# STEP_Controller.net
KiCad netlist of a schematic drawn in EasyEDA Pro
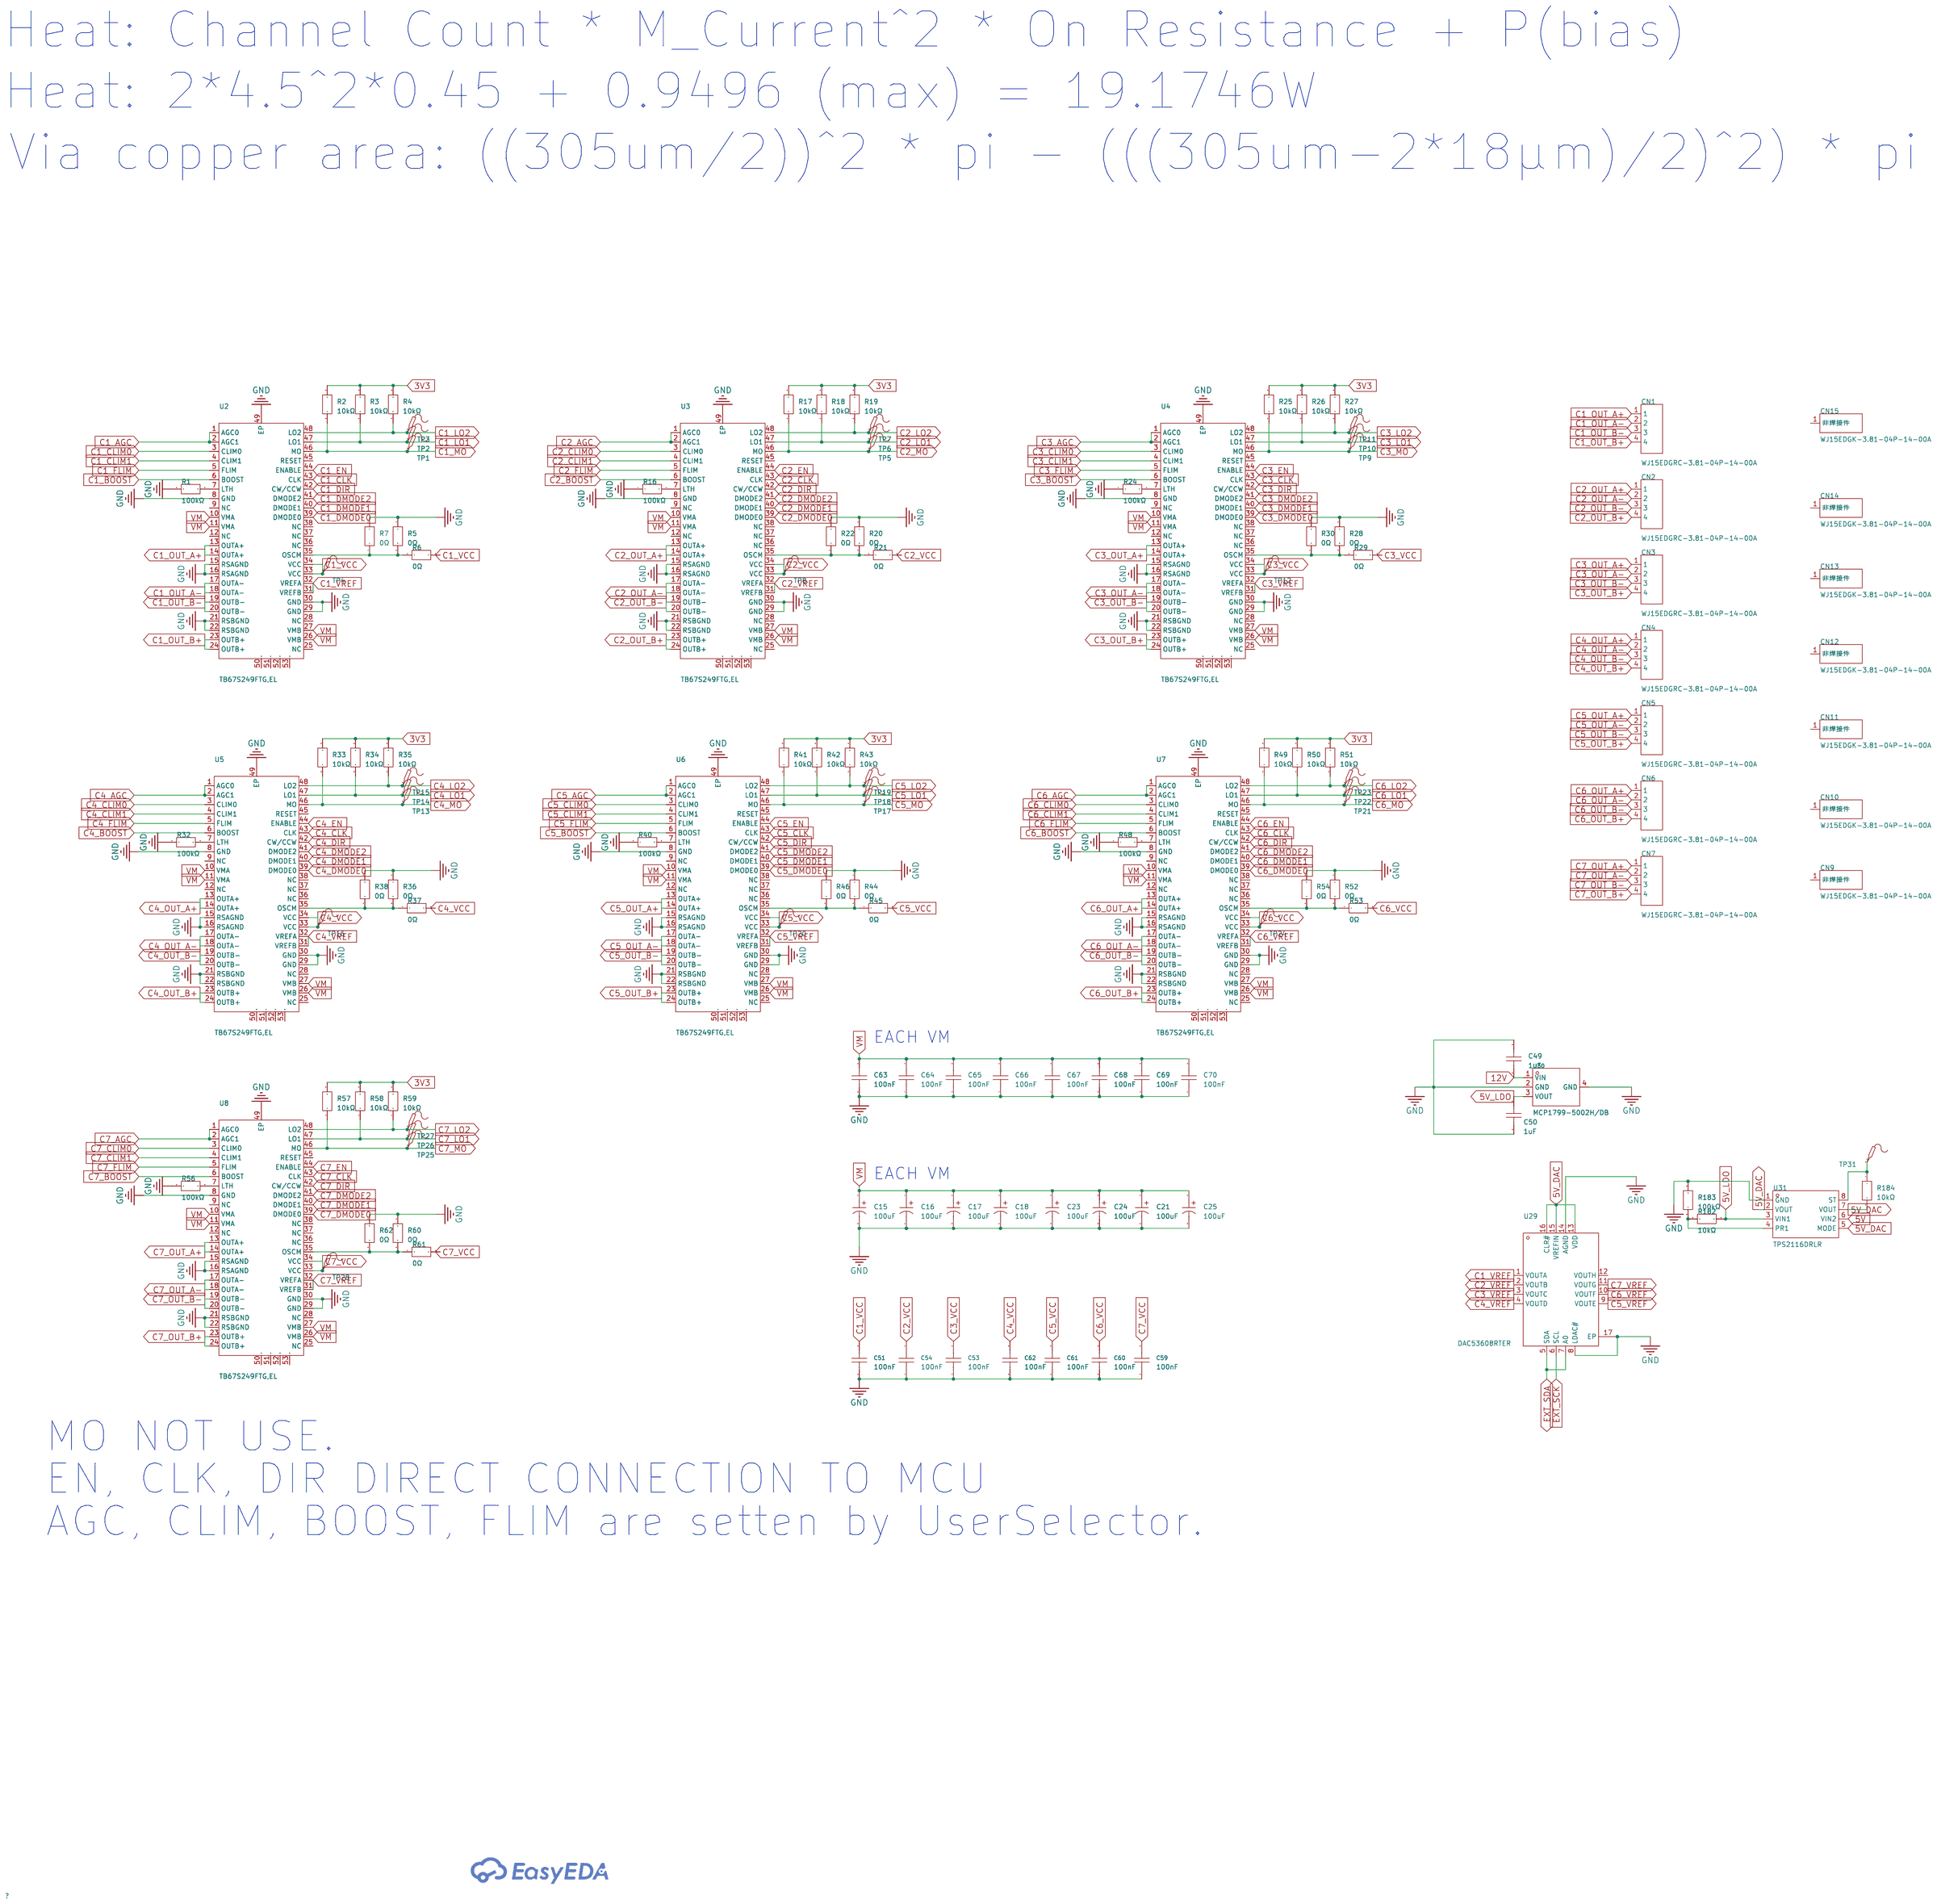
[diagram p0: DRIVER]
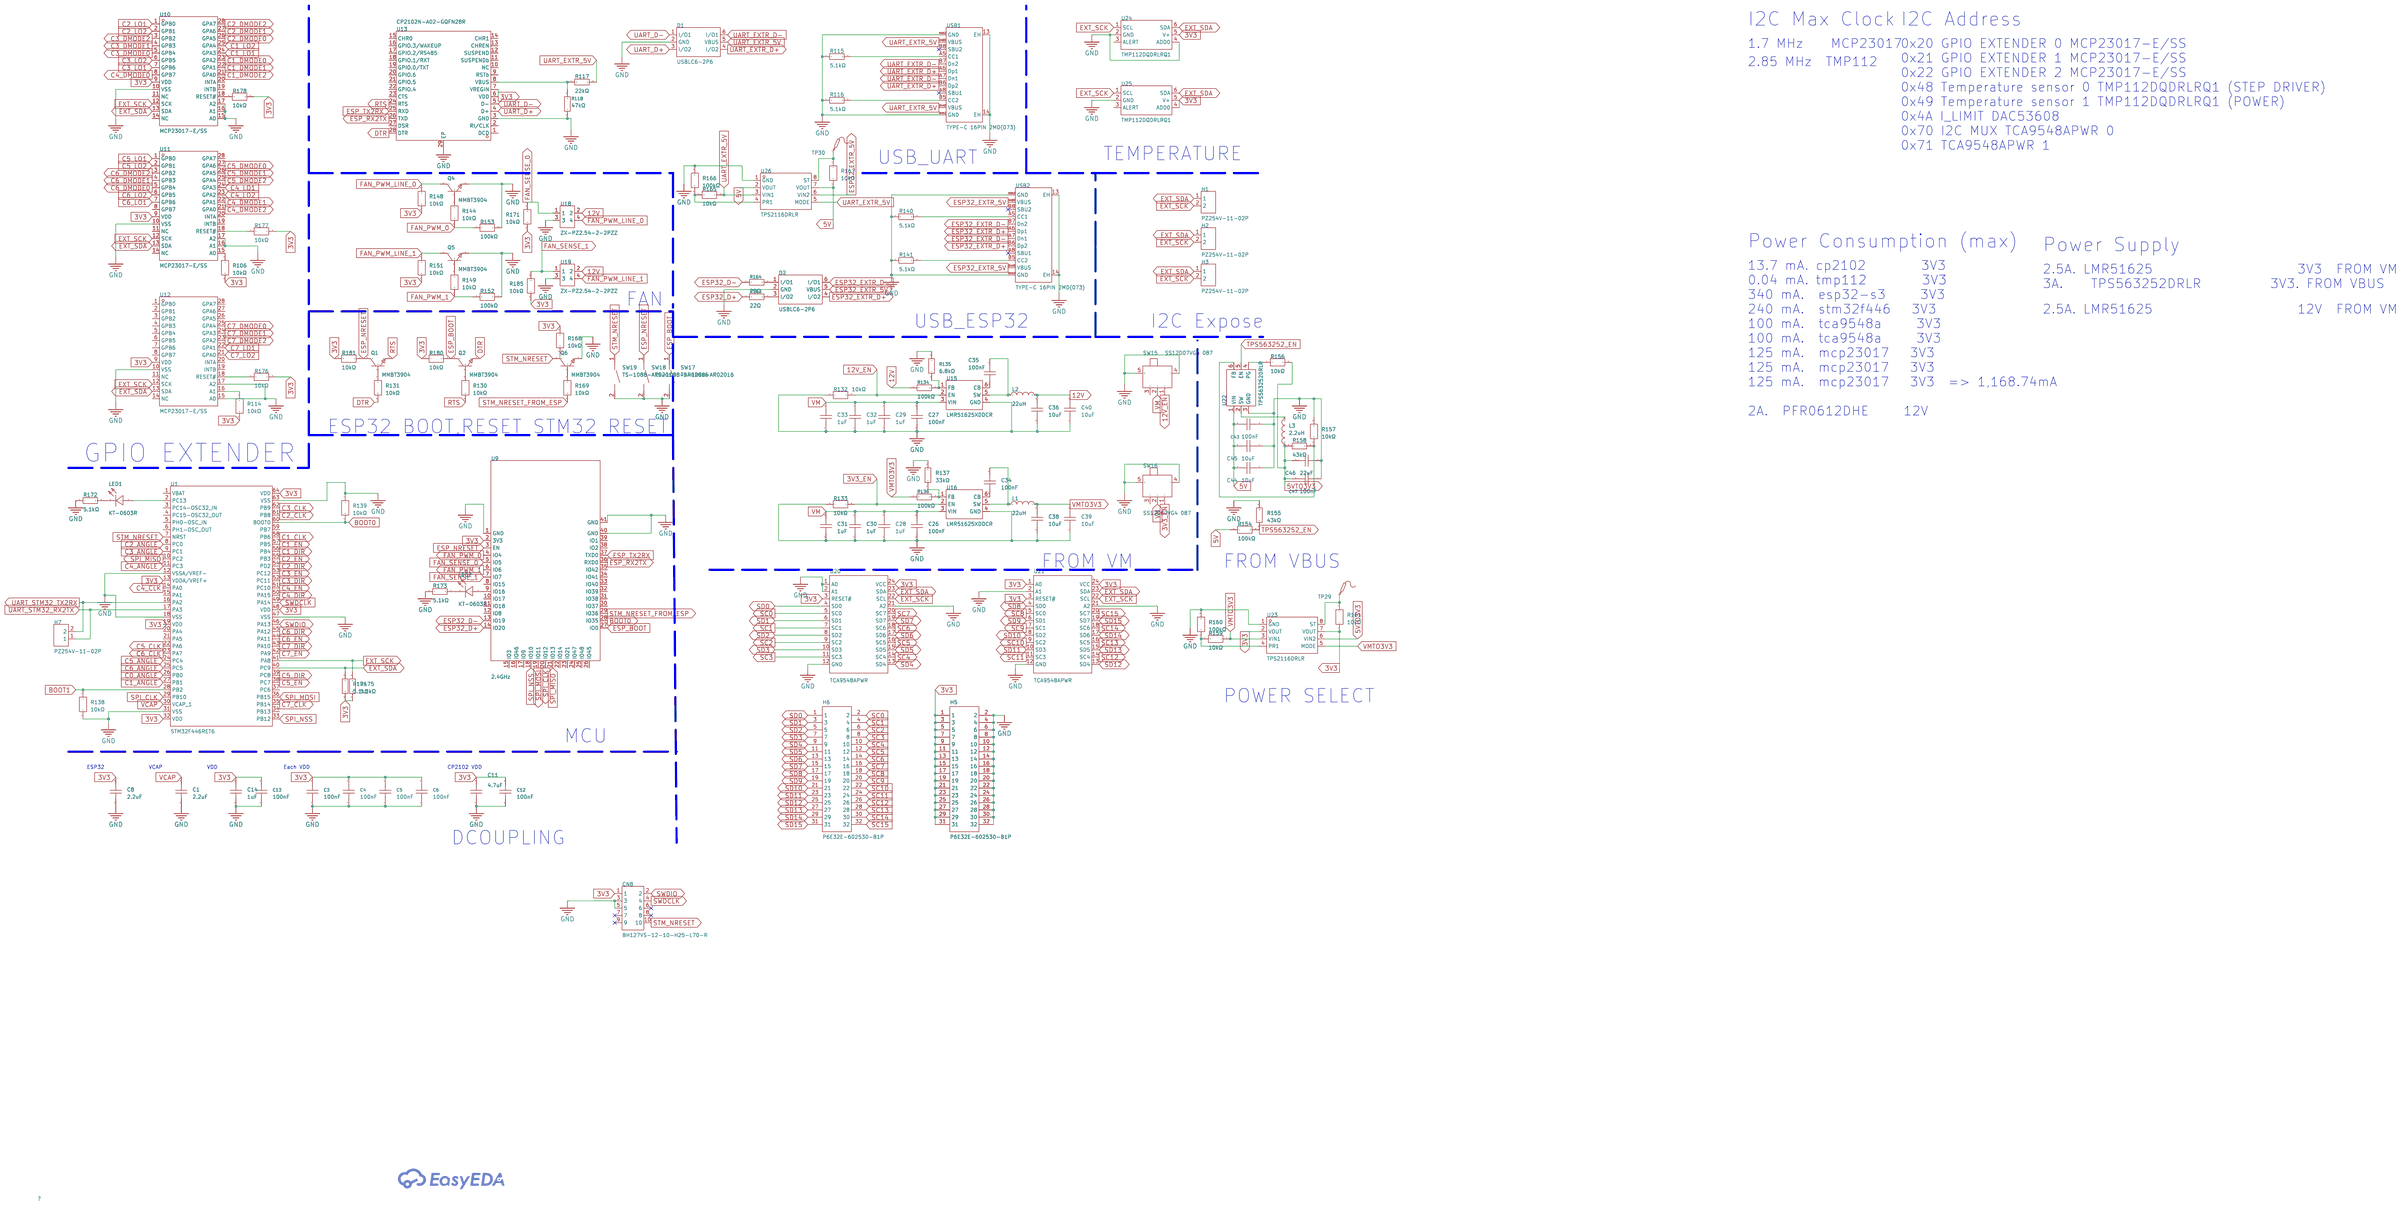
[diagram p1: MCU]
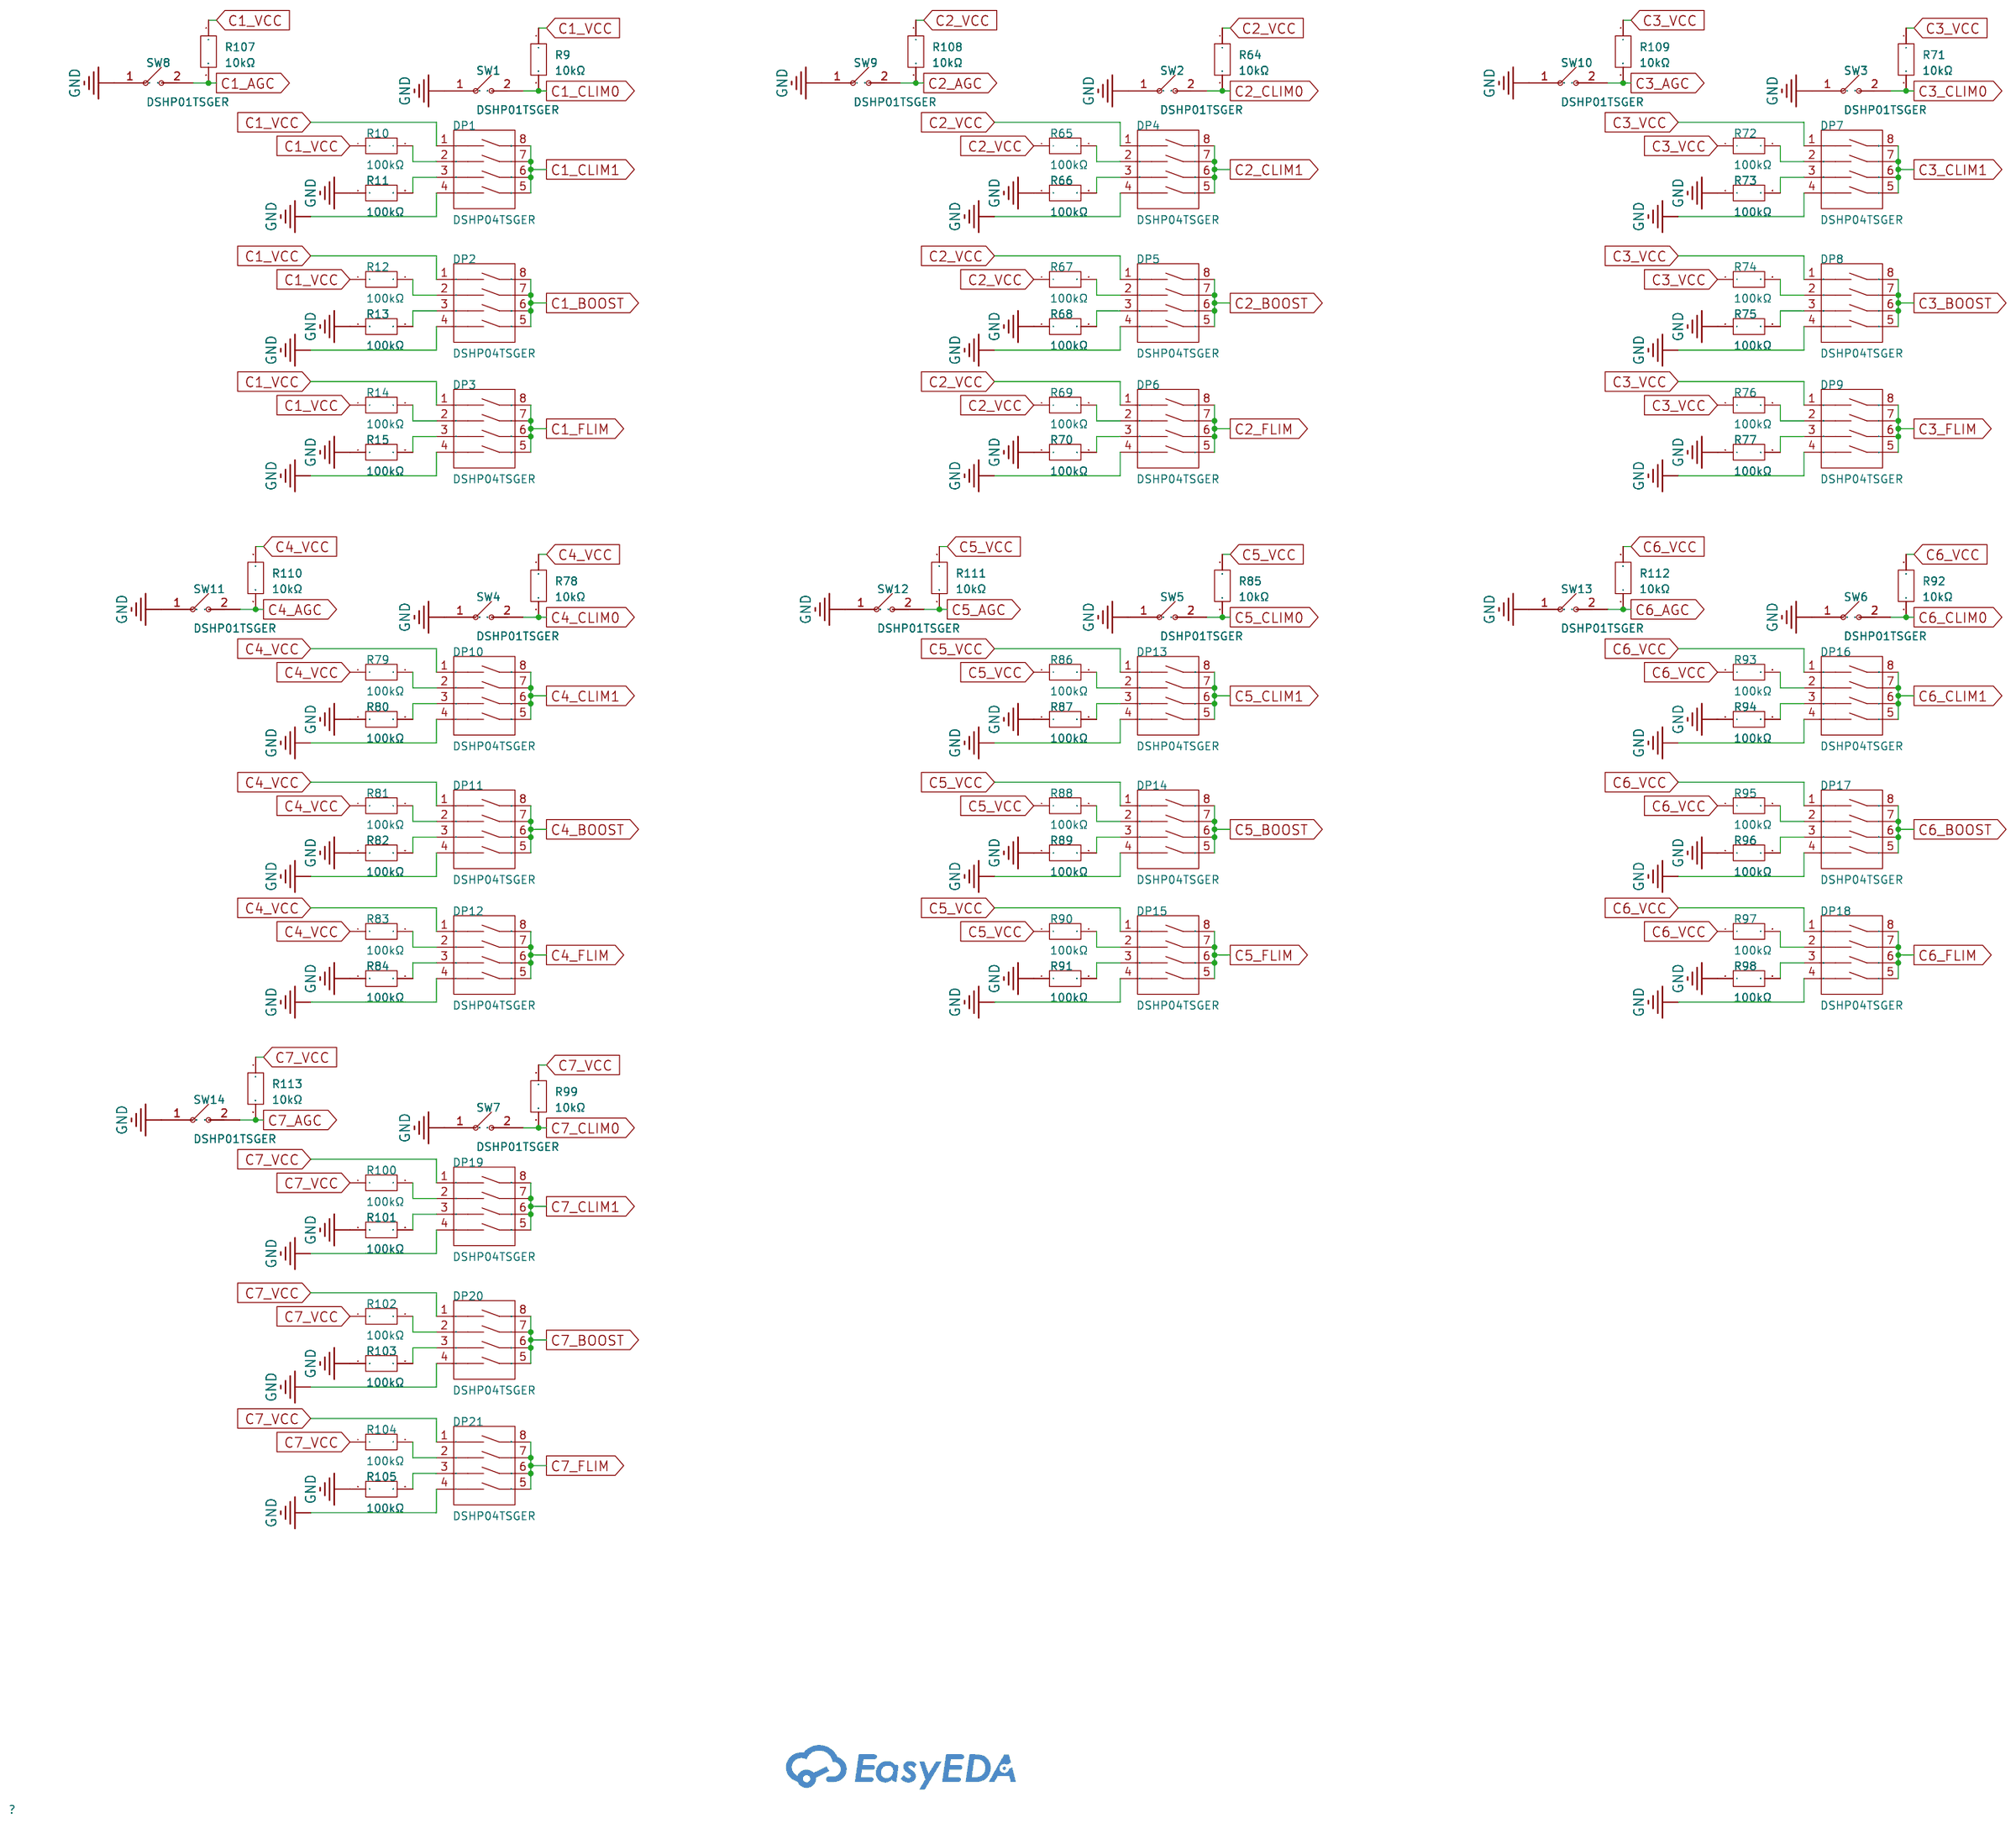
[diagram p2: UserSelector]

(export (version "E")
  (design (tool "Eeschema 10.0.6"))
  (components
    (comp (ref "C15")
      (value "100uF")
      (footprint "easyedapro:CAP-TH_BD13.0-P5.00-D1.2-FD")
      (fields
        (field (name "Manufacturer Part") "ERS1JM101F12OTG")
        (field (name "Manufacturer") "AISHI(艾华集团)")
      )
      (libsource (lib "easyedapro") (part "GHS2A107M1316PC"))
    )
    (comp (ref "C16")
      (value "100uF")
      (footprint "easyedapro:CAP-TH_BD13.0-P5.00-D1.2-FD")
      (fields
        (field (name "Manufacturer Part") "ERS1JM101F12OTG")
        (field (name "Manufacturer") "AISHI(艾华集团)")
      )
      (libsource (lib "easyedapro") (part "GHS2A107M1316PC"))
    )
    (comp (ref "C17")
      (value "100uF")
      (footprint "easyedapro:CAP-TH_BD13.0-P5.00-D1.2-FD")
      (fields
        (field (name "Manufacturer Part") "ERS1JM101F12OTG")
        (field (name "Manufacturer") "AISHI(艾华集团)")
      )
      (libsource (lib "easyedapro") (part "GHS2A107M1316PC"))
    )
    (comp (ref "C18")
      (value "100uF")
      (footprint "easyedapro:CAP-TH_BD13.0-P5.00-D1.2-FD")
      (fields
        (field (name "Manufacturer Part") "ERS1JM101F12OTG")
        (field (name "Manufacturer") "AISHI(艾华集团)")
      )
      (libsource (lib "easyedapro") (part "GHS2A107M1316PC"))
    )
    (comp (ref "C21")
      (value "100uF")
      (footprint "easyedapro:CAP-TH_BD13.0-P5.00-D1.2-FD")
      (fields
        (field (name "Manufacturer Part") "ERS1JM101F12OTG")
        (field (name "Manufacturer") "AISHI(艾华集团)")
      )
      (libsource (lib "easyedapro") (part "GHS2A107M1316PC"))
    )
    (comp (ref "C23")
      (value "100uF")
      (footprint "easyedapro:CAP-TH_BD13.0-P5.00-D1.2-FD")
      (fields
        (field (name "Manufacturer Part") "ERS1JM101F12OTG")
        (field (name "Manufacturer") "AISHI(艾华集团)")
      )
      (libsource (lib "easyedapro") (part "GHS2A107M1316PC"))
    )
    (comp (ref "C24")
      (value "100uF")
      (footprint "easyedapro:CAP-TH_BD13.0-P5.00-D1.2-FD")
      (fields
        (field (name "Manufacturer Part") "ERS1JM101F12OTG")
        (field (name "Manufacturer") "AISHI(艾华集团)")
      )
      (libsource (lib "easyedapro") (part "GHS2A107M1316PC"))
    )
    (comp (ref "C25")
      (value "100uF")
      (footprint "easyedapro:CAP-TH_BD13.0-P5.00-D1.2-FD")
      (fields
        (field (name "Manufacturer Part") "ERS1JM101F12OTG")
        (field (name "Manufacturer") "AISHI(艾华集团)")
      )
      (libsource (lib "easyedapro") (part "GHS2A107M1316PC"))
    )
    (comp (ref "C49")
      (value "1uF")
      (footprint "easyedapro:C0603")
      (description "Capacitance:1uF Tolerance:±10% Tolerance:±10% Voltage Rating:50V Temperature Coefficient:X5R")
      (fields
        (field (name "Manufacturer Part") "CL10A105KB8NNNC")
        (field (name "Manufacturer") "SAMSUNG(三星)")
      )
      (libsource (lib "easyedapro") (part "CL10A105KB8NNNC"))
    )
    (comp (ref "C50")
      (value "1uF")
      (footprint "easyedapro:C0603")
      (description "Capacitance:1uF Tolerance:±10% Tolerance:±10% Voltage Rating:50V Temperature Coefficient:X5R")
      (fields
        (field (name "Manufacturer Part") "CL10A105KB8NNNC")
        (field (name "Manufacturer") "SAMSUNG(三星)")
      )
      (libsource (lib "easyedapro") (part "CL10A105KB8NNNC"))
    )
    (comp (ref "C51")
      (value "100nF")
      (footprint "easyedapro:C0603")
      (description "Capacitance:100nF Tolerance:±10% Tolerance:±10% Voltage Rating:50V Temperature Coefficient:X7R")
      (fields
        (field (name "Manufacturer Part") "CC0603KRX7R9BB104")
        (field (name "Manufacturer") "YAGEO(国巨)")
      )
      (libsource (lib "easyedapro") (part "CL10B104KB8NNNC"))
    )
    (comp (ref "C53")
      (value "100nF")
      (footprint "easyedapro:C0603")
      (description "Capacitance:100nF Tolerance:±10% Tolerance:±10% Voltage Rating:50V Temperature Coefficient:X7R")
      (fields
        (field (name "Manufacturer Part") "CC0603KRX7R9BB104")
        (field (name "Manufacturer") "YAGEO(国巨)")
      )
      (libsource (lib "easyedapro") (part "CL10B104KB8NNNC"))
    )
    (comp (ref "C54")
      (value "100nF")
      (footprint "easyedapro:C0603")
      (description "Capacitance:100nF Tolerance:±10% Tolerance:±10% Voltage Rating:50V Temperature Coefficient:X7R")
      (fields
        (field (name "Manufacturer Part") "CC0603KRX7R9BB104")
        (field (name "Manufacturer") "YAGEO(国巨)")
      )
      (libsource (lib "easyedapro") (part "CL10B104KB8NNNC"))
    )
    (comp (ref "C59")
      (value "100nF")
      (footprint "easyedapro:C0603")
      (description "Capacitance:100nF Tolerance:±10% Tolerance:±10% Voltage Rating:50V Temperature Coefficient:X7R")
      (fields
        (field (name "Manufacturer Part") "CC0603KRX7R9BB104")
        (field (name "Manufacturer") "YAGEO(国巨)")
      )
      (libsource (lib "easyedapro") (part "CL10B104KB8NNNC"))
    )
    (comp (ref "C60")
      (value "100nF")
      (footprint "easyedapro:C0603")
      (description "Capacitance:100nF Tolerance:±10% Tolerance:±10% Voltage Rating:50V Temperature Coefficient:X7R")
      (fields
        (field (name "Manufacturer Part") "CC0603KRX7R9BB104")
        (field (name "Manufacturer") "YAGEO(国巨)")
      )
      (libsource (lib "easyedapro") (part "CL10B104KB8NNNC"))
    )
    (comp (ref "C61")
      (value "100nF")
      (footprint "easyedapro:C0603")
      (description "Capacitance:100nF Tolerance:±10% Tolerance:±10% Voltage Rating:50V Temperature Coefficient:X7R")
      (fields
        (field (name "Manufacturer Part") "CC0603KRX7R9BB104")
        (field (name "Manufacturer") "YAGEO(国巨)")
      )
      (libsource (lib "easyedapro") (part "CL10B104KB8NNNC"))
    )
    (comp (ref "C62")
      (value "100nF")
      (footprint "easyedapro:C0603")
      (description "Capacitance:100nF Tolerance:±10% Tolerance:±10% Voltage Rating:50V Temperature Coefficient:X7R")
      (fields
        (field (name "Manufacturer Part") "CC0603KRX7R9BB104")
        (field (name "Manufacturer") "YAGEO(国巨)")
      )
      (libsource (lib "easyedapro") (part "CL10B104KB8NNNC"))
    )
    (comp (ref "C63")
      (value "100nF")
      (footprint "easyedapro:C0805")
      (description "Capacitance:100nF Tolerance:±10% Tolerance:±10% Voltage Rating:63V Temperature Coefficient:X7R")
      (fields
        (field (name "Manufacturer Part") "C0805C104KMRECAUTO")
        (field (name "Manufacturer") "KEMET(基美)")
      )
      (libsource (lib "easyedapro") (part "C0805C104KMRECAUTO"))
    )
    (comp (ref "C64")
      (value "100nF")
      (footprint "easyedapro:C0805")
      (description "Capacitance:100nF Tolerance:±10% Tolerance:±10% Voltage Rating:63V Temperature Coefficient:X7R")
      (fields
        (field (name "Manufacturer Part") "C0805C104KMRECAUTO")
        (field (name "Manufacturer") "KEMET(基美)")
      )
      (libsource (lib "easyedapro") (part "C0805C104KMRECAUTO"))
    )
    (comp (ref "C65")
      (value "100nF")
      (footprint "easyedapro:C0805")
      (description "Capacitance:100nF Tolerance:±10% Tolerance:±10% Voltage Rating:63V Temperature Coefficient:X7R")
      (fields
        (field (name "Manufacturer Part") "C0805C104KMRECAUTO")
        (field (name "Manufacturer") "KEMET(基美)")
      )
      (libsource (lib "easyedapro") (part "C0805C104KMRECAUTO"))
    )
    (comp (ref "C66")
      (value "100nF")
      (footprint "easyedapro:C0805")
      (description "Capacitance:100nF Tolerance:±10% Tolerance:±10% Voltage Rating:63V Temperature Coefficient:X7R")
      (fields
        (field (name "Manufacturer Part") "C0805C104KMRECAUTO")
        (field (name "Manufacturer") "KEMET(基美)")
      )
      (libsource (lib "easyedapro") (part "C0805C104KMRECAUTO"))
    )
    (comp (ref "C67")
      (value "100nF")
      (footprint "easyedapro:C0805")
      (description "Capacitance:100nF Tolerance:±10% Tolerance:±10% Voltage Rating:63V Temperature Coefficient:X7R")
      (fields
        (field (name "Manufacturer Part") "C0805C104KMRECAUTO")
        (field (name "Manufacturer") "KEMET(基美)")
      )
      (libsource (lib "easyedapro") (part "C0805C104KMRECAUTO"))
    )
    (comp (ref "C68")
      (value "100nF")
      (footprint "easyedapro:C0805")
      (description "Capacitance:100nF Tolerance:±10% Tolerance:±10% Voltage Rating:63V Temperature Coefficient:X7R")
      (fields
        (field (name "Manufacturer Part") "C0805C104KMRECAUTO")
        (field (name "Manufacturer") "KEMET(基美)")
      )
      (libsource (lib "easyedapro") (part "C0805C104KMRECAUTO"))
    )
    (comp (ref "C69")
      (value "100nF")
      (footprint "easyedapro:C0805")
      (description "Capacitance:100nF Tolerance:±10% Tolerance:±10% Voltage Rating:63V Temperature Coefficient:X7R")
      (fields
        (field (name "Manufacturer Part") "C0805C104KMRECAUTO")
        (field (name "Manufacturer") "KEMET(基美)")
      )
      (libsource (lib "easyedapro") (part "C0805C104KMRECAUTO"))
    )
    (comp (ref "C70")
      (value "100nF")
      (footprint "easyedapro:C0805")
      (description "Capacitance:100nF Tolerance:±10% Tolerance:±10% Voltage Rating:63V Temperature Coefficient:X7R")
      (fields
        (field (name "Manufacturer Part") "C0805C104KMRECAUTO")
        (field (name "Manufacturer") "KEMET(基美)")
      )
      (libsource (lib "easyedapro") (part "C0805C104KMRECAUTO"))
    )
    (comp (ref "CN1")
      (value "WJ15EDGRC-3.81-04P-14-00A")
      (footprint "easyedapro:CONN-TH_WJ15EDGRC-3.81-4P")
      (fields (field (name "Manufacturer") "KANGNEX(康奈克斯电气)"))
      (libsource (lib "easyedapro") (part "WJ15EDGRC-3.81-4P"))
    )
    (comp (ref "CN2")
      (value "WJ15EDGRC-3.81-04P-14-00A")
      (footprint "easyedapro:CONN-TH_WJ15EDGRC-3.81-4P")
      (fields (field (name "Manufacturer") "KANGNEX(康奈克斯电气)"))
      (libsource (lib "easyedapro") (part "WJ15EDGRC-3.81-4P"))
    )
    (comp (ref "CN3")
      (value "WJ15EDGRC-3.81-04P-14-00A")
      (footprint "easyedapro:CONN-TH_WJ15EDGRC-3.81-4P")
      (fields (field (name "Manufacturer") "KANGNEX(康奈克斯电气)"))
      (libsource (lib "easyedapro") (part "WJ15EDGRC-3.81-4P"))
    )
    (comp (ref "CN4")
      (value "WJ15EDGRC-3.81-04P-14-00A")
      (footprint "easyedapro:CONN-TH_WJ15EDGRC-3.81-4P")
      (fields (field (name "Manufacturer") "KANGNEX(康奈克斯电气)"))
      (libsource (lib "easyedapro") (part "WJ15EDGRC-3.81-4P"))
    )
    (comp (ref "CN5")
      (value "WJ15EDGRC-3.81-04P-14-00A")
      (footprint "easyedapro:CONN-TH_WJ15EDGRC-3.81-4P")
      (fields (field (name "Manufacturer") "KANGNEX(康奈克斯电气)"))
      (libsource (lib "easyedapro") (part "WJ15EDGRC-3.81-4P"))
    )
    (comp (ref "CN6")
      (value "WJ15EDGRC-3.81-04P-14-00A")
      (footprint "easyedapro:CONN-TH_WJ15EDGRC-3.81-4P")
      (fields (field (name "Manufacturer") "KANGNEX(康奈克斯电气)"))
      (libsource (lib "easyedapro") (part "WJ15EDGRC-3.81-4P"))
    )
    (comp (ref "CN7")
      (value "WJ15EDGRC-3.81-04P-14-00A")
      (footprint "easyedapro:CONN-TH_WJ15EDGRC-3.81-4P")
      (fields (field (name "Manufacturer") "KANGNEX(康奈克斯电气)"))
      (libsource (lib "easyedapro") (part "WJ15EDGRC-3.81-4P"))
    )
    (comp (ref "CN9")
      (value "WJ15EDGK-3.81-04P-14-00A")
      (footprint "easyedapro:FL_001")
      (fields (field (name "Manufacturer") "KANGNEX(康奈克斯电气)"))
      (libsource (lib "easyedapro") (part "WJ15EDGK-3.81-4P"))
    )
    (comp (ref "CN10")
      (value "WJ15EDGK-3.81-04P-14-00A")
      (footprint "easyedapro:FL_001")
      (fields (field (name "Manufacturer") "KANGNEX(康奈克斯电气)"))
      (libsource (lib "easyedapro") (part "WJ15EDGK-3.81-4P"))
    )
    (comp (ref "CN11")
      (value "WJ15EDGK-3.81-04P-14-00A")
      (footprint "easyedapro:FL_001")
      (fields (field (name "Manufacturer") "KANGNEX(康奈克斯电气)"))
      (libsource (lib "easyedapro") (part "WJ15EDGK-3.81-4P"))
    )
    (comp (ref "CN12")
      (value "WJ15EDGK-3.81-04P-14-00A")
      (footprint "easyedapro:FL_001")
      (fields (field (name "Manufacturer") "KANGNEX(康奈克斯电气)"))
      (libsource (lib "easyedapro") (part "WJ15EDGK-3.81-4P"))
    )
    (comp (ref "CN13")
      (value "WJ15EDGK-3.81-04P-14-00A")
      (footprint "easyedapro:FL_001")
      (fields (field (name "Manufacturer") "KANGNEX(康奈克斯电气)"))
      (libsource (lib "easyedapro") (part "WJ15EDGK-3.81-4P"))
    )
    (comp (ref "CN14")
      (value "WJ15EDGK-3.81-04P-14-00A")
      (footprint "easyedapro:FL_001")
      (fields (field (name "Manufacturer") "KANGNEX(康奈克斯电气)"))
      (libsource (lib "easyedapro") (part "WJ15EDGK-3.81-4P"))
    )
    (comp (ref "CN15")
      (value "WJ15EDGK-3.81-04P-14-00A")
      (footprint "easyedapro:FL_001")
      (fields (field (name "Manufacturer") "KANGNEX(康奈克斯电气)"))
      (libsource (lib "easyedapro") (part "WJ15EDGK-3.81-4P"))
    )
    (comp (ref "R1")
      (value "100kΩ")
      (footprint "easyedapro:R0603")
      (fields
        (field (name "Manufacturer Part") "0603WAF1003T5E")
        (field (name "Manufacturer") "UNI-ROYAL(厚声)")
      )
      (libsource (lib "easyedapro") (part "FRC0603J104 TS"))
    )
    (comp (ref "R2")
      (value "10kΩ")
      (footprint "easyedapro:R0603")
      (fields
        (field (name "Manufacturer Part") "0603WAF1002T5E")
        (field (name "Manufacturer") "UNI-ROYAL(厚声)")
      )
      (libsource (lib "easyedapro") (part "FRC0603J103TS"))
    )
    (comp (ref "R3")
      (value "10kΩ")
      (footprint "easyedapro:R0603")
      (fields
        (field (name "Manufacturer Part") "0603WAF1002T5E")
        (field (name "Manufacturer") "UNI-ROYAL(厚声)")
      )
      (libsource (lib "easyedapro") (part "FRC0603J103TS"))
    )
    (comp (ref "R4")
      (value "10kΩ")
      (footprint "easyedapro:R0603")
      (fields
        (field (name "Manufacturer Part") "0603WAF1002T5E")
        (field (name "Manufacturer") "UNI-ROYAL(厚声)")
      )
      (libsource (lib "easyedapro") (part "FRC0603J103TS"))
    )
    (comp (ref "R5")
      (value "0Ω")
      (footprint "easyedapro:R0603")
      (fields
        (field (name "Manufacturer Part") "0603WAF0000T5E")
        (field (name "Manufacturer") "UNI-ROYAL(厚声)")
      )
      (libsource (lib "easyedapro") (part "FRC0603P000 TS"))
    )
    (comp (ref "R6")
      (value "0Ω")
      (footprint "easyedapro:R0603")
      (fields
        (field (name "Manufacturer Part") "0603WAF0000T5E")
        (field (name "Manufacturer") "UNI-ROYAL(厚声)")
      )
      (libsource (lib "easyedapro") (part "FRC0603P000 TS"))
    )
    (comp (ref "R7")
      (value "0Ω")
      (footprint "easyedapro:R0603")
      (fields
        (field (name "Manufacturer Part") "0603WAF0000T5E")
        (field (name "Manufacturer") "UNI-ROYAL(厚声)")
      )
      (libsource (lib "easyedapro") (part "FRC0603P000 TS"))
    )
    (comp (ref "R16")
      (value "100kΩ")
      (footprint "easyedapro:R0603")
      (fields
        (field (name "Manufacturer Part") "0603WAF1003T5E")
        (field (name "Manufacturer") "UNI-ROYAL(厚声)")
      )
      (libsource (lib "easyedapro") (part "FRC0603J104 TS"))
    )
    (comp (ref "R17")
      (value "10kΩ")
      (footprint "easyedapro:R0603")
      (fields
        (field (name "Manufacturer Part") "0603WAF1002T5E")
        (field (name "Manufacturer") "UNI-ROYAL(厚声)")
      )
      (libsource (lib "easyedapro") (part "FRC0603J103TS"))
    )
    (comp (ref "R18")
      (value "10kΩ")
      (footprint "easyedapro:R0603")
      (fields
        (field (name "Manufacturer Part") "0603WAF1002T5E")
        (field (name "Manufacturer") "UNI-ROYAL(厚声)")
      )
      (libsource (lib "easyedapro") (part "FRC0603J103TS"))
    )
    (comp (ref "R19")
      (value "10kΩ")
      (footprint "easyedapro:R0603")
      (fields
        (field (name "Manufacturer Part") "0603WAF1002T5E")
        (field (name "Manufacturer") "UNI-ROYAL(厚声)")
      )
      (libsource (lib "easyedapro") (part "FRC0603J103TS"))
    )
    (comp (ref "R20")
      (value "0Ω")
      (footprint "easyedapro:R0603")
      (fields
        (field (name "Manufacturer Part") "0603WAF0000T5E")
        (field (name "Manufacturer") "UNI-ROYAL(厚声)")
      )
      (libsource (lib "easyedapro") (part "FRC0603P000 TS"))
    )
    (comp (ref "R21")
      (value "0Ω")
      (footprint "easyedapro:R0603")
      (fields
        (field (name "Manufacturer Part") "0603WAF0000T5E")
        (field (name "Manufacturer") "UNI-ROYAL(厚声)")
      )
      (libsource (lib "easyedapro") (part "FRC0603P000 TS"))
    )
    (comp (ref "R22")
      (value "0Ω")
      (footprint "easyedapro:R0603")
      (fields
        (field (name "Manufacturer Part") "0603WAF0000T5E")
        (field (name "Manufacturer") "UNI-ROYAL(厚声)")
      )
      (libsource (lib "easyedapro") (part "FRC0603P000 TS"))
    )
    (comp (ref "R24")
      (value "100kΩ")
      (footprint "easyedapro:R0603")
      (fields
        (field (name "Manufacturer Part") "0603WAF1003T5E")
        (field (name "Manufacturer") "UNI-ROYAL(厚声)")
      )
      (libsource (lib "easyedapro") (part "FRC0603J104 TS"))
    )
    (comp (ref "R25")
      (value "10kΩ")
      (footprint "easyedapro:R0603")
      (fields
        (field (name "Manufacturer Part") "0603WAF1002T5E")
        (field (name "Manufacturer") "UNI-ROYAL(厚声)")
      )
      (libsource (lib "easyedapro") (part "FRC0603J103TS"))
    )
    (comp (ref "R26")
      (value "10kΩ")
      (footprint "easyedapro:R0603")
      (fields
        (field (name "Manufacturer Part") "0603WAF1002T5E")
        (field (name "Manufacturer") "UNI-ROYAL(厚声)")
      )
      (libsource (lib "easyedapro") (part "FRC0603J103TS"))
    )
    (comp (ref "R27")
      (value "10kΩ")
      (footprint "easyedapro:R0603")
      (fields
        (field (name "Manufacturer Part") "0603WAF1002T5E")
        (field (name "Manufacturer") "UNI-ROYAL(厚声)")
      )
      (libsource (lib "easyedapro") (part "FRC0603J103TS"))
    )
    (comp (ref "R28")
      (value "0Ω")
      (footprint "easyedapro:R0603")
      (fields
        (field (name "Manufacturer Part") "0603WAF0000T5E")
        (field (name "Manufacturer") "UNI-ROYAL(厚声)")
      )
      (libsource (lib "easyedapro") (part "FRC0603P000 TS"))
    )
    (comp (ref "R29")
      (value "0Ω")
      (footprint "easyedapro:R0603")
      (fields
        (field (name "Manufacturer Part") "0603WAF0000T5E")
        (field (name "Manufacturer") "UNI-ROYAL(厚声)")
      )
      (libsource (lib "easyedapro") (part "FRC0603P000 TS"))
    )
    (comp (ref "R30")
      (value "0Ω")
      (footprint "easyedapro:R0603")
      (fields
        (field (name "Manufacturer Part") "0603WAF0000T5E")
        (field (name "Manufacturer") "UNI-ROYAL(厚声)")
      )
      (libsource (lib "easyedapro") (part "FRC0603P000 TS"))
    )
    (comp (ref "R32")
      (value "100kΩ")
      (footprint "easyedapro:R0603")
      (fields
        (field (name "Manufacturer Part") "0603WAF1003T5E")
        (field (name "Manufacturer") "UNI-ROYAL(厚声)")
      )
      (libsource (lib "easyedapro") (part "FRC0603J104 TS"))
    )
    (comp (ref "R33")
      (value "10kΩ")
      (footprint "easyedapro:R0603")
      (fields
        (field (name "Manufacturer Part") "0603WAF1002T5E")
        (field (name "Manufacturer") "UNI-ROYAL(厚声)")
      )
      (libsource (lib "easyedapro") (part "FRC0603J103TS"))
    )
    (comp (ref "R34")
      (value "10kΩ")
      (footprint "easyedapro:R0603")
      (fields
        (field (name "Manufacturer Part") "0603WAF1002T5E")
        (field (name "Manufacturer") "UNI-ROYAL(厚声)")
      )
      (libsource (lib "easyedapro") (part "FRC0603J103TS"))
    )
    (comp (ref "R35")
      (value "10kΩ")
      (footprint "easyedapro:R0603")
      (fields
        (field (name "Manufacturer Part") "0603WAF1002T5E")
        (field (name "Manufacturer") "UNI-ROYAL(厚声)")
      )
      (libsource (lib "easyedapro") (part "FRC0603J103TS"))
    )
    (comp (ref "R36")
      (value "0Ω")
      (footprint "easyedapro:R0603")
      (fields
        (field (name "Manufacturer Part") "0603WAF0000T5E")
        (field (name "Manufacturer") "UNI-ROYAL(厚声)")
      )
      (libsource (lib "easyedapro") (part "FRC0603P000 TS"))
    )
    (comp (ref "R37")
      (value "0Ω")
      (footprint "easyedapro:R0603")
      (fields
        (field (name "Manufacturer Part") "0603WAF0000T5E")
        (field (name "Manufacturer") "UNI-ROYAL(厚声)")
      )
      (libsource (lib "easyedapro") (part "FRC0603P000 TS"))
    )
    (comp (ref "R38")
      (value "0Ω")
      (footprint "easyedapro:R0603")
      (fields
        (field (name "Manufacturer Part") "0603WAF0000T5E")
        (field (name "Manufacturer") "UNI-ROYAL(厚声)")
      )
      (libsource (lib "easyedapro") (part "FRC0603P000 TS"))
    )
    (comp (ref "R40")
      (value "100kΩ")
      (footprint "easyedapro:R0603")
      (fields
        (field (name "Manufacturer Part") "0603WAF1003T5E")
        (field (name "Manufacturer") "UNI-ROYAL(厚声)")
      )
      (libsource (lib "easyedapro") (part "FRC0603J104 TS"))
    )
    (comp (ref "R41")
      (value "10kΩ")
      (footprint "easyedapro:R0603")
      (fields
        (field (name "Manufacturer Part") "0603WAF1002T5E")
        (field (name "Manufacturer") "UNI-ROYAL(厚声)")
      )
      (libsource (lib "easyedapro") (part "FRC0603J103TS"))
    )
    (comp (ref "R42")
      (value "10kΩ")
      (footprint "easyedapro:R0603")
      (fields
        (field (name "Manufacturer Part") "0603WAF1002T5E")
        (field (name "Manufacturer") "UNI-ROYAL(厚声)")
      )
      (libsource (lib "easyedapro") (part "FRC0603J103TS"))
    )
    (comp (ref "R43")
      (value "10kΩ")
      (footprint "easyedapro:R0603")
      (fields
        (field (name "Manufacturer Part") "0603WAF1002T5E")
        (field (name "Manufacturer") "UNI-ROYAL(厚声)")
      )
      (libsource (lib "easyedapro") (part "FRC0603J103TS"))
    )
    (comp (ref "R44")
      (value "0Ω")
      (footprint "easyedapro:R0603")
      (fields
        (field (name "Manufacturer Part") "0603WAF0000T5E")
        (field (name "Manufacturer") "UNI-ROYAL(厚声)")
      )
      (libsource (lib "easyedapro") (part "FRC0603P000 TS"))
    )
    (comp (ref "R45")
      (value "0Ω")
      (footprint "easyedapro:R0603")
      (fields
        (field (name "Manufacturer Part") "0603WAF0000T5E")
        (field (name "Manufacturer") "UNI-ROYAL(厚声)")
      )
      (libsource (lib "easyedapro") (part "FRC0603P000 TS"))
    )
    (comp (ref "R46")
      (value "0Ω")
      (footprint "easyedapro:R0603")
      (fields
        (field (name "Manufacturer Part") "0603WAF0000T5E")
        (field (name "Manufacturer") "UNI-ROYAL(厚声)")
      )
      (libsource (lib "easyedapro") (part "FRC0603P000 TS"))
    )
    (comp (ref "R48")
      (value "100kΩ")
      (footprint "easyedapro:R0603")
      (fields
        (field (name "Manufacturer Part") "0603WAF1003T5E")
        (field (name "Manufacturer") "UNI-ROYAL(厚声)")
      )
      (libsource (lib "easyedapro") (part "FRC0603J104 TS"))
    )
    (comp (ref "R49")
      (value "10kΩ")
      (footprint "easyedapro:R0603")
      (fields
        (field (name "Manufacturer Part") "0603WAF1002T5E")
        (field (name "Manufacturer") "UNI-ROYAL(厚声)")
      )
      (libsource (lib "easyedapro") (part "FRC0603J103TS"))
    )
    (comp (ref "R50")
      (value "10kΩ")
      (footprint "easyedapro:R0603")
      (fields
        (field (name "Manufacturer Part") "0603WAF1002T5E")
        (field (name "Manufacturer") "UNI-ROYAL(厚声)")
      )
      (libsource (lib "easyedapro") (part "FRC0603J103TS"))
    )
    (comp (ref "R51")
      (value "10kΩ")
      (footprint "easyedapro:R0603")
      (fields
        (field (name "Manufacturer Part") "0603WAF1002T5E")
        (field (name "Manufacturer") "UNI-ROYAL(厚声)")
      )
      (libsource (lib "easyedapro") (part "FRC0603J103TS"))
    )
    (comp (ref "R52")
      (value "0Ω")
      (footprint "easyedapro:R0603")
      (fields
        (field (name "Manufacturer Part") "0603WAF0000T5E")
        (field (name "Manufacturer") "UNI-ROYAL(厚声)")
      )
      (libsource (lib "easyedapro") (part "FRC0603P000 TS"))
    )
    (comp (ref "R53")
      (value "0Ω")
      (footprint "easyedapro:R0603")
      (fields
        (field (name "Manufacturer Part") "0603WAF0000T5E")
        (field (name "Manufacturer") "UNI-ROYAL(厚声)")
      )
      (libsource (lib "easyedapro") (part "FRC0603P000 TS"))
    )
    (comp (ref "R54")
      (value "0Ω")
      (footprint "easyedapro:R0603")
      (fields
        (field (name "Manufacturer Part") "0603WAF0000T5E")
        (field (name "Manufacturer") "UNI-ROYAL(厚声)")
      )
      (libsource (lib "easyedapro") (part "FRC0603P000 TS"))
    )
    (comp (ref "R56")
      (value "100kΩ")
      (footprint "easyedapro:R0603")
      (fields
        (field (name "Manufacturer Part") "0603WAF1003T5E")
        (field (name "Manufacturer") "UNI-ROYAL(厚声)")
      )
      (libsource (lib "easyedapro") (part "FRC0603J104 TS"))
    )
    (comp (ref "R57")
      (value "10kΩ")
      (footprint "easyedapro:R0603")
      (fields
        (field (name "Manufacturer Part") "0603WAF1002T5E")
        (field (name "Manufacturer") "UNI-ROYAL(厚声)")
      )
      (libsource (lib "easyedapro") (part "FRC0603J103TS"))
    )
    (comp (ref "R58")
      (value "10kΩ")
      (footprint "easyedapro:R0603")
      (fields
        (field (name "Manufacturer Part") "0603WAF1002T5E")
        (field (name "Manufacturer") "UNI-ROYAL(厚声)")
      )
      (libsource (lib "easyedapro") (part "FRC0603J103TS"))
    )
    (comp (ref "R59")
      (value "10kΩ")
      (footprint "easyedapro:R0603")
      (fields
        (field (name "Manufacturer Part") "0603WAF1002T5E")
        (field (name "Manufacturer") "UNI-ROYAL(厚声)")
      )
      (libsource (lib "easyedapro") (part "FRC0603J103TS"))
    )
    (comp (ref "R60")
      (value "0Ω")
      (footprint "easyedapro:R0603")
      (fields
        (field (name "Manufacturer Part") "0603WAF0000T5E")
        (field (name "Manufacturer") "UNI-ROYAL(厚声)")
      )
      (libsource (lib "easyedapro") (part "FRC0603P000 TS"))
    )
    (comp (ref "R61")
      (value "0Ω")
      (footprint "easyedapro:R0603")
      (fields
        (field (name "Manufacturer Part") "0603WAF0000T5E")
        (field (name "Manufacturer") "UNI-ROYAL(厚声)")
      )
      (libsource (lib "easyedapro") (part "FRC0603P000 TS"))
    )
    (comp (ref "R62")
      (value "0Ω")
      (footprint "easyedapro:R0603")
      (fields
        (field (name "Manufacturer Part") "0603WAF0000T5E")
        (field (name "Manufacturer") "UNI-ROYAL(厚声)")
      )
      (libsource (lib "easyedapro") (part "FRC0603P000 TS"))
    )
    (comp (ref "R182")
      (value "10kΩ")
      (footprint "easyedapro:R0603")
      (fields
        (field (name "Manufacturer Part") "0603WAF1002T5E")
        (field (name "Manufacturer") "UNI-ROYAL(厚声)")
      )
      (libsource (lib "easyedapro") (part "FRC0603J103TS"))
    )
    (comp (ref "R183")
      (value "100kΩ")
      (footprint "easyedapro:R0603")
      (fields
        (field (name "Manufacturer Part") "0603WAF1003T5E")
        (field (name "Manufacturer") "UNI-ROYAL(厚声)")
      )
      (libsource (lib "easyedapro") (part "FRC0603J104 TS"))
    )
    (comp (ref "R184")
      (value "10kΩ")
      (footprint "easyedapro:R0603")
      (fields
        (field (name "Manufacturer Part") "0603WAF1002T5E")
        (field (name "Manufacturer") "UNI-ROYAL(厚声)")
      )
      (libsource (lib "easyedapro") (part "FRC0603J103TS"))
    )
    (comp (ref "TP1")
      (value "~")
      (footprint "easyedapro:Test-Point-0.5mm")
      (description "Test Point 测试点")
      (libsource (lib "easyedapro") (part "Test-Point"))
    )
    (comp (ref "TP2")
      (value "~")
      (footprint "easyedapro:Test-Point-0.5mm")
      (description "Test Point 测试点")
      (libsource (lib "easyedapro") (part "Test-Point"))
    )
    (comp (ref "TP3")
      (value "~")
      (footprint "easyedapro:Test-Point-0.5mm")
      (description "Test Point 测试点")
      (libsource (lib "easyedapro") (part "Test-Point"))
    )
    (comp (ref "TP4")
      (value "~")
      (footprint "easyedapro:Test-Point-0.5mm")
      (description "Test Point 测试点")
      (libsource (lib "easyedapro") (part "Test-Point"))
    )
    (comp (ref "TP5")
      (value "~")
      (footprint "easyedapro:Test-Point-0.5mm")
      (description "Test Point 测试点")
      (libsource (lib "easyedapro") (part "Test-Point"))
    )
    (comp (ref "TP6")
      (value "~")
      (footprint "easyedapro:Test-Point-0.5mm")
      (description "Test Point 测试点")
      (libsource (lib "easyedapro") (part "Test-Point"))
    )
    (comp (ref "TP7")
      (value "~")
      (footprint "easyedapro:Test-Point-0.5mm")
      (description "Test Point 测试点")
      (libsource (lib "easyedapro") (part "Test-Point"))
    )
    (comp (ref "TP8")
      (value "~")
      (footprint "easyedapro:Test-Point-0.5mm")
      (description "Test Point 测试点")
      (libsource (lib "easyedapro") (part "Test-Point"))
    )
    (comp (ref "TP9")
      (value "~")
      (footprint "easyedapro:Test-Point-0.5mm")
      (description "Test Point 测试点")
      (libsource (lib "easyedapro") (part "Test-Point"))
    )
    (comp (ref "TP10")
      (value "~")
      (footprint "easyedapro:Test-Point-0.5mm")
      (description "Test Point 测试点")
      (libsource (lib "easyedapro") (part "Test-Point"))
    )
    (comp (ref "TP11")
      (value "~")
      (footprint "easyedapro:Test-Point-0.5mm")
      (description "Test Point 测试点")
      (libsource (lib "easyedapro") (part "Test-Point"))
    )
    (comp (ref "TP12")
      (value "~")
      (footprint "easyedapro:Test-Point-0.5mm")
      (description "Test Point 测试点")
      (libsource (lib "easyedapro") (part "Test-Point"))
    )
    (comp (ref "TP13")
      (value "~")
      (footprint "easyedapro:Test-Point-0.5mm")
      (description "Test Point 测试点")
      (libsource (lib "easyedapro") (part "Test-Point"))
    )
    (comp (ref "TP14")
      (value "~")
      (footprint "easyedapro:Test-Point-0.5mm")
      (description "Test Point 测试点")
      (libsource (lib "easyedapro") (part "Test-Point"))
    )
    (comp (ref "TP15")
      (value "~")
      (footprint "easyedapro:Test-Point-0.5mm")
      (description "Test Point 测试点")
      (libsource (lib "easyedapro") (part "Test-Point"))
    )
    (comp (ref "TP16")
      (value "~")
      (footprint "easyedapro:Test-Point-0.5mm")
      (description "Test Point 测试点")
      (libsource (lib "easyedapro") (part "Test-Point"))
    )
    (comp (ref "TP17")
      (value "~")
      (footprint "easyedapro:Test-Point-0.5mm")
      (description "Test Point 测试点")
      (libsource (lib "easyedapro") (part "Test-Point"))
    )
    (comp (ref "TP18")
      (value "~")
      (footprint "easyedapro:Test-Point-0.5mm")
      (description "Test Point 测试点")
      (libsource (lib "easyedapro") (part "Test-Point"))
    )
    (comp (ref "TP19")
      (value "~")
      (footprint "easyedapro:Test-Point-0.5mm")
      (description "Test Point 测试点")
      (libsource (lib "easyedapro") (part "Test-Point"))
    )
    (comp (ref "TP20")
      (value "~")
      (footprint "easyedapro:Test-Point-0.5mm")
      (description "Test Point 测试点")
      (libsource (lib "easyedapro") (part "Test-Point"))
    )
    (comp (ref "TP21")
      (value "~")
      (footprint "easyedapro:Test-Point-0.5mm")
      (description "Test Point 测试点")
      (libsource (lib "easyedapro") (part "Test-Point"))
    )
    (comp (ref "TP22")
      (value "~")
      (footprint "easyedapro:Test-Point-0.5mm")
      (description "Test Point 测试点")
      (libsource (lib "easyedapro") (part "Test-Point"))
    )
    (comp (ref "TP23")
      (value "~")
      (footprint "easyedapro:Test-Point-0.5mm")
      (description "Test Point 测试点")
      (libsource (lib "easyedapro") (part "Test-Point"))
    )
    (comp (ref "TP24")
      (value "~")
      (footprint "easyedapro:Test-Point-0.5mm")
      (description "Test Point 测试点")
      (libsource (lib "easyedapro") (part "Test-Point"))
    )
    (comp (ref "TP25")
      (value "~")
      (footprint "easyedapro:Test-Point-0.5mm")
      (description "Test Point 测试点")
      (libsource (lib "easyedapro") (part "Test-Point"))
    )
    (comp (ref "TP26")
      (value "~")
      (footprint "easyedapro:Test-Point-0.5mm")
      (description "Test Point 测试点")
      (libsource (lib "easyedapro") (part "Test-Point"))
    )
    (comp (ref "TP27")
      (value "~")
      (footprint "easyedapro:Test-Point-0.5mm")
      (description "Test Point 测试点")
      (libsource (lib "easyedapro") (part "Test-Point"))
    )
    (comp (ref "TP28")
      (value "~")
      (footprint "easyedapro:Test-Point-0.5mm")
      (description "Test Point 测试点")
      (libsource (lib "easyedapro") (part "Test-Point"))
    )
    (comp (ref "TP31")
      (value "~")
      (footprint "easyedapro:Test-Point-0.5mm")
      (description "Test Point 测试点")
      (libsource (lib "easyedapro") (part "Test-Point"))
    )
    (comp (ref "U2")
      (value "TB67S249FTG,EL")
      (footprint "easyedapro:P-VQFN-48_L7.0-W7.0-P0.50-BL-EP5.5")
      (fields (field (name "Manufacturer") "TOSHIBA(东芝)"))
      (libsource (lib "easyedapro") (part "TB67S249FTG,EL"))
    )
    (comp (ref "U3")
      (value "TB67S249FTG,EL")
      (footprint "easyedapro:P-VQFN-48_L7.0-W7.0-P0.50-BL-EP5.5")
      (fields (field (name "Manufacturer") "TOSHIBA(东芝)"))
      (libsource (lib "easyedapro") (part "TB67S249FTG,EL"))
    )
    (comp (ref "U4")
      (value "TB67S249FTG,EL")
      (footprint "easyedapro:P-VQFN-48_L7.0-W7.0-P0.50-BL-EP5.5")
      (fields (field (name "Manufacturer") "TOSHIBA(东芝)"))
      (libsource (lib "easyedapro") (part "TB67S249FTG,EL"))
    )
    (comp (ref "U5")
      (value "TB67S249FTG,EL")
      (footprint "easyedapro:P-VQFN-48_L7.0-W7.0-P0.50-BL-EP5.5")
      (fields (field (name "Manufacturer") "TOSHIBA(东芝)"))
      (libsource (lib "easyedapro") (part "TB67S249FTG,EL"))
    )
    (comp (ref "U6")
      (value "TB67S249FTG,EL")
      (footprint "easyedapro:P-VQFN-48_L7.0-W7.0-P0.50-BL-EP5.5")
      (fields (field (name "Manufacturer") "TOSHIBA(东芝)"))
      (libsource (lib "easyedapro") (part "TB67S249FTG,EL"))
    )
    (comp (ref "U7")
      (value "TB67S249FTG,EL")
      (footprint "easyedapro:P-VQFN-48_L7.0-W7.0-P0.50-BL-EP5.5")
      (fields (field (name "Manufacturer") "TOSHIBA(东芝)"))
      (libsource (lib "easyedapro") (part "TB67S249FTG,EL"))
    )
    (comp (ref "U8")
      (value "TB67S249FTG,EL")
      (footprint "easyedapro:P-VQFN-48_L7.0-W7.0-P0.50-BL-EP5.5")
      (fields (field (name "Manufacturer") "TOSHIBA(东芝)"))
      (libsource (lib "easyedapro") (part "TB67S249FTG,EL"))
    )
    (comp (ref "U29")
      (value "DAC53608RTER")
      (footprint "easyedapro:WQFN-16_L3.0-W3.0-P0.50-BL-EP1.7")
      (fields (field (name "Manufacturer") "TI(德州仪器)"))
      (libsource (lib "easyedapro") (part "DAC53608RTER"))
    )
    (comp (ref "U30")
      (value "MCP1799-5002H/DB")
      (footprint "easyedapro:SOT-223-3_L6.7-W3.7-P2.30-LS7.0-BR")
      (fields (field (name "Manufacturer") "MICROCHIP(美国微芯)"))
      (libsource (lib "easyedapro") (part "MCP1799-5002H/DB"))
    )
    (comp (ref "U31")
      (value "TPS2116DRLR")
      (footprint "easyedapro:SOT-583-8_L2.1-W1.6-P0.50-LS1.6-BL")
      (description "Features:Operation status indication")
      (fields (field (name "Manufacturer") "TI(德州仪器)"))
      (libsource (lib "easyedapro") (part "TPS2116DRLR"))
    )
    (comp (ref "C1")
      (value "2.2uF")
      (footprint "easyedapro:C0603")
      (description "Capacitance:2.2uF Tolerance:±10% Tolerance:±10% Voltage Rating:16V Temperature Coefficient:X5R")
      (fields
        (field (name "Manufacturer Part") "CL10A225KO8NNNC")
        (field (name "Manufacturer") "SAMSUNG(三星)")
      )
      (libsource (lib "easyedapro") (part "GRT188R61H225KE13D"))
    )
    (comp (ref "C3")
      (value "100nF")
      (footprint "easyedapro:C0603")
      (description "Capacitance:100nF Tolerance:±10% Tolerance:±10% Voltage Rating:50V Temperature Coefficient:X7R")
      (fields
        (field (name "Manufacturer Part") "CC0603KRX7R9BB104")
        (field (name "Manufacturer") "YAGEO(国巨)")
      )
      (libsource (lib "easyedapro") (part "CL10B104KB8NNNC"))
    )
    (comp (ref "C4")
      (value "100nF")
      (footprint "easyedapro:C0603")
      (description "Capacitance:100nF Tolerance:±10% Tolerance:±10% Voltage Rating:50V Temperature Coefficient:X7R")
      (fields
        (field (name "Manufacturer Part") "CC0603KRX7R9BB104")
        (field (name "Manufacturer") "YAGEO(国巨)")
      )
      (libsource (lib "easyedapro") (part "CL10B104KB8NNNC"))
    )
    (comp (ref "C5")
      (value "100nF")
      (footprint "easyedapro:C0603")
      (description "Capacitance:100nF Tolerance:±10% Tolerance:±10% Voltage Rating:50V Temperature Coefficient:X7R")
      (fields
        (field (name "Manufacturer Part") "CC0603KRX7R9BB104")
        (field (name "Manufacturer") "YAGEO(国巨)")
      )
      (libsource (lib "easyedapro") (part "CL10B104KB8NNNC"))
    )
    (comp (ref "C6")
      (value "100nF")
      (footprint "easyedapro:C0603")
      (description "Capacitance:100nF Tolerance:±10% Tolerance:±10% Voltage Rating:50V Temperature Coefficient:X7R")
      (fields
        (field (name "Manufacturer Part") "CC0603KRX7R9BB104")
        (field (name "Manufacturer") "YAGEO(国巨)")
      )
      (libsource (lib "easyedapro") (part "CL10B104KB8NNNC"))
    )
    (comp (ref "C8")
      (value "2.2uF")
      (footprint "easyedapro:C0603")
      (description "Capacitance:2.2uF Tolerance:±10% Tolerance:±10% Voltage Rating:16V Temperature Coefficient:X5R")
      (fields
        (field (name "Manufacturer Part") "CL10A225KO8NNNC")
        (field (name "Manufacturer") "SAMSUNG(三星)")
      )
      (libsource (lib "easyedapro") (part "GRT188R61H225KE13D"))
    )
    (comp (ref "C11")
      (value "4.7uF")
      (footprint "easyedapro:C0603")
      (description "Capacitance:4.7uF Tolerance:±10% Tolerance:±10% Voltage Rating:16V Temperature Coefficient:X5R")
      (fields
        (field (name "Manufacturer Part") "CL10A475KO8NNNC")
        (field (name "Manufacturer") "SAMSUNG(三星)")
      )
      (libsource (lib "easyedapro") (part "TCC0603X5R475K160CT"))
    )
    (comp (ref "C12")
      (value "100nF")
      (footprint "easyedapro:C0603")
      (description "Capacitance:100nF Tolerance:±10% Tolerance:±10% Voltage Rating:50V Temperature Coefficient:X7R")
      (fields
        (field (name "Manufacturer Part") "CC0603KRX7R9BB104")
        (field (name "Manufacturer") "YAGEO(国巨)")
      )
      (libsource (lib "easyedapro") (part "CL10B104KB8NNNC"))
    )
    (comp (ref "C13")
      (value "100nF")
      (footprint "easyedapro:C0603")
      (description "Capacitance:100nF Tolerance:±10% Tolerance:±10% Voltage Rating:50V Temperature Coefficient:X7R")
      (fields
        (field (name "Manufacturer Part") "CC0603KRX7R9BB104")
        (field (name "Manufacturer") "YAGEO(国巨)")
      )
      (libsource (lib "easyedapro") (part "CL10B104KB8NNNC"))
    )
    (comp (ref "C14")
      (value "1uF")
      (footprint "easyedapro:C0603")
      (description "Capacitance:1uF Tolerance:±10% Tolerance:±10% Voltage Rating:50V Temperature Coefficient:X5R")
      (fields
        (field (name "Manufacturer Part") "CL10A105KB8NNNC")
        (field (name "Manufacturer") "SAMSUNG(三星)")
      )
      (libsource (lib "easyedapro") (part "CL10A105KB8NNNC"))
    )
    (comp (ref "C26")
      (value "100nF")
      (footprint "easyedapro:C0805")
      (description "Capacitance:100nF Tolerance:±10% Tolerance:±10% Voltage Rating:100V Temperature Coefficient:X7R")
      (fields
        (field (name "Manufacturer Part") "CL21B104KCFNNNE")
        (field (name "Manufacturer") "SAMSUNG(三星)")
      )
      (libsource (lib "easyedapro") (part "C0805C104KMRECAUTO"))
    )
    (comp (ref "C27")
      (value "100nF")
      (footprint "easyedapro:C0805")
      (description "Capacitance:100nF Tolerance:±10% Tolerance:±10% Voltage Rating:100V Temperature Coefficient:X7R")
      (fields
        (field (name "Manufacturer Part") "CL21B104KCFNNNE")
        (field (name "Manufacturer") "SAMSUNG(三星)")
      )
      (libsource (lib "easyedapro") (part "C0805C104KMRECAUTO"))
    )
    (comp (ref "C28")
      (value "1uF")
      (footprint "easyedapro:C2220")
      (description "Capacitance:1uF Tolerance:±10% Tolerance:±10% Voltage Rating:100V Temperature Coefficient:X7R")
      (fields
        (field (name "Manufacturer Part") "HHV0805R7105K101NSLJ")
        (field (name "Manufacturer") "Chinocera(华瓷)")
      )
      (libsource (lib "easyedapro") (part "2220J0630105MXT"))
    )
    (comp (ref "C29")
      (value "1uF")
      (footprint "easyedapro:C2220")
      (description "Capacitance:1uF Tolerance:±10% Tolerance:±10% Voltage Rating:100V Temperature Coefficient:X7R")
      (fields
        (field (name "Manufacturer Part") "HHV0805R7105K101NSLJ")
        (field (name "Manufacturer") "Chinocera(华瓷)")
      )
      (libsource (lib "easyedapro") (part "2220J0630105MXT"))
    )
    (comp (ref "C30")
      (value "1uF")
      (footprint "easyedapro:C2220")
      (description "Capacitance:1uF Tolerance:±10% Tolerance:±10% Voltage Rating:100V Temperature Coefficient:X7R")
      (fields
        (field (name "Manufacturer Part") "HHV0805R7105K101NSLJ")
        (field (name "Manufacturer") "Chinocera(华瓷)")
      )
      (libsource (lib "easyedapro") (part "2220J0630105MXT"))
    )
    (comp (ref "C31")
      (value "1uF")
      (footprint "easyedapro:C2220")
      (description "Capacitance:1uF Tolerance:±10% Tolerance:±10% Voltage Rating:100V Temperature Coefficient:X7R")
      (fields
        (field (name "Manufacturer Part") "HHV0805R7105K101NSLJ")
        (field (name "Manufacturer") "Chinocera(华瓷)")
      )
      (libsource (lib "easyedapro") (part "2220J0630105MXT"))
    )
    (comp (ref "C32")
      (value "1uF")
      (footprint "easyedapro:C2220")
      (description "Capacitance:1uF Tolerance:±10% Tolerance:±10% Voltage Rating:100V Temperature Coefficient:X7R")
      (fields
        (field (name "Manufacturer Part") "HHV0805R7105K101NSLJ")
        (field (name "Manufacturer") "Chinocera(华瓷)")
      )
      (libsource (lib "easyedapro") (part "2220J0630105MXT"))
    )
    (comp (ref "C33")
      (value "1uF")
      (footprint "easyedapro:C2220")
      (description "Capacitance:1uF Tolerance:±10% Tolerance:±10% Voltage Rating:100V Temperature Coefficient:X7R")
      (fields
        (field (name "Manufacturer Part") "HHV0805R7105K101NSLJ")
        (field (name "Manufacturer") "Chinocera(华瓷)")
      )
      (libsource (lib "easyedapro") (part "2220J0630105MXT"))
    )
    (comp (ref "C34")
      (value "100nF")
      (footprint "easyedapro:C0805")
      (description "Capacitance:100nF Tolerance:±10% Tolerance:±10% Voltage Rating:100V Temperature Coefficient:X7R")
      (fields
        (field (name "Manufacturer Part") "CL21B104KCFNNNE")
        (field (name "Manufacturer") "SAMSUNG(三星)")
      )
      (libsource (lib "easyedapro") (part "C0805C104KMRECAUTO"))
    )
    (comp (ref "C35")
      (value "100nF")
      (footprint "easyedapro:C0805")
      (description "Capacitance:100nF Tolerance:±10% Tolerance:±10% Voltage Rating:100V Temperature Coefficient:X7R")
      (fields
        (field (name "Manufacturer Part") "CL21B104KCFNNNE")
        (field (name "Manufacturer") "SAMSUNG(三星)")
      )
      (libsource (lib "easyedapro") (part "C0805C104KMRECAUTO"))
    )
    (comp (ref "C36")
      (value "10uF")
      (footprint "easyedapro:C0805")
      (description "Capacitance:10uF Tolerance:±10% Tolerance:±10% Voltage Rating:25V Temperature Coefficient:X5R")
      (fields
        (field (name "Manufacturer Part") "CL21A106KAYNNNE")
        (field (name "Manufacturer") "SAMSUNG(三星)")
      )
      (libsource (lib "easyedapro") (part "CL21A106KAYNNNE"))
    )
    (comp (ref "C38")
      (value "10uF")
      (footprint "easyedapro:C0805")
      (description "Capacitance:10uF Tolerance:±10% Tolerance:±10% Voltage Rating:25V Temperature Coefficient:X5R")
      (fields
        (field (name "Manufacturer Part") "CL21A106KAYNNNE")
        (field (name "Manufacturer") "SAMSUNG(三星)")
      )
      (libsource (lib "easyedapro") (part "CL21A106KAYNNNE"))
    )
    (comp (ref "C39")
      (value "10uF")
      (footprint "easyedapro:C0805")
      (description "Capacitance:10uF Tolerance:±10% Tolerance:±10% Voltage Rating:25V Temperature Coefficient:X5R")
      (fields
        (field (name "Manufacturer Part") "CL21A106KAYNNNE")
        (field (name "Manufacturer") "SAMSUNG(三星)")
      )
      (libsource (lib "easyedapro") (part "CL21A106KAYNNNE"))
    )
    (comp (ref "C40")
      (value "10uF")
      (footprint "easyedapro:C0805")
      (description "Capacitance:10uF Tolerance:±10% Tolerance:±10% Voltage Rating:25V Temperature Coefficient:X5R")
      (fields
        (field (name "Manufacturer Part") "CL21A106KAYNNNE")
        (field (name "Manufacturer") "SAMSUNG(三星)")
      )
      (libsource (lib "easyedapro") (part "CL21A106KAYNNNE"))
    )
    (comp (ref "C43")
      (value "100nF")
      (footprint "easyedapro:C0603")
      (description "Capacitance:100nF Tolerance:±10% Tolerance:±10% Voltage Rating:50V Temperature Coefficient:X7R")
      (fields
        (field (name "Manufacturer Part") "CC0603KRX7R9BB104")
        (field (name "Manufacturer") "YAGEO(国巨)")
      )
      (libsource (lib "easyedapro") (part "CL10B104KB8NNNC"))
    )
    (comp (ref "C44")
      (value "10uF")
      (footprint "easyedapro:C0805")
      (description "Capacitance:10uF Tolerance:±10% Tolerance:±10% Voltage Rating:25V Temperature Coefficient:X5R")
      (fields
        (field (name "Manufacturer Part") "CL21A106KAYNNNE")
        (field (name "Manufacturer") "SAMSUNG(三星)")
      )
      (libsource (lib "easyedapro") (part "CL21A106KAYNNNE"))
    )
    (comp (ref "C45")
      (value "10uF")
      (footprint "easyedapro:C0805")
      (description "Capacitance:10uF Tolerance:±10% Tolerance:±10% Voltage Rating:25V Temperature Coefficient:X5R")
      (fields
        (field (name "Manufacturer Part") "CL21A106KAYNNNE")
        (field (name "Manufacturer") "SAMSUNG(三星)")
      )
      (libsource (lib "easyedapro") (part "CL21A106KAYNNNE"))
    )
    (comp (ref "C46")
      (value "22uF")
      (footprint "easyedapro:C0603")
      (description "Capacitance:22uF Tolerance:±20% Tolerance:±20% Voltage Rating:6.3V Temperature Coefficient:X5R")
      (fields
        (field (name "Manufacturer Part") "CL10A226MQ8NRNC")
        (field (name "Manufacturer") "SAMSUNG(三星)")
      )
      (libsource (lib "easyedapro") (part "CL10A226MQ8NRNC"))
    )
    (comp (ref "C47")
      (value "100nF")
      (footprint "easyedapro:C0603")
      (description "Capacitance:100nF Tolerance:±10% Tolerance:±10% Voltage Rating:50V Temperature Coefficient:X7R")
      (fields
        (field (name "Manufacturer Part") "CC0603KRX7R9BB104")
        (field (name "Manufacturer") "YAGEO(国巨)")
      )
      (libsource (lib "easyedapro") (part "CL10B104KB8NNNC"))
    )
    (comp (ref "CN8")
      (value "BH127VS-12-10-H25-L70-R")
      (footprint "easyedapro:CONN-SMD_10P-P1.27-V-M-R2-C5-LS5.8_BH127VS-12-10-H25-L70-R")
      (fields (field (name "Manufacturer") "XFCN(兴飞)"))
      (libsource (lib "easyedapro") (part "BH127VS-12-10-H25-L70-R"))
    )
    (comp (ref "D1")
      (value "USBLC6-2P6")
      (footprint "easyedapro:SOT-563_L1.6-W1.2-P0.50-LS1.6-BL")
      (fields (field (name "Manufacturer") "R+O(宏嘉诚)"))
      (libsource (lib "easyedapro") (part "USBLC6-2P6_C49451919"))
    )
    (comp (ref "D2")
      (value "USBLC6-2P6")
      (footprint "easyedapro:SOT-563_L1.6-W1.2-P0.50-LS1.6-BL")
      (fields (field (name "Manufacturer") "R+O(宏嘉诚)"))
      (libsource (lib "easyedapro") (part "USBLC6-2P6_C49451919"))
    )
    (comp (ref "H1")
      (value "PZ254V-11-02P")
      (footprint "easyedapro:HDR-TH_2P-P2.54-V-M")
      (fields (field (name "Manufacturer") "XFCN(兴飞)"))
      (libsource (lib "easyedapro") (part "PZ254V-11-02P"))
    )
    (comp (ref "H2")
      (value "PZ254V-11-02P")
      (footprint "easyedapro:HDR-TH_2P-P2.54-V-M")
      (fields (field (name "Manufacturer") "XFCN(兴飞)"))
      (libsource (lib "easyedapro") (part "PZ254V-11-02P"))
    )
    (comp (ref "H3")
      (value "PZ254V-11-02P")
      (footprint "easyedapro:HDR-TH_2P-P2.54-V-M")
      (fields (field (name "Manufacturer") "XFCN(兴飞)"))
      (libsource (lib "easyedapro") (part "PZ254V-11-02P"))
    )
    (comp (ref "H5")
      (value "P6E32E-602530-B1P")
      (footprint "easyedapro:HDR-TH_32P-P2.00-V-M-R2-C16-S2.00")
      (fields (field (name "Manufacturer") "CHIN-BAN(勤本)"))
      (libsource (lib "easyedapro") (part "210-2S-2*16PL=8.8MM Gold-plated black"))
    )
    (comp (ref "H6")
      (value "P6E32E-602530-B1P")
      (footprint "easyedapro:HDR-TH_32P-P2.00-V-M-R2-C16-S2.00")
      (fields (field (name "Manufacturer") "CHIN-BAN(勤本)"))
      (libsource (lib "easyedapro") (part "210-2S-2*16PL=8.8MM Gold-plated black"))
    )
    (comp (ref "H7")
      (value "PZ254V-11-02P")
      (footprint "easyedapro:HDR-TH_2P-P2.54-V-M")
      (fields (field (name "Manufacturer") "XFCN(兴飞)"))
      (libsource (lib "easyedapro") (part "PZ254V-11-02P"))
    )
    (comp (ref "L1")
      (value "22uH")
      (footprint "easyedapro:IND-SMD_L10.0-W10.0-LS11.0")
      (fields (field (name "Manufacturer Part") "FXL1040-220-M") (field (name "Manufacturer") "cjiang(长江微电)"))
      (libsource (lib "easyedapro") (part "FXL1040-220-M"))
    )
    (comp (ref "L2")
      (value "22uH")
      (footprint "easyedapro:IND-SMD_L10.0-W10.0-LS11.0")
      (fields (field (name "Manufacturer Part") "FXL1040-220-M") (field (name "Manufacturer") "cjiang(长江微电)"))
      (libsource (lib "easyedapro") (part "FXL1040-220-M"))
    )
    (comp (ref "L3")
      (value "2.2uH")
      (footprint "easyedapro:L0805")
      (fields (field (name "Manufacturer Part") "CMI201209U2R2KT") (field (name "Manufacturer") "FH(风华)"))
      (libsource (lib "easyedapro") (part "CMI201209U2R2KT"))
    )
    (comp (ref "LED1")
      (value "KT-0603R")
      (footprint "easyedapro:LED-SMD_L1.6-W0.8-R-RD")
      (fields (field (name "Manufacturer") "KENTO"))
      (libsource (lib "easyedapro") (part "KT-0603R"))
    )
    (comp (ref "LED2")
      (value "KT-0603R")
      (footprint "easyedapro:LED-SMD_L1.6-W0.8-R-RD")
      (fields (field (name "Manufacturer") "KENTO"))
      (libsource (lib "easyedapro") (part "KT-0603R"))
    )
    (comp (ref "Q1")
      (value "MMBT3904")
      (footprint "easyedapro:SOT-23-3_L2.9-W1.3-P1.90-LS2.4-BR")
      (fields (field (name "Manufacturer") "CCX(晁禾)"))
      (libsource (lib "easyedapro") (part "MMBT3904_C51953474"))
    )
    (comp (ref "Q2")
      (value "MMBT3904")
      (footprint "easyedapro:SOT-23-3_L2.9-W1.3-P1.90-LS2.4-BR")
      (fields (field (name "Manufacturer") "CCX(晁禾)"))
      (libsource (lib "easyedapro") (part "MMBT3904_C51953474"))
    )
    (comp (ref "Q4")
      (value "MMBT3904")
      (footprint "easyedapro:SOT-23-3_L2.9-W1.3-P1.90-LS2.4-BR")
      (fields (field (name "Manufacturer") "CCX(晁禾)"))
      (libsource (lib "easyedapro") (part "MMBT3904_C51953474"))
    )
    (comp (ref "Q5")
      (value "MMBT3904")
      (footprint "easyedapro:SOT-23-3_L2.9-W1.3-P1.90-LS2.4-BR")
      (fields (field (name "Manufacturer") "CCX(晁禾)"))
      (libsource (lib "easyedapro") (part "MMBT3904_C51953474"))
    )
    (comp (ref "Q6")
      (value "MMBT3904")
      (footprint "easyedapro:SOT-23-3_L2.9-W1.3-P1.90-LS2.4-BR")
      (fields (field (name "Manufacturer") "CCX(晁禾)"))
      (libsource (lib "easyedapro") (part "MMBT3904_C51953474"))
    )
    (comp (ref "R106")
      (value "10kΩ")
      (footprint "easyedapro:R0603")
      (fields
        (field (name "Manufacturer Part") "0603WAF1002T5E")
        (field (name "Manufacturer") "UNI-ROYAL(厚声)")
      )
      (libsource (lib "easyedapro") (part "FRC0603J103TS"))
    )
    (comp (ref "R114")
      (value "10kΩ")
      (footprint "easyedapro:R0603")
      (fields
        (field (name "Manufacturer Part") "0603WAF1002T5E")
        (field (name "Manufacturer") "UNI-ROYAL(厚声)")
      )
      (libsource (lib "easyedapro") (part "FRC0603J103TS"))
    )
    (comp (ref "R115")
      (value "5.1kΩ")
      (footprint "easyedapro:R0805")
      (fields
        (field (name "Manufacturer Part") "0603WAF5101T5E")
        (field (name "Manufacturer") "UNI-ROYAL(厚声)")
      )
      (libsource (lib "easyedapro") (part "0805W8F5101T5E"))
    )
    (comp (ref "R116")
      (value "5.1kΩ")
      (footprint "easyedapro:R0805")
      (fields
        (field (name "Manufacturer Part") "0603WAF5101T5E")
        (field (name "Manufacturer") "UNI-ROYAL(厚声)")
      )
      (libsource (lib "easyedapro") (part "0805W8F5101T5E"))
    )
    (comp (ref "R117")
      (value "22kΩ")
      (footprint "easyedapro:R0603")
      (fields
        (field (name "Manufacturer Part") "0603WAF2202T5E")
        (field (name "Manufacturer") "UNI-ROYAL(厚声)")
      )
      (libsource (lib "easyedapro") (part "RC0603FR-0722K1L"))
    )
    (comp (ref "R118")
      (value "47kΩ")
      (footprint "easyedapro:R0603")
      (fields
        (field (name "Manufacturer Part") "0603WAF4702T5E")
        (field (name "Manufacturer") "UNI-ROYAL(厚声)")
      )
      (libsource (lib "easyedapro") (part "0603WAF4752T5E"))
    )
    (comp (ref "R130")
      (value "10kΩ")
      (footprint "easyedapro:R0603")
      (fields
        (field (name "Manufacturer Part") "0603WAF1002T5E")
        (field (name "Manufacturer") "UNI-ROYAL(厚声)")
      )
      (libsource (lib "easyedapro") (part "FRC0603J103TS"))
    )
    (comp (ref "R131")
      (value "10kΩ")
      (footprint "easyedapro:R0603")
      (fields
        (field (name "Manufacturer Part") "0603WAF1002T5E")
        (field (name "Manufacturer") "UNI-ROYAL(厚声)")
      )
      (libsource (lib "easyedapro") (part "FRC0603J103TS"))
    )
    (comp (ref "R132")
      (value "10kΩ")
      (footprint "easyedapro:R0603")
      (fields
        (field (name "Manufacturer Part") "0603WAF1002T5E")
        (field (name "Manufacturer") "UNI-ROYAL(厚声)")
      )
      (libsource (lib "easyedapro") (part "FRC0603J103TS"))
    )
    (comp (ref "R133")
      (value "10kΩ")
      (footprint "easyedapro:R0603")
      (fields
        (field (name "Manufacturer Part") "0603WAF1002T5E")
        (field (name "Manufacturer") "UNI-ROYAL(厚声)")
      )
      (libsource (lib "easyedapro") (part "FRC0603J103TS"))
    )
    (comp (ref "R134")
      (value "100kΩ")
      (footprint "easyedapro:R0402")
      (fields
        (field (name "Manufacturer Part") "0402WGF1003TCE")
        (field (name "Manufacturer") "UNI-ROYAL(厚声)")
      )
      (libsource (lib "easyedapro") (part "0402WGF1003TCE"))
    )
    (comp (ref "R135")
      (value "6.8kΩ")
      (footprint "easyedapro:R0603")
      (fields
        (field (name "Manufacturer Part") "0603WAF6801T5E")
        (field (name "Manufacturer") "UNI-ROYAL(厚声)")
      )
      (libsource (lib "easyedapro") (part "0603WAF6801T5E"))
    )
    (comp (ref "R136")
      (value "100kΩ")
      (footprint "easyedapro:R0402")
      (fields
        (field (name "Manufacturer Part") "0402WGF1003TCE")
        (field (name "Manufacturer") "UNI-ROYAL(厚声)")
      )
      (libsource (lib "easyedapro") (part "0402WGF1003TCE"))
    )
    (comp (ref "R137")
      (value "33kΩ")
      (footprint "easyedapro:R0402")
      (fields
        (field (name "Manufacturer Part") "0402WGF3302TCE")
        (field (name "Manufacturer") "UNI-ROYAL(厚声)")
      )
      (libsource (lib "easyedapro") (part "0402WGF3302TCE"))
    )
    (comp (ref "R138")
      (value "10kΩ")
      (footprint "easyedapro:R0603")
      (fields
        (field (name "Manufacturer Part") "0603WAF1002T5E")
        (field (name "Manufacturer") "UNI-ROYAL(厚声)")
      )
      (libsource (lib "easyedapro") (part "FRC0603J103TS"))
    )
    (comp (ref "R139")
      (value "10kΩ")
      (footprint "easyedapro:R0603")
      (fields
        (field (name "Manufacturer Part") "0603WAF1002T5E")
        (field (name "Manufacturer") "UNI-ROYAL(厚声)")
      )
      (libsource (lib "easyedapro") (part "FRC0603J103TS"))
    )
    (comp (ref "R140")
      (value "5.1kΩ")
      (footprint "easyedapro:R0805")
      (fields
        (field (name "Manufacturer Part") "0603WAF5101T5E")
        (field (name "Manufacturer") "UNI-ROYAL(厚声)")
      )
      (libsource (lib "easyedapro") (part "0805W8F5101T5E"))
    )
    (comp (ref "R141")
      (value "5.1kΩ")
      (footprint "easyedapro:R0805")
      (fields
        (field (name "Manufacturer Part") "0603WAF5101T5E")
        (field (name "Manufacturer") "UNI-ROYAL(厚声)")
      )
      (libsource (lib "easyedapro") (part "0805W8F5101T5E"))
    )
    (comp (ref "R144")
      (value "10kΩ")
      (footprint "easyedapro:R0603")
      (fields
        (field (name "Manufacturer Part") "0603WAF1002T5E")
        (field (name "Manufacturer") "UNI-ROYAL(厚声)")
      )
      (libsource (lib "easyedapro") (part "FRC0603J103TS"))
    )
    (comp (ref "R148")
      (value "10kΩ")
      (footprint "easyedapro:R0603")
      (fields
        (field (name "Manufacturer Part") "0603WAF1002T5E")
        (field (name "Manufacturer") "UNI-ROYAL(厚声)")
      )
      (libsource (lib "easyedapro") (part "FRC0603J103TS"))
    )
    (comp (ref "R149")
      (value "10kΩ")
      (footprint "easyedapro:R0603")
      (fields
        (field (name "Manufacturer Part") "0603WAF1002T5E")
        (field (name "Manufacturer") "UNI-ROYAL(厚声)")
      )
      (libsource (lib "easyedapro") (part "FRC0603J103TS"))
    )
    (comp (ref "R151")
      (value "10kΩ")
      (footprint "easyedapro:R0603")
      (fields
        (field (name "Manufacturer Part") "0603WAF1002T5E")
        (field (name "Manufacturer") "UNI-ROYAL(厚声)")
      )
      (libsource (lib "easyedapro") (part "FRC0603J103TS"))
    )
    (comp (ref "R152")
      (value "100kΩ")
      (footprint "easyedapro:R0603")
      (fields
        (field (name "Manufacturer Part") "0603WAF1003T5E")
        (field (name "Manufacturer") "UNI-ROYAL(厚声)")
      )
      (libsource (lib "easyedapro") (part "FRC0603J104 TS"))
    )
    (comp (ref "R153")
      (value "100kΩ")
      (footprint "easyedapro:R0603")
      (fields
        (field (name "Manufacturer Part") "0603WAF1003T5E")
        (field (name "Manufacturer") "UNI-ROYAL(厚声)")
      )
      (libsource (lib "easyedapro") (part "FRC0603J104 TS"))
    )
    (comp (ref "R154")
      (value "100kΩ")
      (footprint "easyedapro:R0603")
      (fields
        (field (name "Manufacturer Part") "0603WAF1003T5E")
        (field (name "Manufacturer") "UNI-ROYAL(厚声)")
      )
      (libsource (lib "easyedapro") (part "FRC0603J104 TS"))
    )
    (comp (ref "R155")
      (value "43kΩ")
      (footprint "easyedapro:R0603")
      (fields
        (field (name "Manufacturer Part") "0603WAF4302T5E")
        (field (name "Manufacturer") "UNI-ROYAL(厚声)")
      )
      (libsource (lib "easyedapro") (part "0603WAF4302T5E"))
    )
    (comp (ref "R156")
      (value "10kΩ")
      (footprint "easyedapro:R0603")
      (fields
        (field (name "Manufacturer Part") "0603WAF1002T5E")
        (field (name "Manufacturer") "UNI-ROYAL(厚声)")
      )
      (libsource (lib "easyedapro") (part "FRC0603J103TS"))
    )
    (comp (ref "R157")
      (value "10kΩ")
      (footprint "easyedapro:R0603")
      (fields
        (field (name "Manufacturer Part") "0603WAF1002T5E")
        (field (name "Manufacturer") "UNI-ROYAL(厚声)")
      )
      (libsource (lib "easyedapro") (part "FRC0603J103TS"))
    )
    (comp (ref "R158")
      (value "43kΩ")
      (footprint "easyedapro:R0603")
      (fields
        (field (name "Manufacturer Part") "0603WAF4302T5E")
        (field (name "Manufacturer") "UNI-ROYAL(厚声)")
      )
      (libsource (lib "easyedapro") (part "0603WAF4302T5E"))
    )
    (comp (ref "R159")
      (value "10kΩ")
      (footprint "easyedapro:R0603")
      (fields
        (field (name "Manufacturer Part") "0603WAF1002T5E")
        (field (name "Manufacturer") "UNI-ROYAL(厚声)")
      )
      (libsource (lib "easyedapro") (part "FRC0603J103TS"))
    )
    (comp (ref "R160")
      (value "100kΩ")
      (footprint "easyedapro:R0603")
      (fields
        (field (name "Manufacturer Part") "0603WAF1003T5E")
        (field (name "Manufacturer") "UNI-ROYAL(厚声)")
      )
      (libsource (lib "easyedapro") (part "FRC0603J104 TS"))
    )
    (comp (ref "R161")
      (value "10kΩ")
      (footprint "easyedapro:R0603")
      (fields
        (field (name "Manufacturer Part") "0603WAF1002T5E")
        (field (name "Manufacturer") "UNI-ROYAL(厚声)")
      )
      (libsource (lib "easyedapro") (part "FRC0603J103TS"))
    )
    (comp (ref "R163")
      (value "22Ω")
      (footprint "easyedapro:R0402")
      (fields
        (field (name "Manufacturer Part") "0402WGF220JTCE")
        (field (name "Manufacturer") "UNI-ROYAL(厚声)")
      )
      (libsource (lib "easyedapro") (part "0402WGF220JTCE"))
    )
    (comp (ref "R164")
      (value "22Ω")
      (footprint "easyedapro:R0402")
      (fields
        (field (name "Manufacturer Part") "0402WGF220JTCE")
        (field (name "Manufacturer") "UNI-ROYAL(厚声)")
      )
      (libsource (lib "easyedapro") (part "0402WGF220JTCE"))
    )
    (comp (ref "R165")
      (value "10kΩ")
      (footprint "easyedapro:R0603")
      (fields
        (field (name "Manufacturer Part") "0603WAF1002T5E")
        (field (name "Manufacturer") "UNI-ROYAL(厚声)")
      )
      (libsource (lib "easyedapro") (part "FRC0603J103TS"))
    )
    (comp (ref "R166")
      (value "100kΩ")
      (footprint "easyedapro:R0603")
      (fields
        (field (name "Manufacturer Part") "0603WAF1003T5E")
        (field (name "Manufacturer") "UNI-ROYAL(厚声)")
      )
      (libsource (lib "easyedapro") (part "FRC0603J104 TS"))
    )
    (comp (ref "R167")
      (value "10kΩ")
      (footprint "easyedapro:R0603")
      (fields
        (field (name "Manufacturer Part") "0603WAF1002T5E")
        (field (name "Manufacturer") "UNI-ROYAL(厚声)")
      )
      (libsource (lib "easyedapro") (part "FRC0603J103TS"))
    )
    (comp (ref "R168")
      (value "10kΩ")
      (footprint "easyedapro:R0603")
      (fields
        (field (name "Manufacturer Part") "0603WAF1002T5E")
        (field (name "Manufacturer") "UNI-ROYAL(厚声)")
      )
      (libsource (lib "easyedapro") (part "FRC0603J103TS"))
    )
    (comp (ref "R169")
      (value "10kΩ")
      (footprint "easyedapro:R0603")
      (fields
        (field (name "Manufacturer Part") "0603WAF1002T5E")
        (field (name "Manufacturer") "UNI-ROYAL(厚声)")
      )
      (libsource (lib "easyedapro") (part "FRC0603J103TS"))
    )
    (comp (ref "R171")
      (value "10kΩ")
      (footprint "easyedapro:R0603")
      (fields
        (field (name "Manufacturer Part") "0603WAF1002T5E")
        (field (name "Manufacturer") "UNI-ROYAL(厚声)")
      )
      (libsource (lib "easyedapro") (part "FRC0603J103TS"))
    )
    (comp (ref "R172")
      (value "5.1kΩ")
      (footprint "easyedapro:R0805")
      (fields
        (field (name "Manufacturer Part") "0603WAF5101T5E")
        (field (name "Manufacturer") "UNI-ROYAL(厚声)")
      )
      (libsource (lib "easyedapro") (part "0805W8F5101T5E"))
    )
    (comp (ref "R173")
      (value "5.1kΩ")
      (footprint "easyedapro:R0805")
      (fields
        (field (name "Manufacturer Part") "0603WAF5101T5E")
        (field (name "Manufacturer") "UNI-ROYAL(厚声)")
      )
      (libsource (lib "easyedapro") (part "0805W8F5101T5E"))
    )
    (comp (ref "R174")
      (value "5.1kΩ")
      (footprint "easyedapro:R0805")
      (fields
        (field (name "Manufacturer Part") "0603WAF5101T5E")
        (field (name "Manufacturer") "UNI-ROYAL(厚声)")
      )
      (libsource (lib "easyedapro") (part "0805W8F5101T5E"))
    )
    (comp (ref "R175")
      (value "5.1kΩ")
      (footprint "easyedapro:R0805")
      (fields
        (field (name "Manufacturer Part") "0603WAF5101T5E")
        (field (name "Manufacturer") "UNI-ROYAL(厚声)")
      )
      (libsource (lib "easyedapro") (part "0805W8F5101T5E"))
    )
    (comp (ref "R176")
      (value "10kΩ")
      (footprint "easyedapro:R0603")
      (fields
        (field (name "Manufacturer Part") "0603WAF1002T5E")
        (field (name "Manufacturer") "UNI-ROYAL(厚声)")
      )
      (libsource (lib "easyedapro") (part "FRC0603J103TS"))
    )
    (comp (ref "R177")
      (value "10kΩ")
      (footprint "easyedapro:R0603")
      (fields
        (field (name "Manufacturer Part") "0603WAF1002T5E")
        (field (name "Manufacturer") "UNI-ROYAL(厚声)")
      )
      (libsource (lib "easyedapro") (part "FRC0603J103TS"))
    )
    (comp (ref "R178")
      (value "10kΩ")
      (footprint "easyedapro:R0603")
      (fields
        (field (name "Manufacturer Part") "0603WAF1002T5E")
        (field (name "Manufacturer") "UNI-ROYAL(厚声)")
      )
      (libsource (lib "easyedapro") (part "FRC0603J103TS"))
    )
    (comp (ref "R180")
      (value "10kΩ")
      (footprint "easyedapro:R0603")
      (fields
        (field (name "Manufacturer Part") "0603WAF1002T5E")
        (field (name "Manufacturer") "UNI-ROYAL(厚声)")
      )
      (libsource (lib "easyedapro") (part "FRC0603J103TS"))
    )
    (comp (ref "R181")
      (value "10kΩ")
      (footprint "easyedapro:R0603")
      (fields
        (field (name "Manufacturer Part") "0603WAF1002T5E")
        (field (name "Manufacturer") "UNI-ROYAL(厚声)")
      )
      (libsource (lib "easyedapro") (part "FRC0603J103TS"))
    )
    (comp (ref "R185")
      (value "10kΩ")
      (footprint "easyedapro:R0603")
      (fields
        (field (name "Manufacturer Part") "0603WAF1002T5E")
        (field (name "Manufacturer") "UNI-ROYAL(厚声)")
      )
      (libsource (lib "easyedapro") (part "FRC0603J103TS"))
    )
    (comp (ref "SW15")
      (value "SS12D07VG4 087")
      (footprint "easyedapro:SW-TH_SS12D07VG4")
      (fields (field (name "Manufacturer") "SHOU HAN(首韩)"))
      (libsource (lib "easyedapro") (part "SS12D07VG4 087"))
    )
    (comp (ref "SW16")
      (value "SS12D07VG4 087")
      (footprint "easyedapro:SW-TH_SS12D07VG4")
      (fields (field (name "Manufacturer") "SHOU HAN(首韩)"))
      (libsource (lib "easyedapro") (part "SS12D07VG4 087"))
    )
    (comp (ref "SW17")
      (value "TS-1088-AR02016")
      (footprint "easyedapro:SW-SMD_L3.9-W3.0-P4.45")
      (fields (field (name "Manufacturer") "XUNPU(讯普)"))
      (libsource (lib "easyedapro") (part "TS-1088-AR02016"))
    )
    (comp (ref "SW18")
      (value "TS-1088-AR02016")
      (footprint "easyedapro:SW-SMD_L3.9-W3.0-P4.45")
      (fields (field (name "Manufacturer") "XUNPU(讯普)"))
      (libsource (lib "easyedapro") (part "TS-1088-AR02016"))
    )
    (comp (ref "SW19")
      (value "TS-1088-AR02016")
      (footprint "easyedapro:SW-SMD_L3.9-W3.0-P4.45")
      (fields (field (name "Manufacturer") "XUNPU(讯普)"))
      (libsource (lib "easyedapro") (part "TS-1088-AR02016"))
    )
    (comp (ref "TP29")
      (value "~")
      (footprint "easyedapro:Test-Point-0.5mm")
      (description "Test Point 测试点")
      (libsource (lib "easyedapro") (part "Test-Point"))
    )
    (comp (ref "TP30")
      (value "~")
      (footprint "easyedapro:Test-Point-0.5mm")
      (description "Test Point 测试点")
      (libsource (lib "easyedapro") (part "Test-Point"))
    )
    (comp (ref "U1")
      (value "STM32F446RET6")
      (footprint "easyedapro:LQFP-64_L10.0-W10.0-P0.50-LS12.0-BL")
      (fields (field (name "Manufacturer") "ST(意法半导体)"))
      (libsource (lib "easyedapro") (part "STM32F446RET6"))
    )
    (comp (ref "U9")
      (value "2.4GHz")
      (footprint "easyedapro:WIRELM-SMD_ESP32-S3-WROOM-1")
      (fields
        (field (name "Manufacturer Part") "ESP32-S3-WROOM-1-N16R8")
        (field (name "Manufacturer") "ESPRESSIF(乐鑫)")
      )
      (libsource (lib "easyedapro") (part "ESP32-S3-WROOM-1(N16R8)"))
    )
    (comp (ref "U10")
      (value "MCP23017-E/SS")
      (footprint "easyedapro:SSOP-28_L10.2-W5.3-P0.65-LS7.8-BL")
      (fields (field (name "Manufacturer") "MICROCHIP(美国微芯)"))
      (libsource (lib "easyedapro") (part "MCP23017-E/SS"))
    )
    (comp (ref "U11")
      (value "MCP23017-E/SS")
      (footprint "easyedapro:SSOP-28_L10.2-W5.3-P0.65-LS7.8-BL")
      (fields (field (name "Manufacturer") "MICROCHIP(美国微芯)"))
      (libsource (lib "easyedapro") (part "MCP23017-E/SS"))
    )
    (comp (ref "U12")
      (value "MCP23017-E/SS")
      (footprint "easyedapro:SSOP-28_L10.2-W5.3-P0.65-LS7.8-BL")
      (fields (field (name "Manufacturer") "MICROCHIP(美国微芯)"))
      (libsource (lib "easyedapro") (part "MCP23017-E/SS"))
    )
    (comp (ref "U13")
      (value "CP2102N-A02-GQFN28R")
      (footprint "easyedapro:QFN-28_L5.0-W5.0-P0.50-TL-EP3.3")
      (fields (field (name "Manufacturer") "SKYWORKS/SILICON LABS(芯科)"))
      (libsource (lib "easyedapro") (part "CP2102N-A02-GQFN28R"))
    )
    (comp (ref "U15")
      (value "LMR51625XDDCR")
      (footprint "easyedapro:SOT-23-6_L2.9-W1.6-P0.95-LS2.9-BL")
      (fields (field (name "Manufacturer") "TI(德州仪器)"))
      (libsource (lib "easyedapro") (part "LMR51625XDDCR_C44750835"))
    )
    (comp (ref "U16")
      (value "LMR51625XDDCR")
      (footprint "easyedapro:SOT-23-6_L2.9-W1.6-P0.95-LS2.9-BL")
      (fields (field (name "Manufacturer") "TI(德州仪器)"))
      (libsource (lib "easyedapro") (part "LMR51625XDDCR_C44750835"))
    )
    (comp (ref "U18")
      (value "ZX-PZ2.54-2-2PZZ")
      (footprint "easyedapro:HDR-TH_4P-P2.54-V-M-R2-C2-S2.54")
      (fields (field (name "Manufacturer") "Megastar(兆星)"))
      (libsource (lib "easyedapro") (part "ZX-PZ2.54-2-2PZZ"))
    )
    (comp (ref "U19")
      (value "ZX-PZ2.54-2-2PZZ")
      (footprint "easyedapro:HDR-TH_4P-P2.54-V-M-R2-C2-S2.54")
      (fields (field (name "Manufacturer") "Megastar(兆星)"))
      (libsource (lib "easyedapro") (part "ZX-PZ2.54-2-2PZZ"))
    )
    (comp (ref "U20")
      (value "TCA9548APWR")
      (footprint "easyedapro:TSSOP-24_L7.8-W4.4-P0.65-LS6.4-BL")
      (fields (field (name "Manufacturer") "TI(德州仪器)"))
      (libsource (lib "easyedapro") (part "TCA9548APWR"))
    )
    (comp (ref "U21")
      (value "TCA9548APWR")
      (footprint "easyedapro:TSSOP-24_L7.8-W4.4-P0.65-LS6.4-BL")
      (fields (field (name "Manufacturer") "TI(德州仪器)"))
      (libsource (lib "easyedapro") (part "TCA9548APWR"))
    )
    (comp (ref "U22")
      (value "TPS563252DRLR")
      (footprint "easyedapro:SOT-563-6_L1.6-W1.2-P0.50-LS1.6-BL")
      (fields (field (name "Manufacturer") "TI(德州仪器)"))
      (libsource (lib "easyedapro") (part "TPS563252DRLR"))
    )
    (comp (ref "U23")
      (value "TPS2116DRLR")
      (footprint "easyedapro:SOT-583-8_L2.1-W1.6-P0.50-LS1.6-BL")
      (description "Features:Operation status indication")
      (fields (field (name "Manufacturer") "TI(德州仪器)"))
      (libsource (lib "easyedapro") (part "TPS2116DRLR"))
    )
    (comp (ref "U24")
      (value "TMP112DQDRLRQ1")
      (footprint "easyedapro:SOT-563-6_L1.6-W1.2-P0.50-LS1.6-BL")
      (fields (field (name "Manufacturer") "TI(德州仪器)"))
      (libsource (lib "easyedapro") (part "TMP112DQDRLRQ1"))
    )
    (comp (ref "U25")
      (value "TMP112DQDRLRQ1")
      (footprint "easyedapro:SOT-563-6_L1.6-W1.2-P0.50-LS1.6-BL")
      (fields (field (name "Manufacturer") "TI(德州仪器)"))
      (libsource (lib "easyedapro") (part "TMP112DQDRLRQ1"))
    )
    (comp (ref "U26")
      (value "TPS2116DRLR")
      (footprint "easyedapro:SOT-583-8_L2.1-W1.6-P0.50-LS1.6-BL")
      (description "Features:Operation status indication")
      (fields (field (name "Manufacturer") "TI(德州仪器)"))
      (libsource (lib "easyedapro") (part "TPS2116DRLR"))
    )
    (comp (ref "USB1")
      (value "TYPE-C 16PIN 2MD(073)")
      (footprint "easyedapro:USB-C-SMD_TYPE-C-16PIN-2MD-073")
      (fields (field (name "Manufacturer") "SHOU HAN(首韩)"))
      (libsource (lib "easyedapro") (part "TYPE-C 16PIN 2MD(073)"))
    )
    (comp (ref "USB2")
      (value "TYPE-C 16PIN 2MD(073)")
      (footprint "easyedapro:USB-C-SMD_TYPE-C-16PIN-2MD-073")
      (fields (field (name "Manufacturer") "SHOU HAN(首韩)"))
      (libsource (lib "easyedapro") (part "TYPE-C 16PIN 2MD(073)"))
    )
    (comp (ref "DP1")
      (value "DSHP04TSGER")
      (footprint "easyedapro:SW-SMD_8P-L6.7-W5.4-P1.27-LS8.4")
      (fields (field (name "Manufacturer") "康深"))
      (libsource (lib "easyedapro") (part "DSHP04TSGER_C3293144"))
    )
    (comp (ref "DP2")
      (value "DSHP04TSGER")
      (footprint "easyedapro:SW-SMD_8P-L6.7-W5.4-P1.27-LS8.4")
      (fields (field (name "Manufacturer") "康深"))
      (libsource (lib "easyedapro") (part "DSHP04TSGER_C3293144"))
    )
    (comp (ref "DP3")
      (value "DSHP04TSGER")
      (footprint "easyedapro:SW-SMD_8P-L6.7-W5.4-P1.27-LS8.4")
      (fields (field (name "Manufacturer") "康深"))
      (libsource (lib "easyedapro") (part "DSHP04TSGER_C3293144"))
    )
    (comp (ref "DP4")
      (value "DSHP04TSGER")
      (footprint "easyedapro:SW-SMD_8P-L6.7-W5.4-P1.27-LS8.4")
      (fields (field (name "Manufacturer") "康深"))
      (libsource (lib "easyedapro") (part "DSHP04TSGER_C3293144"))
    )
    (comp (ref "DP5")
      (value "DSHP04TSGER")
      (footprint "easyedapro:SW-SMD_8P-L6.7-W5.4-P1.27-LS8.4")
      (fields (field (name "Manufacturer") "康深"))
      (libsource (lib "easyedapro") (part "DSHP04TSGER_C3293144"))
    )
    (comp (ref "DP6")
      (value "DSHP04TSGER")
      (footprint "easyedapro:SW-SMD_8P-L6.7-W5.4-P1.27-LS8.4")
      (fields (field (name "Manufacturer") "康深"))
      (libsource (lib "easyedapro") (part "DSHP04TSGER_C3293144"))
    )
    (comp (ref "DP7")
      (value "DSHP04TSGER")
      (footprint "easyedapro:SW-SMD_8P-L6.7-W5.4-P1.27-LS8.4")
      (fields (field (name "Manufacturer") "康深"))
      (libsource (lib "easyedapro") (part "DSHP04TSGER_C3293144"))
    )
    (comp (ref "DP8")
      (value "DSHP04TSGER")
      (footprint "easyedapro:SW-SMD_8P-L6.7-W5.4-P1.27-LS8.4")
      (fields (field (name "Manufacturer") "康深"))
      (libsource (lib "easyedapro") (part "DSHP04TSGER_C3293144"))
    )
    (comp (ref "DP9")
      (value "DSHP04TSGER")
      (footprint "easyedapro:SW-SMD_8P-L6.7-W5.4-P1.27-LS8.4")
      (fields (field (name "Manufacturer") "康深"))
      (libsource (lib "easyedapro") (part "DSHP04TSGER_C3293144"))
    )
    (comp (ref "DP10")
      (value "DSHP04TSGER")
      (footprint "easyedapro:SW-SMD_8P-L6.7-W5.4-P1.27-LS8.4")
      (fields (field (name "Manufacturer") "康深"))
      (libsource (lib "easyedapro") (part "DSHP04TSGER_C3293144"))
    )
    (comp (ref "DP11")
      (value "DSHP04TSGER")
      (footprint "easyedapro:SW-SMD_8P-L6.7-W5.4-P1.27-LS8.4")
      (fields (field (name "Manufacturer") "康深"))
      (libsource (lib "easyedapro") (part "DSHP04TSGER_C3293144"))
    )
    (comp (ref "DP12")
      (value "DSHP04TSGER")
      (footprint "easyedapro:SW-SMD_8P-L6.7-W5.4-P1.27-LS8.4")
      (fields (field (name "Manufacturer") "康深"))
      (libsource (lib "easyedapro") (part "DSHP04TSGER_C3293144"))
    )
    (comp (ref "DP13")
      (value "DSHP04TSGER")
      (footprint "easyedapro:SW-SMD_8P-L6.7-W5.4-P1.27-LS8.4")
      (fields (field (name "Manufacturer") "康深"))
      (libsource (lib "easyedapro") (part "DSHP04TSGER_C3293144"))
    )
    (comp (ref "DP14")
      (value "DSHP04TSGER")
      (footprint "easyedapro:SW-SMD_8P-L6.7-W5.4-P1.27-LS8.4")
      (fields (field (name "Manufacturer") "康深"))
      (libsource (lib "easyedapro") (part "DSHP04TSGER_C3293144"))
    )
    (comp (ref "DP15")
      (value "DSHP04TSGER")
      (footprint "easyedapro:SW-SMD_8P-L6.7-W5.4-P1.27-LS8.4")
      (fields (field (name "Manufacturer") "康深"))
      (libsource (lib "easyedapro") (part "DSHP04TSGER_C3293144"))
    )
    (comp (ref "DP16")
      (value "DSHP04TSGER")
      (footprint "easyedapro:SW-SMD_8P-L6.7-W5.4-P1.27-LS8.4")
      (fields (field (name "Manufacturer") "康深"))
      (libsource (lib "easyedapro") (part "DSHP04TSGER_C3293144"))
    )
    (comp (ref "DP17")
      (value "DSHP04TSGER")
      (footprint "easyedapro:SW-SMD_8P-L6.7-W5.4-P1.27-LS8.4")
      (fields (field (name "Manufacturer") "康深"))
      (libsource (lib "easyedapro") (part "DSHP04TSGER_C3293144"))
    )
    (comp (ref "DP18")
      (value "DSHP04TSGER")
      (footprint "easyedapro:SW-SMD_8P-L6.7-W5.4-P1.27-LS8.4")
      (fields (field (name "Manufacturer") "康深"))
      (libsource (lib "easyedapro") (part "DSHP04TSGER_C3293144"))
    )
    (comp (ref "DP19")
      (value "DSHP04TSGER")
      (footprint "easyedapro:SW-SMD_8P-L6.7-W5.4-P1.27-LS8.4")
      (fields (field (name "Manufacturer") "康深"))
      (libsource (lib "easyedapro") (part "DSHP04TSGER_C3293144"))
    )
    (comp (ref "DP20")
      (value "DSHP04TSGER")
      (footprint "easyedapro:SW-SMD_8P-L6.7-W5.4-P1.27-LS8.4")
      (fields (field (name "Manufacturer") "康深"))
      (libsource (lib "easyedapro") (part "DSHP04TSGER_C3293144"))
    )
    (comp (ref "DP21")
      (value "DSHP04TSGER")
      (footprint "easyedapro:SW-SMD_8P-L6.7-W5.4-P1.27-LS8.4")
      (fields (field (name "Manufacturer") "康深"))
      (libsource (lib "easyedapro") (part "DSHP04TSGER_C3293144"))
    )
    (comp (ref "R9")
      (value "10kΩ")
      (footprint "easyedapro:R0603")
      (fields
        (field (name "Manufacturer Part") "0603WAF1002T5E")
        (field (name "Manufacturer") "UNI-ROYAL(厚声)")
      )
      (libsource (lib "easyedapro") (part "FRC0603J103TS"))
    )
    (comp (ref "R10")
      (value "100kΩ")
      (footprint "easyedapro:R0603")
      (fields
        (field (name "Manufacturer Part") "0603WAF1003T5E")
        (field (name "Manufacturer") "UNI-ROYAL(厚声)")
      )
      (libsource (lib "easyedapro") (part "FRC0603J104 TS"))
    )
    (comp (ref "R11")
      (value "100kΩ")
      (footprint "easyedapro:R0603")
      (fields
        (field (name "Manufacturer Part") "0603WAF1003T5E")
        (field (name "Manufacturer") "UNI-ROYAL(厚声)")
      )
      (libsource (lib "easyedapro") (part "FRC0603J104 TS"))
    )
    (comp (ref "R12")
      (value "100kΩ")
      (footprint "easyedapro:R0603")
      (fields
        (field (name "Manufacturer Part") "0603WAF1003T5E")
        (field (name "Manufacturer") "UNI-ROYAL(厚声)")
      )
      (libsource (lib "easyedapro") (part "FRC0603J104 TS"))
    )
    (comp (ref "R13")
      (value "100kΩ")
      (footprint "easyedapro:R0603")
      (fields
        (field (name "Manufacturer Part") "0603WAF1003T5E")
        (field (name "Manufacturer") "UNI-ROYAL(厚声)")
      )
      (libsource (lib "easyedapro") (part "FRC0603J104 TS"))
    )
    (comp (ref "R14")
      (value "100kΩ")
      (footprint "easyedapro:R0603")
      (fields
        (field (name "Manufacturer Part") "0603WAF1003T5E")
        (field (name "Manufacturer") "UNI-ROYAL(厚声)")
      )
      (libsource (lib "easyedapro") (part "FRC0603J104 TS"))
    )
    (comp (ref "R15")
      (value "100kΩ")
      (footprint "easyedapro:R0603")
      (fields
        (field (name "Manufacturer Part") "0603WAF1003T5E")
        (field (name "Manufacturer") "UNI-ROYAL(厚声)")
      )
      (libsource (lib "easyedapro") (part "FRC0603J104 TS"))
    )
    (comp (ref "R64")
      (value "10kΩ")
      (footprint "easyedapro:R0603")
      (fields
        (field (name "Manufacturer Part") "0603WAF1002T5E")
        (field (name "Manufacturer") "UNI-ROYAL(厚声)")
      )
      (libsource (lib "easyedapro") (part "FRC0603J103TS"))
    )
    (comp (ref "R65")
      (value "100kΩ")
      (footprint "easyedapro:R0603")
      (fields
        (field (name "Manufacturer Part") "0603WAF1003T5E")
        (field (name "Manufacturer") "UNI-ROYAL(厚声)")
      )
      (libsource (lib "easyedapro") (part "FRC0603J104 TS"))
    )
    (comp (ref "R66")
      (value "100kΩ")
      (footprint "easyedapro:R0603")
      (fields
        (field (name "Manufacturer Part") "0603WAF1003T5E")
        (field (name "Manufacturer") "UNI-ROYAL(厚声)")
      )
      (libsource (lib "easyedapro") (part "FRC0603J104 TS"))
    )
    (comp (ref "R67")
      (value "100kΩ")
      (footprint "easyedapro:R0603")
      (fields
        (field (name "Manufacturer Part") "0603WAF1003T5E")
        (field (name "Manufacturer") "UNI-ROYAL(厚声)")
      )
      (libsource (lib "easyedapro") (part "FRC0603J104 TS"))
    )
    (comp (ref "R68")
      (value "100kΩ")
      (footprint "easyedapro:R0603")
      (fields
        (field (name "Manufacturer Part") "0603WAF1003T5E")
        (field (name "Manufacturer") "UNI-ROYAL(厚声)")
      )
      (libsource (lib "easyedapro") (part "FRC0603J104 TS"))
    )
    (comp (ref "R69")
      (value "100kΩ")
      (footprint "easyedapro:R0603")
      (fields
        (field (name "Manufacturer Part") "0603WAF1003T5E")
        (field (name "Manufacturer") "UNI-ROYAL(厚声)")
      )
      (libsource (lib "easyedapro") (part "FRC0603J104 TS"))
    )
    (comp (ref "R70")
      (value "100kΩ")
      (footprint "easyedapro:R0603")
      (fields
        (field (name "Manufacturer Part") "0603WAF1003T5E")
        (field (name "Manufacturer") "UNI-ROYAL(厚声)")
      )
      (libsource (lib "easyedapro") (part "FRC0603J104 TS"))
    )
    (comp (ref "R71")
      (value "10kΩ")
      (footprint "easyedapro:R0603")
      (fields
        (field (name "Manufacturer Part") "0603WAF1002T5E")
        (field (name "Manufacturer") "UNI-ROYAL(厚声)")
      )
      (libsource (lib "easyedapro") (part "FRC0603J103TS"))
    )
    (comp (ref "R72")
      (value "100kΩ")
      (footprint "easyedapro:R0603")
      (fields
        (field (name "Manufacturer Part") "0603WAF1003T5E")
        (field (name "Manufacturer") "UNI-ROYAL(厚声)")
      )
      (libsource (lib "easyedapro") (part "FRC0603J104 TS"))
    )
    (comp (ref "R73")
      (value "100kΩ")
      (footprint "easyedapro:R0603")
      (fields
        (field (name "Manufacturer Part") "0603WAF1003T5E")
        (field (name "Manufacturer") "UNI-ROYAL(厚声)")
      )
      (libsource (lib "easyedapro") (part "FRC0603J104 TS"))
    )
    (comp (ref "R74")
      (value "100kΩ")
      (footprint "easyedapro:R0603")
      (fields
        (field (name "Manufacturer Part") "0603WAF1003T5E")
        (field (name "Manufacturer") "UNI-ROYAL(厚声)")
      )
      (libsource (lib "easyedapro") (part "FRC0603J104 TS"))
    )
    (comp (ref "R75")
      (value "100kΩ")
      (footprint "easyedapro:R0603")
      (fields
        (field (name "Manufacturer Part") "0603WAF1003T5E")
        (field (name "Manufacturer") "UNI-ROYAL(厚声)")
      )
      (libsource (lib "easyedapro") (part "FRC0603J104 TS"))
    )
    (comp (ref "R76")
      (value "100kΩ")
      (footprint "easyedapro:R0603")
      (fields
        (field (name "Manufacturer Part") "0603WAF1003T5E")
        (field (name "Manufacturer") "UNI-ROYAL(厚声)")
      )
      (libsource (lib "easyedapro") (part "FRC0603J104 TS"))
    )
    (comp (ref "R77")
      (value "100kΩ")
      (footprint "easyedapro:R0603")
      (fields
        (field (name "Manufacturer Part") "0603WAF1003T5E")
        (field (name "Manufacturer") "UNI-ROYAL(厚声)")
      )
      (libsource (lib "easyedapro") (part "FRC0603J104 TS"))
    )
    (comp (ref "R78")
      (value "10kΩ")
      (footprint "easyedapro:R0603")
      (fields
        (field (name "Manufacturer Part") "0603WAF1002T5E")
        (field (name "Manufacturer") "UNI-ROYAL(厚声)")
      )
      (libsource (lib "easyedapro") (part "FRC0603J103TS"))
    )
    (comp (ref "R79")
      (value "100kΩ")
      (footprint "easyedapro:R0603")
      (fields
        (field (name "Manufacturer Part") "0603WAF1003T5E")
        (field (name "Manufacturer") "UNI-ROYAL(厚声)")
      )
      (libsource (lib "easyedapro") (part "FRC0603J104 TS"))
    )
    (comp (ref "R80")
      (value "100kΩ")
      (footprint "easyedapro:R0603")
      (fields
        (field (name "Manufacturer Part") "0603WAF1003T5E")
        (field (name "Manufacturer") "UNI-ROYAL(厚声)")
      )
      (libsource (lib "easyedapro") (part "FRC0603J104 TS"))
    )
    (comp (ref "R81")
      (value "100kΩ")
      (footprint "easyedapro:R0603")
      (fields
        (field (name "Manufacturer Part") "0603WAF1003T5E")
        (field (name "Manufacturer") "UNI-ROYAL(厚声)")
      )
      (libsource (lib "easyedapro") (part "FRC0603J104 TS"))
    )
    (comp (ref "R82")
      (value "100kΩ")
      (footprint "easyedapro:R0603")
      (fields
        (field (name "Manufacturer Part") "0603WAF1003T5E")
        (field (name "Manufacturer") "UNI-ROYAL(厚声)")
      )
      (libsource (lib "easyedapro") (part "FRC0603J104 TS"))
    )
    (comp (ref "R83")
      (value "100kΩ")
      (footprint "easyedapro:R0603")
      (fields
        (field (name "Manufacturer Part") "0603WAF1003T5E")
        (field (name "Manufacturer") "UNI-ROYAL(厚声)")
      )
      (libsource (lib "easyedapro") (part "FRC0603J104 TS"))
    )
    (comp (ref "R84")
      (value "100kΩ")
      (footprint "easyedapro:R0603")
      (fields
        (field (name "Manufacturer Part") "0603WAF1003T5E")
        (field (name "Manufacturer") "UNI-ROYAL(厚声)")
      )
      (libsource (lib "easyedapro") (part "FRC0603J104 TS"))
    )
    (comp (ref "R85")
      (value "10kΩ")
      (footprint "easyedapro:R0603")
      (fields
        (field (name "Manufacturer Part") "0603WAF1002T5E")
        (field (name "Manufacturer") "UNI-ROYAL(厚声)")
      )
      (libsource (lib "easyedapro") (part "FRC0603J103TS"))
    )
    (comp (ref "R86")
      (value "100kΩ")
      (footprint "easyedapro:R0603")
      (fields
        (field (name "Manufacturer Part") "0603WAF1003T5E")
        (field (name "Manufacturer") "UNI-ROYAL(厚声)")
      )
      (libsource (lib "easyedapro") (part "FRC0603J104 TS"))
    )
    (comp (ref "R87")
      (value "100kΩ")
      (footprint "easyedapro:R0603")
      (fields
        (field (name "Manufacturer Part") "0603WAF1003T5E")
        (field (name "Manufacturer") "UNI-ROYAL(厚声)")
      )
      (libsource (lib "easyedapro") (part "FRC0603J104 TS"))
    )
    (comp (ref "R88")
      (value "100kΩ")
      (footprint "easyedapro:R0603")
      (fields
        (field (name "Manufacturer Part") "0603WAF1003T5E")
        (field (name "Manufacturer") "UNI-ROYAL(厚声)")
      )
      (libsource (lib "easyedapro") (part "FRC0603J104 TS"))
    )
    (comp (ref "R89")
      (value "100kΩ")
      (footprint "easyedapro:R0603")
      (fields
        (field (name "Manufacturer Part") "0603WAF1003T5E")
        (field (name "Manufacturer") "UNI-ROYAL(厚声)")
      )
      (libsource (lib "easyedapro") (part "FRC0603J104 TS"))
    )
    (comp (ref "R90")
      (value "100kΩ")
      (footprint "easyedapro:R0603")
      (fields
        (field (name "Manufacturer Part") "0603WAF1003T5E")
        (field (name "Manufacturer") "UNI-ROYAL(厚声)")
      )
      (libsource (lib "easyedapro") (part "FRC0603J104 TS"))
    )
    (comp (ref "R91")
      (value "100kΩ")
      (footprint "easyedapro:R0603")
      (fields
        (field (name "Manufacturer Part") "0603WAF1003T5E")
        (field (name "Manufacturer") "UNI-ROYAL(厚声)")
      )
      (libsource (lib "easyedapro") (part "FRC0603J104 TS"))
    )
    (comp (ref "R92")
      (value "10kΩ")
      (footprint "easyedapro:R0603")
      (fields
        (field (name "Manufacturer Part") "0603WAF1002T5E")
        (field (name "Manufacturer") "UNI-ROYAL(厚声)")
      )
      (libsource (lib "easyedapro") (part "FRC0603J103TS"))
    )
    (comp (ref "R93")
      (value "100kΩ")
      (footprint "easyedapro:R0603")
      (fields
        (field (name "Manufacturer Part") "0603WAF1003T5E")
        (field (name "Manufacturer") "UNI-ROYAL(厚声)")
      )
      (libsource (lib "easyedapro") (part "FRC0603J104 TS"))
    )
    (comp (ref "R94")
      (value "100kΩ")
      (footprint "easyedapro:R0603")
      (fields
        (field (name "Manufacturer Part") "0603WAF1003T5E")
        (field (name "Manufacturer") "UNI-ROYAL(厚声)")
      )
      (libsource (lib "easyedapro") (part "FRC0603J104 TS"))
    )
    (comp (ref "R95")
      (value "100kΩ")
      (footprint "easyedapro:R0603")
      (fields
        (field (name "Manufacturer Part") "0603WAF1003T5E")
        (field (name "Manufacturer") "UNI-ROYAL(厚声)")
      )
      (libsource (lib "easyedapro") (part "FRC0603J104 TS"))
    )
    (comp (ref "R96")
      (value "100kΩ")
      (footprint "easyedapro:R0603")
      (fields
        (field (name "Manufacturer Part") "0603WAF1003T5E")
        (field (name "Manufacturer") "UNI-ROYAL(厚声)")
      )
      (libsource (lib "easyedapro") (part "FRC0603J104 TS"))
    )
    (comp (ref "R97")
      (value "100kΩ")
      (footprint "easyedapro:R0603")
      (fields
        (field (name "Manufacturer Part") "0603WAF1003T5E")
        (field (name "Manufacturer") "UNI-ROYAL(厚声)")
      )
      (libsource (lib "easyedapro") (part "FRC0603J104 TS"))
    )
    (comp (ref "R98")
      (value "100kΩ")
      (footprint "easyedapro:R0603")
      (fields
        (field (name "Manufacturer Part") "0603WAF1003T5E")
        (field (name "Manufacturer") "UNI-ROYAL(厚声)")
      )
      (libsource (lib "easyedapro") (part "FRC0603J104 TS"))
    )
    (comp (ref "R99")
      (value "10kΩ")
      (footprint "easyedapro:R0603")
      (fields
        (field (name "Manufacturer Part") "0603WAF1002T5E")
        (field (name "Manufacturer") "UNI-ROYAL(厚声)")
      )
      (libsource (lib "easyedapro") (part "FRC0603J103TS"))
    )
    (comp (ref "R100")
      (value "100kΩ")
      (footprint "easyedapro:R0603")
      (fields
        (field (name "Manufacturer Part") "0603WAF1003T5E")
        (field (name "Manufacturer") "UNI-ROYAL(厚声)")
      )
      (libsource (lib "easyedapro") (part "FRC0603J104 TS"))
    )
    (comp (ref "R101")
      (value "100kΩ")
      (footprint "easyedapro:R0603")
      (fields
        (field (name "Manufacturer Part") "0603WAF1003T5E")
        (field (name "Manufacturer") "UNI-ROYAL(厚声)")
      )
      (libsource (lib "easyedapro") (part "FRC0603J104 TS"))
    )
    (comp (ref "R102")
      (value "100kΩ")
      (footprint "easyedapro:R0603")
      (fields
        (field (name "Manufacturer Part") "0603WAF1003T5E")
        (field (name "Manufacturer") "UNI-ROYAL(厚声)")
      )
      (libsource (lib "easyedapro") (part "FRC0603J104 TS"))
    )
    (comp (ref "R103")
      (value "100kΩ")
      (footprint "easyedapro:R0603")
      (fields
        (field (name "Manufacturer Part") "0603WAF1003T5E")
        (field (name "Manufacturer") "UNI-ROYAL(厚声)")
      )
      (libsource (lib "easyedapro") (part "FRC0603J104 TS"))
    )
    (comp (ref "R104")
      (value "100kΩ")
      (footprint "easyedapro:R0603")
      (fields
        (field (name "Manufacturer Part") "0603WAF1003T5E")
        (field (name "Manufacturer") "UNI-ROYAL(厚声)")
      )
      (libsource (lib "easyedapro") (part "FRC0603J104 TS"))
    )
    (comp (ref "R105")
      (value "100kΩ")
      (footprint "easyedapro:R0603")
      (fields
        (field (name "Manufacturer Part") "0603WAF1003T5E")
        (field (name "Manufacturer") "UNI-ROYAL(厚声)")
      )
      (libsource (lib "easyedapro") (part "FRC0603J104 TS"))
    )
    (comp (ref "R107")
      (value "10kΩ")
      (footprint "easyedapro:R0603")
      (fields
        (field (name "Manufacturer Part") "0603WAF1002T5E")
        (field (name "Manufacturer") "UNI-ROYAL(厚声)")
      )
      (libsource (lib "easyedapro") (part "FRC0603J103TS"))
    )
    (comp (ref "R108")
      (value "10kΩ")
      (footprint "easyedapro:R0603")
      (fields
        (field (name "Manufacturer Part") "0603WAF1002T5E")
        (field (name "Manufacturer") "UNI-ROYAL(厚声)")
      )
      (libsource (lib "easyedapro") (part "FRC0603J103TS"))
    )
    (comp (ref "R109")
      (value "10kΩ")
      (footprint "easyedapro:R0603")
      (fields
        (field (name "Manufacturer Part") "0603WAF1002T5E")
        (field (name "Manufacturer") "UNI-ROYAL(厚声)")
      )
      (libsource (lib "easyedapro") (part "FRC0603J103TS"))
    )
    (comp (ref "R110")
      (value "10kΩ")
      (footprint "easyedapro:R0603")
      (fields
        (field (name "Manufacturer Part") "0603WAF1002T5E")
        (field (name "Manufacturer") "UNI-ROYAL(厚声)")
      )
      (libsource (lib "easyedapro") (part "FRC0603J103TS"))
    )
    (comp (ref "R111")
      (value "10kΩ")
      (footprint "easyedapro:R0603")
      (fields
        (field (name "Manufacturer Part") "0603WAF1002T5E")
        (field (name "Manufacturer") "UNI-ROYAL(厚声)")
      )
      (libsource (lib "easyedapro") (part "FRC0603J103TS"))
    )
    (comp (ref "R112")
      (value "10kΩ")
      (footprint "easyedapro:R0603")
      (fields
        (field (name "Manufacturer Part") "0603WAF1002T5E")
        (field (name "Manufacturer") "UNI-ROYAL(厚声)")
      )
      (libsource (lib "easyedapro") (part "FRC0603J103TS"))
    )
    (comp (ref "R113")
      (value "10kΩ")
      (footprint "easyedapro:R0603")
      (fields
        (field (name "Manufacturer Part") "0603WAF1002T5E")
        (field (name "Manufacturer") "UNI-ROYAL(厚声)")
      )
      (libsource (lib "easyedapro") (part "FRC0603J103TS"))
    )
    (comp (ref "SW1")
      (value "DSHP01TSGER")
      (footprint "easyedapro:SW-SMD_DSHP01TSGER")
      (fields (field (name "Manufacturer") "康深"))
      (libsource (lib "easyedapro") (part "DSHP01TSGER"))
    )
    (comp (ref "SW2")
      (value "DSHP01TSGER")
      (footprint "easyedapro:SW-SMD_DSHP01TSGER")
      (fields (field (name "Manufacturer") "康深"))
      (libsource (lib "easyedapro") (part "DSHP01TSGER"))
    )
    (comp (ref "SW3")
      (value "DSHP01TSGER")
      (footprint "easyedapro:SW-SMD_DSHP01TSGER")
      (fields (field (name "Manufacturer") "康深"))
      (libsource (lib "easyedapro") (part "DSHP01TSGER"))
    )
    (comp (ref "SW4")
      (value "DSHP01TSGER")
      (footprint "easyedapro:SW-SMD_DSHP01TSGER")
      (fields (field (name "Manufacturer") "康深"))
      (libsource (lib "easyedapro") (part "DSHP01TSGER"))
    )
    (comp (ref "SW5")
      (value "DSHP01TSGER")
      (footprint "easyedapro:SW-SMD_DSHP01TSGER")
      (fields (field (name "Manufacturer") "康深"))
      (libsource (lib "easyedapro") (part "DSHP01TSGER"))
    )
    (comp (ref "SW6")
      (value "DSHP01TSGER")
      (footprint "easyedapro:SW-SMD_DSHP01TSGER")
      (fields (field (name "Manufacturer") "康深"))
      (libsource (lib "easyedapro") (part "DSHP01TSGER"))
    )
    (comp (ref "SW7")
      (value "DSHP01TSGER")
      (footprint "easyedapro:SW-SMD_DSHP01TSGER")
      (fields (field (name "Manufacturer") "康深"))
      (libsource (lib "easyedapro") (part "DSHP01TSGER"))
    )
    (comp (ref "SW8")
      (value "DSHP01TSGER")
      (footprint "easyedapro:SW-SMD_DSHP01TSGER")
      (fields (field (name "Manufacturer") "康深"))
      (libsource (lib "easyedapro") (part "DSHP01TSGER"))
    )
    (comp (ref "SW9")
      (value "DSHP01TSGER")
      (footprint "easyedapro:SW-SMD_DSHP01TSGER")
      (fields (field (name "Manufacturer") "康深"))
      (libsource (lib "easyedapro") (part "DSHP01TSGER"))
    )
    (comp (ref "SW10")
      (value "DSHP01TSGER")
      (footprint "easyedapro:SW-SMD_DSHP01TSGER")
      (fields (field (name "Manufacturer") "康深"))
      (libsource (lib "easyedapro") (part "DSHP01TSGER"))
    )
    (comp (ref "SW11")
      (value "DSHP01TSGER")
      (footprint "easyedapro:SW-SMD_DSHP01TSGER")
      (fields (field (name "Manufacturer") "康深"))
      (libsource (lib "easyedapro") (part "DSHP01TSGER"))
    )
    (comp (ref "SW12")
      (value "DSHP01TSGER")
      (footprint "easyedapro:SW-SMD_DSHP01TSGER")
      (fields (field (name "Manufacturer") "康深"))
      (libsource (lib "easyedapro") (part "DSHP01TSGER"))
    )
    (comp (ref "SW13")
      (value "DSHP01TSGER")
      (footprint "easyedapro:SW-SMD_DSHP01TSGER")
      (fields (field (name "Manufacturer") "康深"))
      (libsource (lib "easyedapro") (part "DSHP01TSGER"))
    )
    (comp (ref "SW14")
      (value "DSHP01TSGER")
      (footprint "easyedapro:SW-SMD_DSHP01TSGER")
      (fields (field (name "Manufacturer") "康深"))
      (libsource (lib "easyedapro") (part "DSHP01TSGER"))
    )
  )
  (nets
    (net (code "1") (name "3V3") (class "Default")
      (node (ref "C11") (pin "2") (pinfunction "2_2") (pintype "unspecified"))
      (node (ref "C12") (pin "2") (pinfunction "2_2") (pintype "input"))
      (node (ref "C13") (pin "2") (pinfunction "2_2") (pintype "input"))
      (node (ref "C14") (pin "2") (pinfunction "2_2") (pintype "unspecified"))
      (node (ref "C3") (pin "2") (pinfunction "2_2") (pintype "input"))
      (node (ref "C4") (pin "2") (pinfunction "2_2") (pintype "input"))
      (node (ref "C5") (pin "2") (pinfunction "2_2") (pintype "input"))
      (node (ref "C6") (pin "2") (pinfunction "2_2") (pintype "input"))
      (node (ref "C8") (pin "2") (pinfunction "2_2") (pintype "unspecified"))
      (node (ref "CN8") (pin "1") (pinfunction "1_1") (pintype "unspecified"))
      (node (ref "H5") (pin "1") (pinfunction "1_1") (pintype "unspecified"))
      (node (ref "H5") (pin "11") (pinfunction "11_11") (pintype "unspecified"))
      (node (ref "H5") (pin "13") (pinfunction "13_13") (pintype "unspecified"))
      (node (ref "H5") (pin "15") (pinfunction "15_15") (pintype "unspecified"))
      (node (ref "H5") (pin "17") (pinfunction "17_17") (pintype "unspecified"))
      (node (ref "H5") (pin "19") (pinfunction "19_19") (pintype "unspecified"))
      (node (ref "H5") (pin "21") (pinfunction "21_21") (pintype "unspecified"))
      (node (ref "H5") (pin "23") (pinfunction "23_23") (pintype "unspecified"))
      (node (ref "H5") (pin "25") (pinfunction "25_25") (pintype "unspecified"))
      (node (ref "H5") (pin "27") (pinfunction "27_27") (pintype "unspecified"))
      (node (ref "H5") (pin "29") (pinfunction "29_29") (pintype "unspecified"))
      (node (ref "H5") (pin "3") (pinfunction "3_3") (pintype "unspecified"))
      (node (ref "H5") (pin "31") (pinfunction "31_31") (pintype "unspecified"))
      (node (ref "H5") (pin "5") (pinfunction "5_5") (pintype "unspecified"))
      (node (ref "H5") (pin "7") (pinfunction "7_7") (pintype "unspecified"))
      (node (ref "H5") (pin "9") (pinfunction "9_9") (pintype "unspecified"))
      (node (ref "R106") (pin "2") (pinfunction "2_2") (pintype "unspecified"))
      (node (ref "R114") (pin "2") (pinfunction "2_2") (pintype "unspecified"))
      (node (ref "R148") (pin "2") (pinfunction "2_2") (pintype "unspecified"))
      (node (ref "R151") (pin "2") (pinfunction "2_2") (pintype "unspecified"))
      (node (ref "R161") (pin "2") (pinfunction "2_2") (pintype "unspecified"))
      (node (ref "R168") (pin "1") (pinfunction "1_1") (pintype "unspecified"))
      (node (ref "R17") (pin "2") (pinfunction "2_2") (pintype "unspecified"))
      (node (ref "R171") (pin "2") (pinfunction "2_2") (pintype "unspecified"))
      (node (ref "R174") (pin "1") (pinfunction "1_1") (pintype "input"))
      (node (ref "R175") (pin "1") (pinfunction "1_1") (pintype "input"))
      (node (ref "R176") (pin "2") (pinfunction "2_2") (pintype "unspecified"))
      (node (ref "R177") (pin "2") (pinfunction "2_2") (pintype "unspecified"))
      (node (ref "R178") (pin "2") (pinfunction "2_2") (pintype "unspecified"))
      (node (ref "R18") (pin "2") (pinfunction "2_2") (pintype "unspecified"))
      (node (ref "R180") (pin "1") (pinfunction "1_1") (pintype "unspecified"))
      (node (ref "R181") (pin "1") (pinfunction "1_1") (pintype "unspecified"))
      (node (ref "R185") (pin "1") (pinfunction "1_1") (pintype "unspecified"))
      (node (ref "R19") (pin "2") (pinfunction "2_2") (pintype "unspecified"))
      (node (ref "R2") (pin "2") (pinfunction "2_2") (pintype "unspecified"))
      (node (ref "R25") (pin "2") (pinfunction "2_2") (pintype "unspecified"))
      (node (ref "R26") (pin "2") (pinfunction "2_2") (pintype "unspecified"))
      (node (ref "R27") (pin "2") (pinfunction "2_2") (pintype "unspecified"))
      (node (ref "R3") (pin "2") (pinfunction "2_2") (pintype "unspecified"))
      (node (ref "R33") (pin "2") (pinfunction "2_2") (pintype "unspecified"))
      (node (ref "R34") (pin "2") (pinfunction "2_2") (pintype "unspecified"))
      (node (ref "R35") (pin "2") (pinfunction "2_2") (pintype "unspecified"))
      (node (ref "R4") (pin "2") (pinfunction "2_2") (pintype "unspecified"))
      (node (ref "R41") (pin "2") (pinfunction "2_2") (pintype "unspecified"))
      (node (ref "R42") (pin "2") (pinfunction "2_2") (pintype "unspecified"))
      (node (ref "R43") (pin "2") (pinfunction "2_2") (pintype "unspecified"))
      (node (ref "R49") (pin "2") (pinfunction "2_2") (pintype "unspecified"))
      (node (ref "R50") (pin "2") (pinfunction "2_2") (pintype "unspecified"))
      (node (ref "R51") (pin "2") (pinfunction "2_2") (pintype "unspecified"))
      (node (ref "R57") (pin "2") (pinfunction "2_2") (pintype "unspecified"))
      (node (ref "R58") (pin "2") (pinfunction "2_2") (pintype "unspecified"))
      (node (ref "R59") (pin "2") (pinfunction "2_2") (pintype "unspecified"))
      (node (ref "U1") (pin "13") (pinfunction "VDDA/VREF+_13") (pintype "unspecified"))
      (node (ref "U1") (pin "19") (pinfunction "VDD_19") (pintype "unspecified"))
      (node (ref "U1") (pin "32") (pinfunction "VDD_32") (pintype "unspecified"))
      (node (ref "U1") (pin "48") (pinfunction "VDD_48") (pintype "unspecified"))
      (node (ref "U1") (pin "64") (pinfunction "VDD_64") (pintype "unspecified"))
      (node (ref "U10") (pin "9") (pinfunction "VDD_9") (pintype "unspecified"))
      (node (ref "U11") (pin "9") (pinfunction "VDD_9") (pintype "unspecified"))
      (node (ref "U12") (pin "9") (pinfunction "VDD_9") (pintype "unspecified"))
      (node (ref "U13") (pin "6") (pinfunction "VDD_6") (pintype "unspecified"))
      (node (ref "U13") (pin "7") (pinfunction "VREGIN_7") (pintype "unspecified"))
      (node (ref "U20") (pin "24") (pinfunction "VCC_24") (pintype "unspecified"))
      (node (ref "U20") (pin "3") (pinfunction "RESET#_3") (pintype "unspecified"))
      (node (ref "U21") (pin "1") (pinfunction "A0_1") (pintype "unspecified"))
      (node (ref "U21") (pin "24") (pinfunction "VCC_24") (pintype "unspecified"))
      (node (ref "U21") (pin "3") (pinfunction "RESET#_3") (pintype "unspecified"))
      (node (ref "U23") (pin "2") (pinfunction "VOUT_2") (pintype "unspecified"))
      (node (ref "U23") (pin "7") (pinfunction "VOUT_7") (pintype "unspecified"))
      (node (ref "U24") (pin "5") (pinfunction "V+_5") (pintype "unspecified"))
      (node (ref "U25") (pin "4") (pinfunction "ADD0_4") (pintype "unspecified"))
      (node (ref "U25") (pin "5") (pinfunction "V+_5") (pintype "unspecified"))
      (node (ref "U9") (pin "2") (pinfunction "3V3_2") (pintype "unspecified"))
    )
    (net (code "2") (name "3V3_EN") (class "Default")
      (node (ref "R133") (pin "2") (pinfunction "2_2") (pintype "unspecified"))
      (node (ref "SW16") (pin "1") (pinfunction "1_1") (pintype "unspecified"))
      (node (ref "U16") (pin "2") (pinfunction "EN_2") (pintype "unspecified"))
    )
    (net (code "3") (name "5V") (class "Default")
      (node (ref "C43") (pin "2") (pinfunction "2_2") (pintype "input"))
      (node (ref "C44") (pin "2") (pinfunction "2_2") (pintype "unspecified"))
      (node (ref "C45") (pin "2") (pinfunction "2_2") (pintype "unspecified"))
      (node (ref "R154") (pin "1") (pinfunction "1_1") (pintype "unspecified"))
      (node (ref "R167") (pin "2") (pinfunction "2_2") (pintype "unspecified"))
      (node (ref "U22") (pin "1") (pinfunction "VIN_1") (pintype "unspecified"))
      (node (ref "U26") (pin "2") (pinfunction "VOUT_2") (pintype "unspecified"))
      (node (ref "U26") (pin "7") (pinfunction "VOUT_7") (pintype "unspecified"))
      (node (ref "U31") (pin "6") (pinfunction "VIN2_6") (pintype "unspecified"))
    )
    (net (code "4") (name "5VTO3V3") (class "Default")
      (node (ref "C46") (pin "1") (pinfunction "1_1") (pintype "unspecified"))
      (node (ref "C47") (pin "2") (pinfunction "2_2") (pintype "input"))
      (node (ref "L3") (pin "1") (pinfunction "1_1") (pintype "unspecified"))
      (node (ref "R156") (pin "2") (pinfunction "2_2") (pintype "unspecified"))
      (node (ref "R158") (pin "1") (pinfunction "1_1") (pintype "input"))
      (node (ref "U23") (pin "6") (pinfunction "VIN2_6") (pintype "unspecified"))
    )
    (net (code "5") (name "5V_DAC") (class "Default")
      (node (ref "R184") (pin "2") (pinfunction "2_2") (pintype "unspecified"))
      (node (ref "U29") (pin "13") (pinfunction "VDD_13") (pintype "input"))
      (node (ref "U29") (pin "15") (pinfunction "VREFIN_15") (pintype "input"))
      (node (ref "U29") (pin "16") (pinfunction "CLR#_16") (pintype "input"))
      (node (ref "U31") (pin "2") (pinfunction "VOUT_2") (pintype "unspecified"))
      (node (ref "U31") (pin "5") (pinfunction "MODE_5") (pintype "unspecified"))
      (node (ref "U31") (pin "7") (pinfunction "VOUT_7") (pintype "unspecified"))
    )
    (net (code "6") (name "5V_LDO") (class "Default")
      (node (ref "C50") (pin "2") (pinfunction "2_2") (pintype "unspecified"))
      (node (ref "R182") (pin "1") (pinfunction "1_1") (pintype "unspecified"))
      (node (ref "U30") (pin "3") (pinfunction "VOUT_3") (pintype "input"))
      (node (ref "U31") (pin "3") (pinfunction "VIN1_3") (pintype "unspecified"))
    )
    (net (code "7") (name "12V") (class "Default")
      (node (ref "C36") (pin "2") (pinfunction "2_2") (pintype "unspecified"))
      (node (ref "C40") (pin "2") (pinfunction "2_2") (pintype "unspecified"))
      (node (ref "C49") (pin "1") (pinfunction "1_1") (pintype "unspecified"))
      (node (ref "L2") (pin "2") (pinfunction "2_2") (pintype "unspecified"))
      (node (ref "R134") (pin "1") (pinfunction "1_1") (pintype "input"))
      (node (ref "U18") (pin "2") (pinfunction "2_2") (pintype "unspecified"))
      (node (ref "U19") (pin "2") (pinfunction "2_2") (pintype "unspecified"))
      (node (ref "U30") (pin "1") (pinfunction "VIN_1") (pintype "input"))
    )
    (net (code "8") (name "12V_EN") (class "Default")
      (node (ref "R132") (pin "2") (pinfunction "2_2") (pintype "unspecified"))
      (node (ref "SW15") (pin "1") (pinfunction "1_1") (pintype "unspecified"))
      (node (ref "U15") (pin "2") (pinfunction "EN_2") (pintype "unspecified"))
    )
    (net (code "9") (name "BOOT0") (class "Default")
      (node (ref "R139") (pin "2") (pinfunction "2_2") (pintype "unspecified"))
      (node (ref "U1") (pin "60") (pinfunction "BOOT0_60") (pintype "unspecified"))
      (node (ref "U9") (pin "28") (pinfunction "IO35_28") (pintype "unspecified"))
    )
    (net (code "10") (name "BOOT1") (class "Default")
      (node (ref "R138") (pin "1") (pinfunction "1_1") (pintype "unspecified"))
      (node (ref "U1") (pin "28") (pinfunction "PB2_28") (pintype "unspecified"))
    )
    (net (code "11") (name "C0_ANGLE") (class "Default")
      (node (ref "U1") (pin "26") (pinfunction "PB0_26") (pintype "unspecified"))
    )
    (net (code "12") (name "C1_AGC") (class "Default")
      (node (ref "R107") (pin "2") (pinfunction "2_2") (pintype "unspecified"))
      (node (ref "SW8") (pin "2") (pinfunction "2_2") (pintype "unspecified"))
      (node (ref "U2") (pin "1") (pinfunction "AGC0_1") (pintype "unspecified"))
      (node (ref "U2") (pin "2") (pinfunction "AGC1_2") (pintype "unspecified"))
    )
    (net (code "13") (name "C1_ANGLE") (class "Default")
      (node (ref "U1") (pin "27") (pinfunction "PB1_27") (pintype "unspecified"))
    )
    (net (code "14") (name "C1_BOOST") (class "Default")
      (node (ref "DP2") (pin "5") (pinfunction "5_5") (pintype "unspecified"))
      (node (ref "DP2") (pin "6") (pinfunction "6_6") (pintype "unspecified"))
      (node (ref "DP2") (pin "7") (pinfunction "7_7") (pintype "unspecified"))
      (node (ref "DP2") (pin "8") (pinfunction "8_8") (pintype "unspecified"))
      (node (ref "U2") (pin "6") (pinfunction "BOOST_6") (pintype "unspecified"))
    )
    (net (code "15") (name "C1_CLIM0") (class "Default")
      (node (ref "R9") (pin "2") (pinfunction "2_2") (pintype "unspecified"))
      (node (ref "SW1") (pin "2") (pinfunction "2_2") (pintype "unspecified"))
      (node (ref "U2") (pin "3") (pinfunction "CLIM0_3") (pintype "unspecified"))
    )
    (net (code "16") (name "C1_CLIM1") (class "Default")
      (node (ref "DP1") (pin "5") (pinfunction "5_5") (pintype "unspecified"))
      (node (ref "DP1") (pin "6") (pinfunction "6_6") (pintype "unspecified"))
      (node (ref "DP1") (pin "7") (pinfunction "7_7") (pintype "unspecified"))
      (node (ref "DP1") (pin "8") (pinfunction "8_8") (pintype "unspecified"))
      (node (ref "U2") (pin "4") (pinfunction "CLIM1_4") (pintype "unspecified"))
    )
    (net (code "17") (name "C1_CLK") (class "Default")
      (node (ref "U1") (pin "58") (pinfunction "PB6_58") (pintype "unspecified"))
      (node (ref "U2") (pin "43") (pinfunction "CLK_43") (pintype "unspecified"))
    )
    (net (code "18") (name "C1_DIR") (class "Default")
      (node (ref "U1") (pin "56") (pinfunction "PB4_56") (pintype "unspecified"))
      (node (ref "U2") (pin "42") (pinfunction "CW/CCW_42") (pintype "unspecified"))
    )
    (net (code "19") (name "C1_DMODE0") (class "Default")
      (node (ref "U10") (pin "23") (pinfunction "GPA2_23") (pintype "unspecified"))
      (node (ref "U2") (pin "39") (pinfunction "DMODE0_39") (pintype "unspecified"))
    )
    (net (code "20") (name "C1_DMODE1") (class "Default")
      (node (ref "U10") (pin "22") (pinfunction "GPA1_22") (pintype "unspecified"))
      (node (ref "U2") (pin "40") (pinfunction "DMODE1_40") (pintype "unspecified"))
    )
    (net (code "21") (name "C1_DMODE2") (class "Default")
      (node (ref "U10") (pin "21") (pinfunction "GPA0_21") (pintype "unspecified"))
      (node (ref "U2") (pin "41") (pinfunction "DMODE2_41") (pintype "unspecified"))
    )
    (net (code "22") (name "C1_EN") (class "Default")
      (node (ref "U1") (pin "57") (pinfunction "PB5_57") (pintype "unspecified"))
      (node (ref "U2") (pin "44") (pinfunction "ENABLE_44") (pintype "unspecified"))
    )
    (net (code "23") (name "C1_FLIM") (class "Default")
      (node (ref "DP3") (pin "5") (pinfunction "5_5") (pintype "unspecified"))
      (node (ref "DP3") (pin "6") (pinfunction "6_6") (pintype "unspecified"))
      (node (ref "DP3") (pin "7") (pinfunction "7_7") (pintype "unspecified"))
      (node (ref "DP3") (pin "8") (pinfunction "8_8") (pintype "unspecified"))
      (node (ref "U2") (pin "5") (pinfunction "FLIM_5") (pintype "unspecified"))
    )
    (net (code "24") (name "C1_LO1") (class "Default")
      (node (ref "R3") (pin "1") (pinfunction "1_1") (pintype "unspecified"))
      (node (ref "TP2") (pin "1") (pinfunction "1_1") (pintype "unspecified"))
      (node (ref "U10") (pin "24") (pinfunction "GPA3_24") (pintype "unspecified"))
      (node (ref "U2") (pin "47") (pinfunction "LO1_47") (pintype "unspecified"))
    )
    (net (code "25") (name "C1_LO2") (class "Default")
      (node (ref "R4") (pin "1") (pinfunction "1_1") (pintype "unspecified"))
      (node (ref "TP3") (pin "1") (pinfunction "1_1") (pintype "unspecified"))
      (node (ref "U10") (pin "25") (pinfunction "GPA4_25") (pintype "unspecified"))
      (node (ref "U2") (pin "48") (pinfunction "LO2_48") (pintype "unspecified"))
    )
    (net (code "26") (name "C1_MO") (class "Default")
      (node (ref "R2") (pin "1") (pinfunction "1_1") (pintype "unspecified"))
      (node (ref "TP1") (pin "1") (pinfunction "1_1") (pintype "unspecified"))
      (node (ref "U2") (pin "46") (pinfunction "MO_46") (pintype "unspecified"))
    )
    (net (code "27") (name "C1_OUT_A+") (class "Default")
      (node (ref "CN1") (pin "1") (pinfunction "1_1") (pintype "unspecified"))
      (node (ref "U2") (pin "13") (pinfunction "OUTA+_13") (pintype "unspecified"))
      (node (ref "U2") (pin "14") (pinfunction "OUTA+_14") (pintype "unspecified"))
    )
    (net (code "28") (name "C1_OUT_A-") (class "Default")
      (node (ref "CN1") (pin "2") (pinfunction "2_2") (pintype "unspecified"))
      (node (ref "U2") (pin "17") (pinfunction "OUTA-_17") (pintype "unspecified"))
      (node (ref "U2") (pin "18") (pinfunction "OUTA-_18") (pintype "unspecified"))
    )
    (net (code "29") (name "C1_OUT_B+") (class "Default")
      (node (ref "CN1") (pin "4") (pinfunction "4_4") (pintype "unspecified"))
      (node (ref "U2") (pin "23") (pinfunction "OUTB+_23") (pintype "unspecified"))
      (node (ref "U2") (pin "24") (pinfunction "OUTB+_24") (pintype "unspecified"))
    )
    (net (code "30") (name "C1_OUT_B-") (class "Default")
      (node (ref "CN1") (pin "3") (pinfunction "3_3") (pintype "unspecified"))
      (node (ref "U2") (pin "19") (pinfunction "OUTB-_19") (pintype "unspecified"))
      (node (ref "U2") (pin "20") (pinfunction "OUTB-_20") (pintype "unspecified"))
    )
    (net (code "31") (name "C1_VCC") (class "Default")
      (node (ref "C51") (pin "2") (pinfunction "2_2") (pintype "input"))
      (node (ref "DP1") (pin "1") (pinfunction "1_1") (pintype "unspecified"))
      (node (ref "DP2") (pin "1") (pinfunction "1_1") (pintype "unspecified"))
      (node (ref "DP3") (pin "1") (pinfunction "1_1") (pintype "unspecified"))
      (node (ref "R10") (pin "1") (pinfunction "1_1") (pintype "unspecified"))
      (node (ref "R107") (pin "1") (pinfunction "1_1") (pintype "unspecified"))
      (node (ref "R12") (pin "1") (pinfunction "1_1") (pintype "unspecified"))
      (node (ref "R14") (pin "1") (pinfunction "1_1") (pintype "unspecified"))
      (node (ref "R6") (pin "2") (pinfunction "2_2") (pintype "unspecified"))
      (node (ref "R9") (pin "1") (pinfunction "1_1") (pintype "unspecified"))
      (node (ref "TP4") (pin "1") (pinfunction "1_1") (pintype "unspecified"))
      (node (ref "U2") (pin "33") (pinfunction "VCC_33") (pintype "unspecified"))
      (node (ref "U2") (pin "34") (pinfunction "VCC_34") (pintype "unspecified"))
    )
    (net (code "32") (name "C1_VREF") (class "Default")
      (node (ref "U2") (pin "31") (pinfunction "VREFB_31") (pintype "unspecified"))
      (node (ref "U2") (pin "32") (pinfunction "VREFA_32") (pintype "unspecified"))
      (node (ref "U29") (pin "1") (pinfunction "VOUTA_1") (pintype "input"))
    )
    (net (code "33") (name "C2_AGC") (class "Default")
      (node (ref "R108") (pin "2") (pinfunction "2_2") (pintype "unspecified"))
      (node (ref "SW9") (pin "2") (pinfunction "2_2") (pintype "unspecified"))
      (node (ref "U3") (pin "1") (pinfunction "AGC0_1") (pintype "unspecified"))
      (node (ref "U3") (pin "2") (pinfunction "AGC1_2") (pintype "unspecified"))
    )
    (net (code "34") (name "C2_ANGLE") (class "Default")
      (node (ref "U1") (pin "8") (pinfunction "PC0_8") (pintype "unspecified"))
    )
    (net (code "35") (name "C2_BOOST") (class "Default")
      (node (ref "DP5") (pin "5") (pinfunction "5_5") (pintype "unspecified"))
      (node (ref "DP5") (pin "6") (pinfunction "6_6") (pintype "unspecified"))
      (node (ref "DP5") (pin "7") (pinfunction "7_7") (pintype "unspecified"))
      (node (ref "DP5") (pin "8") (pinfunction "8_8") (pintype "unspecified"))
      (node (ref "U3") (pin "6") (pinfunction "BOOST_6") (pintype "unspecified"))
    )
    (net (code "36") (name "C2_CLIM0") (class "Default")
      (node (ref "R64") (pin "2") (pinfunction "2_2") (pintype "unspecified"))
      (node (ref "SW2") (pin "2") (pinfunction "2_2") (pintype "unspecified"))
      (node (ref "U3") (pin "3") (pinfunction "CLIM0_3") (pintype "unspecified"))
    )
    (net (code "37") (name "C2_CLIM1") (class "Default")
      (node (ref "DP4") (pin "5") (pinfunction "5_5") (pintype "unspecified"))
      (node (ref "DP4") (pin "6") (pinfunction "6_6") (pintype "unspecified"))
      (node (ref "DP4") (pin "7") (pinfunction "7_7") (pintype "unspecified"))
      (node (ref "DP4") (pin "8") (pinfunction "8_8") (pintype "unspecified"))
      (node (ref "U3") (pin "4") (pinfunction "CLIM1_4") (pintype "unspecified"))
    )
    (net (code "38") (name "C2_CLK") (class "Default")
      (node (ref "U1") (pin "61") (pinfunction "PB8_61") (pintype "unspecified"))
      (node (ref "U3") (pin "43") (pinfunction "CLK_43") (pintype "unspecified"))
    )
    (net (code "39") (name "C2_DIR") (class "Default")
      (node (ref "U1") (pin "54") (pinfunction "PD2_54") (pintype "unspecified"))
      (node (ref "U3") (pin "42") (pinfunction "CW/CCW_42") (pintype "unspecified"))
    )
    (net (code "40") (name "C2_DMODE0") (class "Default")
      (node (ref "U10") (pin "26") (pinfunction "GPA5_26") (pintype "unspecified"))
      (node (ref "U3") (pin "39") (pinfunction "DMODE0_39") (pintype "unspecified"))
    )
    (net (code "41") (name "C2_DMODE1") (class "Default")
      (node (ref "U10") (pin "27") (pinfunction "GPA6_27") (pintype "unspecified"))
      (node (ref "U3") (pin "40") (pinfunction "DMODE1_40") (pintype "unspecified"))
    )
    (net (code "42") (name "C2_DMODE2") (class "Default")
      (node (ref "U10") (pin "28") (pinfunction "GPA7_28") (pintype "unspecified"))
      (node (ref "U3") (pin "41") (pinfunction "DMODE2_41") (pintype "unspecified"))
    )
    (net (code "43") (name "C2_EN") (class "Default")
      (node (ref "U1") (pin "55") (pinfunction "PB3_55") (pintype "unspecified"))
      (node (ref "U3") (pin "44") (pinfunction "ENABLE_44") (pintype "unspecified"))
    )
    (net (code "44") (name "C2_FLIM") (class "Default")
      (node (ref "DP6") (pin "5") (pinfunction "5_5") (pintype "unspecified"))
      (node (ref "DP6") (pin "6") (pinfunction "6_6") (pintype "unspecified"))
      (node (ref "DP6") (pin "7") (pinfunction "7_7") (pintype "unspecified"))
      (node (ref "DP6") (pin "8") (pinfunction "8_8") (pintype "unspecified"))
      (node (ref "U3") (pin "5") (pinfunction "FLIM_5") (pintype "unspecified"))
    )
    (net (code "45") (name "C2_LO1") (class "Default")
      (node (ref "R18") (pin "1") (pinfunction "1_1") (pintype "unspecified"))
      (node (ref "TP6") (pin "1") (pinfunction "1_1") (pintype "unspecified"))
      (node (ref "U10") (pin "1") (pinfunction "GPB0_1") (pintype "unspecified"))
      (node (ref "U3") (pin "47") (pinfunction "LO1_47") (pintype "unspecified"))
    )
    (net (code "46") (name "C2_LO2") (class "Default")
      (node (ref "R19") (pin "1") (pinfunction "1_1") (pintype "unspecified"))
      (node (ref "TP7") (pin "1") (pinfunction "1_1") (pintype "unspecified"))
      (node (ref "U10") (pin "2") (pinfunction "GPB1_2") (pintype "unspecified"))
      (node (ref "U3") (pin "48") (pinfunction "LO2_48") (pintype "unspecified"))
    )
    (net (code "47") (name "C2_MO") (class "Default")
      (node (ref "R17") (pin "1") (pinfunction "1_1") (pintype "unspecified"))
      (node (ref "TP5") (pin "1") (pinfunction "1_1") (pintype "unspecified"))
      (node (ref "U3") (pin "46") (pinfunction "MO_46") (pintype "unspecified"))
    )
    (net (code "48") (name "C2_OUT_A+") (class "Default")
      (node (ref "CN2") (pin "1") (pinfunction "1_1") (pintype "unspecified"))
      (node (ref "U3") (pin "13") (pinfunction "OUTA+_13") (pintype "unspecified"))
      (node (ref "U3") (pin "14") (pinfunction "OUTA+_14") (pintype "unspecified"))
    )
    (net (code "49") (name "C2_OUT_A-") (class "Default")
      (node (ref "CN2") (pin "2") (pinfunction "2_2") (pintype "unspecified"))
      (node (ref "U3") (pin "17") (pinfunction "OUTA-_17") (pintype "unspecified"))
      (node (ref "U3") (pin "18") (pinfunction "OUTA-_18") (pintype "unspecified"))
    )
    (net (code "50") (name "C2_OUT_B+") (class "Default")
      (node (ref "CN2") (pin "4") (pinfunction "4_4") (pintype "unspecified"))
      (node (ref "U3") (pin "23") (pinfunction "OUTB+_23") (pintype "unspecified"))
      (node (ref "U3") (pin "24") (pinfunction "OUTB+_24") (pintype "unspecified"))
    )
    (net (code "51") (name "C2_OUT_B-") (class "Default")
      (node (ref "CN2") (pin "3") (pinfunction "3_3") (pintype "unspecified"))
      (node (ref "U3") (pin "19") (pinfunction "OUTB-_19") (pintype "unspecified"))
      (node (ref "U3") (pin "20") (pinfunction "OUTB-_20") (pintype "unspecified"))
    )
    (net (code "52") (name "C2_VCC") (class "Default")
      (node (ref "C54") (pin "2") (pinfunction "2_2") (pintype "input"))
      (node (ref "DP4") (pin "1") (pinfunction "1_1") (pintype "unspecified"))
      (node (ref "DP5") (pin "1") (pinfunction "1_1") (pintype "unspecified"))
      (node (ref "DP6") (pin "1") (pinfunction "1_1") (pintype "unspecified"))
      (node (ref "R108") (pin "1") (pinfunction "1_1") (pintype "unspecified"))
      (node (ref "R21") (pin "2") (pinfunction "2_2") (pintype "unspecified"))
      (node (ref "R64") (pin "1") (pinfunction "1_1") (pintype "unspecified"))
      (node (ref "R65") (pin "1") (pinfunction "1_1") (pintype "unspecified"))
      (node (ref "R67") (pin "1") (pinfunction "1_1") (pintype "unspecified"))
      (node (ref "R69") (pin "1") (pinfunction "1_1") (pintype "unspecified"))
      (node (ref "TP8") (pin "1") (pinfunction "1_1") (pintype "unspecified"))
      (node (ref "U3") (pin "33") (pinfunction "VCC_33") (pintype "unspecified"))
      (node (ref "U3") (pin "34") (pinfunction "VCC_34") (pintype "unspecified"))
    )
    (net (code "53") (name "C2_VREF") (class "Default")
      (node (ref "U29") (pin "2") (pinfunction "VOUTB_2") (pintype "input"))
      (node (ref "U3") (pin "31") (pinfunction "VREFB_31") (pintype "unspecified"))
      (node (ref "U3") (pin "32") (pinfunction "VREFA_32") (pintype "unspecified"))
    )
    (net (code "54") (name "C3_AGC") (class "Default")
      (node (ref "R109") (pin "2") (pinfunction "2_2") (pintype "unspecified"))
      (node (ref "SW10") (pin "2") (pinfunction "2_2") (pintype "unspecified"))
      (node (ref "U4") (pin "1") (pinfunction "AGC0_1") (pintype "unspecified"))
      (node (ref "U4") (pin "2") (pinfunction "AGC1_2") (pintype "unspecified"))
    )
    (net (code "55") (name "C3_ANGLE") (class "Default")
      (node (ref "U1") (pin "9") (pinfunction "PC1_9") (pintype "unspecified"))
    )
    (net (code "56") (name "C3_BOOST") (class "Default")
      (node (ref "DP8") (pin "5") (pinfunction "5_5") (pintype "unspecified"))
      (node (ref "DP8") (pin "6") (pinfunction "6_6") (pintype "unspecified"))
      (node (ref "DP8") (pin "7") (pinfunction "7_7") (pintype "unspecified"))
      (node (ref "DP8") (pin "8") (pinfunction "8_8") (pintype "unspecified"))
      (node (ref "U4") (pin "6") (pinfunction "BOOST_6") (pintype "unspecified"))
    )
    (net (code "57") (name "C3_CLIM0") (class "Default")
      (node (ref "R71") (pin "2") (pinfunction "2_2") (pintype "unspecified"))
      (node (ref "SW3") (pin "2") (pinfunction "2_2") (pintype "unspecified"))
      (node (ref "U4") (pin "3") (pinfunction "CLIM0_3") (pintype "unspecified"))
    )
    (net (code "58") (name "C3_CLIM1") (class "Default")
      (node (ref "DP7") (pin "5") (pinfunction "5_5") (pintype "unspecified"))
      (node (ref "DP7") (pin "6") (pinfunction "6_6") (pintype "unspecified"))
      (node (ref "DP7") (pin "7") (pinfunction "7_7") (pintype "unspecified"))
      (node (ref "DP7") (pin "8") (pinfunction "8_8") (pintype "unspecified"))
      (node (ref "U4") (pin "4") (pinfunction "CLIM1_4") (pintype "unspecified"))
    )
    (net (code "59") (name "C3_CLK") (class "Default")
      (node (ref "U1") (pin "62") (pinfunction "PB9_62") (pintype "unspecified"))
      (node (ref "U4") (pin "43") (pinfunction "CLK_43") (pintype "unspecified"))
    )
    (net (code "60") (name "C3_DIR") (class "Default")
      (node (ref "U1") (pin "52") (pinfunction "PC11_52") (pintype "unspecified"))
      (node (ref "U4") (pin "42") (pinfunction "CW/CCW_42") (pintype "unspecified"))
    )
    (net (code "61") (name "C3_DMODE0") (class "Default")
      (node (ref "U10") (pin "5") (pinfunction "GPB4_5") (pintype "unspecified"))
      (node (ref "U4") (pin "39") (pinfunction "DMODE0_39") (pintype "unspecified"))
    )
    (net (code "62") (name "C3_DMODE1") (class "Default")
      (node (ref "U10") (pin "4") (pinfunction "GPB3_4") (pintype "unspecified"))
      (node (ref "U4") (pin "40") (pinfunction "DMODE1_40") (pintype "unspecified"))
    )
    (net (code "63") (name "C3_DMODE2") (class "Default")
      (node (ref "U10") (pin "3") (pinfunction "GPB2_3") (pintype "unspecified"))
      (node (ref "U4") (pin "41") (pinfunction "DMODE2_41") (pintype "unspecified"))
    )
    (net (code "64") (name "C3_EN") (class "Default")
      (node (ref "U1") (pin "53") (pinfunction "PC12_53") (pintype "unspecified"))
      (node (ref "U4") (pin "44") (pinfunction "ENABLE_44") (pintype "unspecified"))
    )
    (net (code "65") (name "C3_FLIM") (class "Default")
      (node (ref "DP9") (pin "5") (pinfunction "5_5") (pintype "unspecified"))
      (node (ref "DP9") (pin "6") (pinfunction "6_6") (pintype "unspecified"))
      (node (ref "DP9") (pin "7") (pinfunction "7_7") (pintype "unspecified"))
      (node (ref "DP9") (pin "8") (pinfunction "8_8") (pintype "unspecified"))
      (node (ref "U4") (pin "5") (pinfunction "FLIM_5") (pintype "unspecified"))
    )
    (net (code "66") (name "C3_LO1") (class "Default")
      (node (ref "R26") (pin "1") (pinfunction "1_1") (pintype "unspecified"))
      (node (ref "TP10") (pin "1") (pinfunction "1_1") (pintype "unspecified"))
      (node (ref "U10") (pin "7") (pinfunction "GPB6_7") (pintype "unspecified"))
      (node (ref "U4") (pin "47") (pinfunction "LO1_47") (pintype "unspecified"))
    )
    (net (code "67") (name "C3_LO2") (class "Default")
      (node (ref "R27") (pin "1") (pinfunction "1_1") (pintype "unspecified"))
      (node (ref "TP11") (pin "1") (pinfunction "1_1") (pintype "unspecified"))
      (node (ref "U10") (pin "6") (pinfunction "GPB5_6") (pintype "unspecified"))
      (node (ref "U4") (pin "48") (pinfunction "LO2_48") (pintype "unspecified"))
    )
    (net (code "68") (name "C3_MO") (class "Default")
      (node (ref "R25") (pin "1") (pinfunction "1_1") (pintype "unspecified"))
      (node (ref "TP9") (pin "1") (pinfunction "1_1") (pintype "unspecified"))
      (node (ref "U4") (pin "46") (pinfunction "MO_46") (pintype "unspecified"))
    )
    (net (code "69") (name "C3_OUT_A+") (class "Default")
      (node (ref "CN3") (pin "1") (pinfunction "1_1") (pintype "unspecified"))
      (node (ref "U4") (pin "13") (pinfunction "OUTA+_13") (pintype "unspecified"))
      (node (ref "U4") (pin "14") (pinfunction "OUTA+_14") (pintype "unspecified"))
    )
    (net (code "70") (name "C3_OUT_A-") (class "Default")
      (node (ref "CN3") (pin "2") (pinfunction "2_2") (pintype "unspecified"))
      (node (ref "U4") (pin "17") (pinfunction "OUTA-_17") (pintype "unspecified"))
      (node (ref "U4") (pin "18") (pinfunction "OUTA-_18") (pintype "unspecified"))
    )
    (net (code "71") (name "C3_OUT_B+") (class "Default")
      (node (ref "CN3") (pin "4") (pinfunction "4_4") (pintype "unspecified"))
      (node (ref "U4") (pin "23") (pinfunction "OUTB+_23") (pintype "unspecified"))
      (node (ref "U4") (pin "24") (pinfunction "OUTB+_24") (pintype "unspecified"))
    )
    (net (code "72") (name "C3_OUT_B-") (class "Default")
      (node (ref "CN3") (pin "3") (pinfunction "3_3") (pintype "unspecified"))
      (node (ref "U4") (pin "19") (pinfunction "OUTB-_19") (pintype "unspecified"))
      (node (ref "U4") (pin "20") (pinfunction "OUTB-_20") (pintype "unspecified"))
    )
    (net (code "73") (name "C3_VCC") (class "Default")
      (node (ref "C53") (pin "2") (pinfunction "2_2") (pintype "input"))
      (node (ref "DP7") (pin "1") (pinfunction "1_1") (pintype "unspecified"))
      (node (ref "DP8") (pin "1") (pinfunction "1_1") (pintype "unspecified"))
      (node (ref "DP9") (pin "1") (pinfunction "1_1") (pintype "unspecified"))
      (node (ref "R109") (pin "1") (pinfunction "1_1") (pintype "unspecified"))
      (node (ref "R29") (pin "2") (pinfunction "2_2") (pintype "unspecified"))
      (node (ref "R71") (pin "1") (pinfunction "1_1") (pintype "unspecified"))
      (node (ref "R72") (pin "1") (pinfunction "1_1") (pintype "unspecified"))
      (node (ref "R74") (pin "1") (pinfunction "1_1") (pintype "unspecified"))
      (node (ref "R76") (pin "1") (pinfunction "1_1") (pintype "unspecified"))
      (node (ref "TP12") (pin "1") (pinfunction "1_1") (pintype "unspecified"))
      (node (ref "U4") (pin "33") (pinfunction "VCC_33") (pintype "unspecified"))
      (node (ref "U4") (pin "34") (pinfunction "VCC_34") (pintype "unspecified"))
    )
    (net (code "74") (name "C3_VREF") (class "Default")
      (node (ref "U29") (pin "3") (pinfunction "VOUTC_3") (pintype "input"))
      (node (ref "U4") (pin "31") (pinfunction "VREFB_31") (pintype "unspecified"))
      (node (ref "U4") (pin "32") (pinfunction "VREFA_32") (pintype "unspecified"))
    )
    (net (code "75") (name "C4_AGC") (class "Default")
      (node (ref "R110") (pin "2") (pinfunction "2_2") (pintype "unspecified"))
      (node (ref "SW11") (pin "2") (pinfunction "2_2") (pintype "unspecified"))
      (node (ref "U5") (pin "1") (pinfunction "AGC0_1") (pintype "unspecified"))
      (node (ref "U5") (pin "2") (pinfunction "AGC1_2") (pintype "unspecified"))
    )
    (net (code "76") (name "C4_ANGLE") (class "Default")
      (node (ref "U1") (pin "11") (pinfunction "PC3_11") (pintype "unspecified"))
    )
    (net (code "77") (name "C4_BOOST") (class "Default")
      (node (ref "DP11") (pin "5") (pinfunction "5_5") (pintype "unspecified"))
      (node (ref "DP11") (pin "6") (pinfunction "6_6") (pintype "unspecified"))
      (node (ref "DP11") (pin "7") (pinfunction "7_7") (pintype "unspecified"))
      (node (ref "DP11") (pin "8") (pinfunction "8_8") (pintype "unspecified"))
      (node (ref "U5") (pin "6") (pinfunction "BOOST_6") (pintype "unspecified"))
    )
    (net (code "78") (name "C4_CLIM0") (class "Default")
      (node (ref "R78") (pin "2") (pinfunction "2_2") (pintype "unspecified"))
      (node (ref "SW4") (pin "2") (pinfunction "2_2") (pintype "unspecified"))
      (node (ref "U5") (pin "3") (pinfunction "CLIM0_3") (pintype "unspecified"))
    )
    (net (code "79") (name "C4_CLIM1") (class "Default")
      (node (ref "DP10") (pin "5") (pinfunction "5_5") (pintype "unspecified"))
      (node (ref "DP10") (pin "6") (pinfunction "6_6") (pintype "unspecified"))
      (node (ref "DP10") (pin "7") (pinfunction "7_7") (pintype "unspecified"))
      (node (ref "DP10") (pin "8") (pinfunction "8_8") (pintype "unspecified"))
      (node (ref "U5") (pin "4") (pinfunction "CLIM1_4") (pintype "unspecified"))
    )
    (net (code "80") (name "C4_CLK") (class "Default")
      (node (ref "U1") (pin "14") (pinfunction "PA0_14") (pintype "unspecified"))
      (node (ref "U5") (pin "43") (pinfunction "CLK_43") (pintype "unspecified"))
    )
    (net (code "81") (name "C4_DIR") (class "Default")
      (node (ref "U1") (pin "50") (pinfunction "PA15_50") (pintype "unspecified"))
      (node (ref "U5") (pin "42") (pinfunction "CW/CCW_42") (pintype "unspecified"))
    )
    (net (code "82") (name "C4_DMODE0") (class "Default")
      (node (ref "U10") (pin "8") (pinfunction "GPB7_8") (pintype "unspecified"))
      (node (ref "U5") (pin "39") (pinfunction "DMODE0_39") (pintype "unspecified"))
    )
    (net (code "83") (name "C4_DMODE1") (class "Default")
      (node (ref "U11") (pin "22") (pinfunction "GPA1_22") (pintype "unspecified"))
      (node (ref "U5") (pin "40") (pinfunction "DMODE1_40") (pintype "unspecified"))
    )
    (net (code "84") (name "C4_DMODE2") (class "Default")
      (node (ref "U11") (pin "21") (pinfunction "GPA0_21") (pintype "unspecified"))
      (node (ref "U5") (pin "41") (pinfunction "DMODE2_41") (pintype "unspecified"))
    )
    (net (code "85") (name "C4_EN") (class "Default")
      (node (ref "U1") (pin "51") (pinfunction "PC10_51") (pintype "unspecified"))
      (node (ref "U5") (pin "44") (pinfunction "ENABLE_44") (pintype "unspecified"))
    )
    (net (code "86") (name "C4_FLIM") (class "Default")
      (node (ref "DP12") (pin "5") (pinfunction "5_5") (pintype "unspecified"))
      (node (ref "DP12") (pin "6") (pinfunction "6_6") (pintype "unspecified"))
      (node (ref "DP12") (pin "7") (pinfunction "7_7") (pintype "unspecified"))
      (node (ref "DP12") (pin "8") (pinfunction "8_8") (pintype "unspecified"))
      (node (ref "U5") (pin "5") (pinfunction "FLIM_5") (pintype "unspecified"))
    )
    (net (code "87") (name "C4_LO1") (class "Default")
      (node (ref "R34") (pin "1") (pinfunction "1_1") (pintype "unspecified"))
      (node (ref "TP14") (pin "1") (pinfunction "1_1") (pintype "unspecified"))
      (node (ref "U11") (pin "24") (pinfunction "GPA3_24") (pintype "unspecified"))
      (node (ref "U5") (pin "47") (pinfunction "LO1_47") (pintype "unspecified"))
    )
    (net (code "88") (name "C4_LO2") (class "Default")
      (node (ref "R35") (pin "1") (pinfunction "1_1") (pintype "unspecified"))
      (node (ref "TP15") (pin "1") (pinfunction "1_1") (pintype "unspecified"))
      (node (ref "U11") (pin "23") (pinfunction "GPA2_23") (pintype "unspecified"))
      (node (ref "U5") (pin "48") (pinfunction "LO2_48") (pintype "unspecified"))
    )
    (net (code "89") (name "C4_MO") (class "Default")
      (node (ref "R33") (pin "1") (pinfunction "1_1") (pintype "unspecified"))
      (node (ref "TP13") (pin "1") (pinfunction "1_1") (pintype "unspecified"))
      (node (ref "U5") (pin "46") (pinfunction "MO_46") (pintype "unspecified"))
    )
    (net (code "90") (name "C4_OUT_A+") (class "Default")
      (node (ref "CN4") (pin "1") (pinfunction "1_1") (pintype "unspecified"))
      (node (ref "U5") (pin "13") (pinfunction "OUTA+_13") (pintype "unspecified"))
      (node (ref "U5") (pin "14") (pinfunction "OUTA+_14") (pintype "unspecified"))
    )
    (net (code "91") (name "C4_OUT_A-") (class "Default")
      (node (ref "CN4") (pin "2") (pinfunction "2_2") (pintype "unspecified"))
      (node (ref "U5") (pin "17") (pinfunction "OUTA-_17") (pintype "unspecified"))
      (node (ref "U5") (pin "18") (pinfunction "OUTA-_18") (pintype "unspecified"))
    )
    (net (code "92") (name "C4_OUT_B+") (class "Default")
      (node (ref "CN4") (pin "4") (pinfunction "4_4") (pintype "unspecified"))
      (node (ref "U5") (pin "23") (pinfunction "OUTB+_23") (pintype "unspecified"))
      (node (ref "U5") (pin "24") (pinfunction "OUTB+_24") (pintype "unspecified"))
    )
    (net (code "93") (name "C4_OUT_B-") (class "Default")
      (node (ref "CN4") (pin "3") (pinfunction "3_3") (pintype "unspecified"))
      (node (ref "U5") (pin "19") (pinfunction "OUTB-_19") (pintype "unspecified"))
      (node (ref "U5") (pin "20") (pinfunction "OUTB-_20") (pintype "unspecified"))
    )
    (net (code "94") (name "C4_VCC") (class "Default")
      (node (ref "C62") (pin "2") (pinfunction "2_2") (pintype "input"))
      (node (ref "DP10") (pin "1") (pinfunction "1_1") (pintype "unspecified"))
      (node (ref "DP11") (pin "1") (pinfunction "1_1") (pintype "unspecified"))
      (node (ref "DP12") (pin "1") (pinfunction "1_1") (pintype "unspecified"))
      (node (ref "R110") (pin "1") (pinfunction "1_1") (pintype "unspecified"))
      (node (ref "R37") (pin "2") (pinfunction "2_2") (pintype "unspecified"))
      (node (ref "R78") (pin "1") (pinfunction "1_1") (pintype "unspecified"))
      (node (ref "R79") (pin "1") (pinfunction "1_1") (pintype "unspecified"))
      (node (ref "R81") (pin "1") (pinfunction "1_1") (pintype "unspecified"))
      (node (ref "R83") (pin "1") (pinfunction "1_1") (pintype "unspecified"))
      (node (ref "TP16") (pin "1") (pinfunction "1_1") (pintype "unspecified"))
      (node (ref "U5") (pin "33") (pinfunction "VCC_33") (pintype "unspecified"))
      (node (ref "U5") (pin "34") (pinfunction "VCC_34") (pintype "unspecified"))
    )
    (net (code "95") (name "C4_VREF") (class "Default")
      (node (ref "U29") (pin "4") (pinfunction "VOUTD_4") (pintype "input"))
      (node (ref "U5") (pin "31") (pinfunction "VREFB_31") (pintype "unspecified"))
      (node (ref "U5") (pin "32") (pinfunction "VREFA_32") (pintype "unspecified"))
    )
    (net (code "96") (name "C5_AGC") (class "Default")
      (node (ref "R111") (pin "2") (pinfunction "2_2") (pintype "unspecified"))
      (node (ref "SW12") (pin "2") (pinfunction "2_2") (pintype "unspecified"))
      (node (ref "U6") (pin "1") (pinfunction "AGC0_1") (pintype "unspecified"))
      (node (ref "U6") (pin "2") (pinfunction "AGC1_2") (pintype "unspecified"))
    )
    (net (code "97") (name "C5_ANGLE") (class "Default")
      (node (ref "U1") (pin "24") (pinfunction "PC4_24") (pintype "unspecified"))
    )
    (net (code "98") (name "C5_BOOST") (class "Default")
      (node (ref "DP14") (pin "5") (pinfunction "5_5") (pintype "unspecified"))
      (node (ref "DP14") (pin "6") (pinfunction "6_6") (pintype "unspecified"))
      (node (ref "DP14") (pin "7") (pinfunction "7_7") (pintype "unspecified"))
      (node (ref "DP14") (pin "8") (pinfunction "8_8") (pintype "unspecified"))
      (node (ref "U6") (pin "6") (pinfunction "BOOST_6") (pintype "unspecified"))
    )
    (net (code "99") (name "C5_CLIM0") (class "Default")
      (node (ref "R85") (pin "2") (pinfunction "2_2") (pintype "unspecified"))
      (node (ref "SW5") (pin "2") (pinfunction "2_2") (pintype "unspecified"))
      (node (ref "U6") (pin "3") (pinfunction "CLIM0_3") (pintype "unspecified"))
    )
    (net (code "100") (name "C5_CLIM1") (class "Default")
      (node (ref "DP13") (pin "5") (pinfunction "5_5") (pintype "unspecified"))
      (node (ref "DP13") (pin "6") (pinfunction "6_6") (pintype "unspecified"))
      (node (ref "DP13") (pin "7") (pinfunction "7_7") (pintype "unspecified"))
      (node (ref "DP13") (pin "8") (pinfunction "8_8") (pintype "unspecified"))
      (node (ref "U6") (pin "4") (pinfunction "CLIM1_4") (pintype "unspecified"))
    )
    (net (code "101") (name "C5_CLK") (class "Default")
      (node (ref "U1") (pin "22") (pinfunction "PA6_22") (pintype "unspecified"))
      (node (ref "U6") (pin "43") (pinfunction "CLK_43") (pintype "unspecified"))
    )
    (net (code "102") (name "C5_DIR") (class "Default")
      (node (ref "U1") (pin "39") (pinfunction "PC8_39") (pintype "unspecified"))
      (node (ref "U6") (pin "42") (pinfunction "CW/CCW_42") (pintype "unspecified"))
    )
    (net (code "103") (name "C5_DMODE0") (class "Default")
      (node (ref "U11") (pin "27") (pinfunction "GPA6_27") (pintype "unspecified"))
      (node (ref "U6") (pin "39") (pinfunction "DMODE0_39") (pintype "unspecified"))
    )
    (net (code "104") (name "C5_DMODE1") (class "Default")
      (node (ref "U11") (pin "26") (pinfunction "GPA5_26") (pintype "unspecified"))
      (node (ref "U6") (pin "40") (pinfunction "DMODE1_40") (pintype "unspecified"))
    )
    (net (code "105") (name "C5_DMODE2") (class "Default")
      (node (ref "U11") (pin "25") (pinfunction "GPA4_25") (pintype "unspecified"))
      (node (ref "U6") (pin "41") (pinfunction "DMODE2_41") (pintype "unspecified"))
    )
    (net (code "106") (name "C5_EN") (class "Default")
      (node (ref "U1") (pin "38") (pinfunction "PC7_38") (pintype "unspecified"))
      (node (ref "U6") (pin "44") (pinfunction "ENABLE_44") (pintype "unspecified"))
    )
    (net (code "107") (name "C5_FLIM") (class "Default")
      (node (ref "DP15") (pin "5") (pinfunction "5_5") (pintype "unspecified"))
      (node (ref "DP15") (pin "6") (pinfunction "6_6") (pintype "unspecified"))
      (node (ref "DP15") (pin "7") (pinfunction "7_7") (pintype "unspecified"))
      (node (ref "DP15") (pin "8") (pinfunction "8_8") (pintype "unspecified"))
      (node (ref "U6") (pin "5") (pinfunction "FLIM_5") (pintype "unspecified"))
    )
    (net (code "108") (name "C5_LO1") (class "Default")
      (node (ref "R42") (pin "1") (pinfunction "1_1") (pintype "unspecified"))
      (node (ref "TP18") (pin "1") (pinfunction "1_1") (pintype "unspecified"))
      (node (ref "U11") (pin "1") (pinfunction "GPB0_1") (pintype "unspecified"))
      (node (ref "U6") (pin "47") (pinfunction "LO1_47") (pintype "unspecified"))
    )
    (net (code "109") (name "C5_LO2") (class "Default")
      (node (ref "R43") (pin "1") (pinfunction "1_1") (pintype "unspecified"))
      (node (ref "TP19") (pin "1") (pinfunction "1_1") (pintype "unspecified"))
      (node (ref "U11") (pin "2") (pinfunction "GPB1_2") (pintype "unspecified"))
      (node (ref "U6") (pin "48") (pinfunction "LO2_48") (pintype "unspecified"))
    )
    (net (code "110") (name "C5_MO") (class "Default")
      (node (ref "R41") (pin "1") (pinfunction "1_1") (pintype "unspecified"))
      (node (ref "TP17") (pin "1") (pinfunction "1_1") (pintype "unspecified"))
      (node (ref "U6") (pin "46") (pinfunction "MO_46") (pintype "unspecified"))
    )
    (net (code "111") (name "C5_OUT_A+") (class "Default")
      (node (ref "CN5") (pin "1") (pinfunction "1_1") (pintype "unspecified"))
      (node (ref "U6") (pin "13") (pinfunction "OUTA+_13") (pintype "unspecified"))
      (node (ref "U6") (pin "14") (pinfunction "OUTA+_14") (pintype "unspecified"))
    )
    (net (code "112") (name "C5_OUT_A-") (class "Default")
      (node (ref "CN5") (pin "2") (pinfunction "2_2") (pintype "unspecified"))
      (node (ref "U6") (pin "17") (pinfunction "OUTA-_17") (pintype "unspecified"))
      (node (ref "U6") (pin "18") (pinfunction "OUTA-_18") (pintype "unspecified"))
    )
    (net (code "113") (name "C5_OUT_B+") (class "Default")
      (node (ref "CN5") (pin "4") (pinfunction "4_4") (pintype "unspecified"))
      (node (ref "U6") (pin "23") (pinfunction "OUTB+_23") (pintype "unspecified"))
      (node (ref "U6") (pin "24") (pinfunction "OUTB+_24") (pintype "unspecified"))
    )
    (net (code "114") (name "C5_OUT_B-") (class "Default")
      (node (ref "CN5") (pin "3") (pinfunction "3_3") (pintype "unspecified"))
      (node (ref "U6") (pin "19") (pinfunction "OUTB-_19") (pintype "unspecified"))
      (node (ref "U6") (pin "20") (pinfunction "OUTB-_20") (pintype "unspecified"))
    )
    (net (code "115") (name "C5_VCC") (class "Default")
      (node (ref "C61") (pin "2") (pinfunction "2_2") (pintype "input"))
      (node (ref "DP13") (pin "1") (pinfunction "1_1") (pintype "unspecified"))
      (node (ref "DP14") (pin "1") (pinfunction "1_1") (pintype "unspecified"))
      (node (ref "DP15") (pin "1") (pinfunction "1_1") (pintype "unspecified"))
      (node (ref "R111") (pin "1") (pinfunction "1_1") (pintype "unspecified"))
      (node (ref "R45") (pin "2") (pinfunction "2_2") (pintype "unspecified"))
      (node (ref "R85") (pin "1") (pinfunction "1_1") (pintype "unspecified"))
      (node (ref "R86") (pin "1") (pinfunction "1_1") (pintype "unspecified"))
      (node (ref "R88") (pin "1") (pinfunction "1_1") (pintype "unspecified"))
      (node (ref "R90") (pin "1") (pinfunction "1_1") (pintype "unspecified"))
      (node (ref "TP20") (pin "1") (pinfunction "1_1") (pintype "unspecified"))
      (node (ref "U6") (pin "33") (pinfunction "VCC_33") (pintype "unspecified"))
      (node (ref "U6") (pin "34") (pinfunction "VCC_34") (pintype "unspecified"))
    )
    (net (code "116") (name "C5_VREF") (class "Default")
      (node (ref "U29") (pin "9") (pinfunction "VOUTE_9") (pintype "input"))
      (node (ref "U6") (pin "31") (pinfunction "VREFB_31") (pintype "unspecified"))
      (node (ref "U6") (pin "32") (pinfunction "VREFA_32") (pintype "unspecified"))
    )
    (net (code "117") (name "C6_AGC") (class "Default")
      (node (ref "R112") (pin "2") (pinfunction "2_2") (pintype "unspecified"))
      (node (ref "SW13") (pin "2") (pinfunction "2_2") (pintype "unspecified"))
      (node (ref "U7") (pin "1") (pinfunction "AGC0_1") (pintype "unspecified"))
      (node (ref "U7") (pin "2") (pinfunction "AGC1_2") (pintype "unspecified"))
    )
    (net (code "118") (name "C6_ANGLE") (class "Default")
      (node (ref "U1") (pin "25") (pinfunction "PC5_25") (pintype "unspecified"))
    )
    (net (code "119") (name "C6_BOOST") (class "Default")
      (node (ref "DP17") (pin "5") (pinfunction "5_5") (pintype "unspecified"))
      (node (ref "DP17") (pin "6") (pinfunction "6_6") (pintype "unspecified"))
      (node (ref "DP17") (pin "7") (pinfunction "7_7") (pintype "unspecified"))
      (node (ref "DP17") (pin "8") (pinfunction "8_8") (pintype "unspecified"))
      (node (ref "U7") (pin "6") (pinfunction "BOOST_6") (pintype "unspecified"))
    )
    (net (code "120") (name "C6_CLIM0") (class "Default")
      (node (ref "R92") (pin "2") (pinfunction "2_2") (pintype "unspecified"))
      (node (ref "SW6") (pin "2") (pinfunction "2_2") (pintype "unspecified"))
      (node (ref "U7") (pin "3") (pinfunction "CLIM0_3") (pintype "unspecified"))
    )
    (net (code "121") (name "C6_CLIM1") (class "Default")
      (node (ref "DP16") (pin "5") (pinfunction "5_5") (pintype "unspecified"))
      (node (ref "DP16") (pin "6") (pinfunction "6_6") (pintype "unspecified"))
      (node (ref "DP16") (pin "7") (pinfunction "7_7") (pintype "unspecified"))
      (node (ref "DP16") (pin "8") (pinfunction "8_8") (pintype "unspecified"))
      (node (ref "U7") (pin "4") (pinfunction "CLIM1_4") (pintype "unspecified"))
    )
    (net (code "122") (name "C6_CLK") (class "Default")
      (node (ref "U1") (pin "23") (pinfunction "PA7_23") (pintype "unspecified"))
      (node (ref "U7") (pin "43") (pinfunction "CLK_43") (pintype "unspecified"))
    )
    (net (code "123") (name "C6_DIR") (class "Default")
      (node (ref "U1") (pin "45") (pinfunction "PA12_45") (pintype "unspecified"))
      (node (ref "U7") (pin "42") (pinfunction "CW/CCW_42") (pintype "unspecified"))
    )
    (net (code "124") (name "C6_DMODE0") (class "Default")
      (node (ref "U11") (pin "5") (pinfunction "GPB4_5") (pintype "unspecified"))
      (node (ref "U7") (pin "39") (pinfunction "DMODE0_39") (pintype "unspecified"))
    )
    (net (code "125") (name "C6_DMODE1") (class "Default")
      (node (ref "U11") (pin "4") (pinfunction "GPB3_4") (pintype "unspecified"))
      (node (ref "U7") (pin "40") (pinfunction "DMODE1_40") (pintype "unspecified"))
    )
    (net (code "126") (name "C6_DMODE2") (class "Default")
      (node (ref "U11") (pin "3") (pinfunction "GPB2_3") (pintype "unspecified"))
      (node (ref "U7") (pin "41") (pinfunction "DMODE2_41") (pintype "unspecified"))
    )
    (net (code "127") (name "C6_EN") (class "Default")
      (node (ref "U1") (pin "44") (pinfunction "PA11_44") (pintype "unspecified"))
      (node (ref "U7") (pin "44") (pinfunction "ENABLE_44") (pintype "unspecified"))
    )
    (net (code "128") (name "C6_FLIM") (class "Default")
      (node (ref "DP18") (pin "5") (pinfunction "5_5") (pintype "unspecified"))
      (node (ref "DP18") (pin "6") (pinfunction "6_6") (pintype "unspecified"))
      (node (ref "DP18") (pin "7") (pinfunction "7_7") (pintype "unspecified"))
      (node (ref "DP18") (pin "8") (pinfunction "8_8") (pintype "unspecified"))
      (node (ref "U7") (pin "5") (pinfunction "FLIM_5") (pintype "unspecified"))
    )
    (net (code "129") (name "C6_LO1") (class "Default")
      (node (ref "R50") (pin "1") (pinfunction "1_1") (pintype "unspecified"))
      (node (ref "TP22") (pin "1") (pinfunction "1_1") (pintype "unspecified"))
      (node (ref "U11") (pin "7") (pinfunction "GPB6_7") (pintype "unspecified"))
      (node (ref "U7") (pin "47") (pinfunction "LO1_47") (pintype "unspecified"))
    )
    (net (code "130") (name "C6_LO2") (class "Default")
      (node (ref "R51") (pin "1") (pinfunction "1_1") (pintype "unspecified"))
      (node (ref "TP23") (pin "1") (pinfunction "1_1") (pintype "unspecified"))
      (node (ref "U11") (pin "6") (pinfunction "GPB5_6") (pintype "unspecified"))
      (node (ref "U7") (pin "48") (pinfunction "LO2_48") (pintype "unspecified"))
    )
    (net (code "131") (name "C6_MO") (class "Default")
      (node (ref "R49") (pin "1") (pinfunction "1_1") (pintype "unspecified"))
      (node (ref "TP21") (pin "1") (pinfunction "1_1") (pintype "unspecified"))
      (node (ref "U7") (pin "46") (pinfunction "MO_46") (pintype "unspecified"))
    )
    (net (code "132") (name "C6_OUT_A+") (class "Default")
      (node (ref "CN6") (pin "1") (pinfunction "1_1") (pintype "unspecified"))
      (node (ref "U7") (pin "13") (pinfunction "OUTA+_13") (pintype "unspecified"))
      (node (ref "U7") (pin "14") (pinfunction "OUTA+_14") (pintype "unspecified"))
    )
    (net (code "133") (name "C6_OUT_A-") (class "Default")
      (node (ref "CN6") (pin "2") (pinfunction "2_2") (pintype "unspecified"))
      (node (ref "U7") (pin "17") (pinfunction "OUTA-_17") (pintype "unspecified"))
      (node (ref "U7") (pin "18") (pinfunction "OUTA-_18") (pintype "unspecified"))
    )
    (net (code "134") (name "C6_OUT_B+") (class "Default")
      (node (ref "CN6") (pin "4") (pinfunction "4_4") (pintype "unspecified"))
      (node (ref "U7") (pin "23") (pinfunction "OUTB+_23") (pintype "unspecified"))
      (node (ref "U7") (pin "24") (pinfunction "OUTB+_24") (pintype "unspecified"))
    )
    (net (code "135") (name "C6_OUT_B-") (class "Default")
      (node (ref "CN6") (pin "3") (pinfunction "3_3") (pintype "unspecified"))
      (node (ref "U7") (pin "19") (pinfunction "OUTB-_19") (pintype "unspecified"))
      (node (ref "U7") (pin "20") (pinfunction "OUTB-_20") (pintype "unspecified"))
    )
    (net (code "136") (name "C6_VCC") (class "Default")
      (node (ref "C60") (pin "2") (pinfunction "2_2") (pintype "input"))
      (node (ref "DP16") (pin "1") (pinfunction "1_1") (pintype "unspecified"))
      (node (ref "DP17") (pin "1") (pinfunction "1_1") (pintype "unspecified"))
      (node (ref "DP18") (pin "1") (pinfunction "1_1") (pintype "unspecified"))
      (node (ref "R112") (pin "1") (pinfunction "1_1") (pintype "unspecified"))
      (node (ref "R53") (pin "2") (pinfunction "2_2") (pintype "unspecified"))
      (node (ref "R92") (pin "1") (pinfunction "1_1") (pintype "unspecified"))
      (node (ref "R93") (pin "1") (pinfunction "1_1") (pintype "unspecified"))
      (node (ref "R95") (pin "1") (pinfunction "1_1") (pintype "unspecified"))
      (node (ref "R97") (pin "1") (pinfunction "1_1") (pintype "unspecified"))
      (node (ref "TP24") (pin "1") (pinfunction "1_1") (pintype "unspecified"))
      (node (ref "U7") (pin "33") (pinfunction "VCC_33") (pintype "unspecified"))
      (node (ref "U7") (pin "34") (pinfunction "VCC_34") (pintype "unspecified"))
    )
    (net (code "137") (name "C6_VREF") (class "Default")
      (node (ref "U29") (pin "10") (pinfunction "VOUTF_10") (pintype "input"))
      (node (ref "U7") (pin "31") (pinfunction "VREFB_31") (pintype "unspecified"))
      (node (ref "U7") (pin "32") (pinfunction "VREFA_32") (pintype "unspecified"))
    )
    (net (code "138") (name "C7_AGC") (class "Default")
      (node (ref "R113") (pin "2") (pinfunction "2_2") (pintype "unspecified"))
      (node (ref "SW14") (pin "2") (pinfunction "2_2") (pintype "unspecified"))
      (node (ref "U8") (pin "1") (pinfunction "AGC0_1") (pintype "unspecified"))
      (node (ref "U8") (pin "2") (pinfunction "AGC1_2") (pintype "unspecified"))
    )
    (net (code "139") (name "C7_BOOST") (class "Default")
      (node (ref "DP20") (pin "5") (pinfunction "5_5") (pintype "unspecified"))
      (node (ref "DP20") (pin "6") (pinfunction "6_6") (pintype "unspecified"))
      (node (ref "DP20") (pin "7") (pinfunction "7_7") (pintype "unspecified"))
      (node (ref "DP20") (pin "8") (pinfunction "8_8") (pintype "unspecified"))
      (node (ref "U8") (pin "6") (pinfunction "BOOST_6") (pintype "unspecified"))
    )
    (net (code "140") (name "C7_CLIM0") (class "Default")
      (node (ref "R99") (pin "2") (pinfunction "2_2") (pintype "unspecified"))
      (node (ref "SW7") (pin "2") (pinfunction "2_2") (pintype "unspecified"))
      (node (ref "U8") (pin "3") (pinfunction "CLIM0_3") (pintype "unspecified"))
    )
    (net (code "141") (name "C7_CLIM1") (class "Default")
      (node (ref "DP19") (pin "5") (pinfunction "5_5") (pintype "unspecified"))
      (node (ref "DP19") (pin "6") (pinfunction "6_6") (pintype "unspecified"))
      (node (ref "DP19") (pin "7") (pinfunction "7_7") (pintype "unspecified"))
      (node (ref "DP19") (pin "8") (pinfunction "8_8") (pintype "unspecified"))
      (node (ref "U8") (pin "4") (pinfunction "CLIM1_4") (pintype "unspecified"))
    )
    (net (code "142") (name "C7_CLK") (class "Default")
      (node (ref "U1") (pin "35") (pinfunction "PB14_35") (pintype "unspecified"))
      (node (ref "U8") (pin "43") (pinfunction "CLK_43") (pintype "unspecified"))
    )
    (net (code "143") (name "C7_DIR") (class "Default")
      (node (ref "U1") (pin "43") (pinfunction "PA10_43") (pintype "unspecified"))
      (node (ref "U8") (pin "42") (pinfunction "CW/CCW_42") (pintype "unspecified"))
    )
    (net (code "144") (name "C7_DMODE0") (class "Default")
      (node (ref "U12") (pin "25") (pinfunction "GPA4_25") (pintype "unspecified"))
      (node (ref "U8") (pin "39") (pinfunction "DMODE0_39") (pintype "unspecified"))
    )
    (net (code "145") (name "C7_DMODE1") (class "Default")
      (node (ref "U12") (pin "24") (pinfunction "GPA3_24") (pintype "unspecified"))
      (node (ref "U8") (pin "40") (pinfunction "DMODE1_40") (pintype "unspecified"))
    )
    (net (code "146") (name "C7_DMODE2") (class "Default")
      (node (ref "U12") (pin "23") (pinfunction "GPA2_23") (pintype "unspecified"))
      (node (ref "U8") (pin "41") (pinfunction "DMODE2_41") (pintype "unspecified"))
    )
    (net (code "147") (name "C7_EN") (class "Default")
      (node (ref "U1") (pin "42") (pinfunction "PA9_42") (pintype "unspecified"))
      (node (ref "U8") (pin "44") (pinfunction "ENABLE_44") (pintype "unspecified"))
    )
    (net (code "148") (name "C7_FLIM") (class "Default")
      (node (ref "DP21") (pin "5") (pinfunction "5_5") (pintype "unspecified"))
      (node (ref "DP21") (pin "6") (pinfunction "6_6") (pintype "unspecified"))
      (node (ref "DP21") (pin "7") (pinfunction "7_7") (pintype "unspecified"))
      (node (ref "DP21") (pin "8") (pinfunction "8_8") (pintype "unspecified"))
      (node (ref "U8") (pin "5") (pinfunction "FLIM_5") (pintype "unspecified"))
    )
    (net (code "149") (name "C7_LO1") (class "Default")
      (node (ref "R58") (pin "1") (pinfunction "1_1") (pintype "unspecified"))
      (node (ref "TP26") (pin "1") (pinfunction "1_1") (pintype "unspecified"))
      (node (ref "U12") (pin "22") (pinfunction "GPA1_22") (pintype "unspecified"))
      (node (ref "U8") (pin "47") (pinfunction "LO1_47") (pintype "unspecified"))
    )
    (net (code "150") (name "C7_LO2") (class "Default")
      (node (ref "R59") (pin "1") (pinfunction "1_1") (pintype "unspecified"))
      (node (ref "TP27") (pin "1") (pinfunction "1_1") (pintype "unspecified"))
      (node (ref "U12") (pin "21") (pinfunction "GPA0_21") (pintype "unspecified"))
      (node (ref "U8") (pin "48") (pinfunction "LO2_48") (pintype "unspecified"))
    )
    (net (code "151") (name "C7_MO") (class "Default")
      (node (ref "R57") (pin "1") (pinfunction "1_1") (pintype "unspecified"))
      (node (ref "TP25") (pin "1") (pinfunction "1_1") (pintype "unspecified"))
      (node (ref "U8") (pin "46") (pinfunction "MO_46") (pintype "unspecified"))
    )
    (net (code "152") (name "C7_OUT_A+") (class "Default")
      (node (ref "CN7") (pin "1") (pinfunction "1_1") (pintype "unspecified"))
      (node (ref "U8") (pin "13") (pinfunction "OUTA+_13") (pintype "unspecified"))
      (node (ref "U8") (pin "14") (pinfunction "OUTA+_14") (pintype "unspecified"))
    )
    (net (code "153") (name "C7_OUT_A-") (class "Default")
      (node (ref "CN7") (pin "2") (pinfunction "2_2") (pintype "unspecified"))
      (node (ref "U8") (pin "17") (pinfunction "OUTA-_17") (pintype "unspecified"))
      (node (ref "U8") (pin "18") (pinfunction "OUTA-_18") (pintype "unspecified"))
    )
    (net (code "154") (name "C7_OUT_B+") (class "Default")
      (node (ref "CN7") (pin "4") (pinfunction "4_4") (pintype "unspecified"))
      (node (ref "U8") (pin "23") (pinfunction "OUTB+_23") (pintype "unspecified"))
      (node (ref "U8") (pin "24") (pinfunction "OUTB+_24") (pintype "unspecified"))
    )
    (net (code "155") (name "C7_OUT_B-") (class "Default")
      (node (ref "CN7") (pin "3") (pinfunction "3_3") (pintype "unspecified"))
      (node (ref "U8") (pin "19") (pinfunction "OUTB-_19") (pintype "unspecified"))
      (node (ref "U8") (pin "20") (pinfunction "OUTB-_20") (pintype "unspecified"))
    )
    (net (code "156") (name "C7_VCC") (class "Default")
      (node (ref "C59") (pin "2") (pinfunction "2_2") (pintype "input"))
      (node (ref "DP19") (pin "1") (pinfunction "1_1") (pintype "unspecified"))
      (node (ref "DP20") (pin "1") (pinfunction "1_1") (pintype "unspecified"))
      (node (ref "DP21") (pin "1") (pinfunction "1_1") (pintype "unspecified"))
      (node (ref "R100") (pin "1") (pinfunction "1_1") (pintype "unspecified"))
      (node (ref "R102") (pin "1") (pinfunction "1_1") (pintype "unspecified"))
      (node (ref "R104") (pin "1") (pinfunction "1_1") (pintype "unspecified"))
      (node (ref "R113") (pin "1") (pinfunction "1_1") (pintype "unspecified"))
      (node (ref "R61") (pin "2") (pinfunction "2_2") (pintype "unspecified"))
      (node (ref "R99") (pin "1") (pinfunction "1_1") (pintype "unspecified"))
      (node (ref "TP28") (pin "1") (pinfunction "1_1") (pintype "unspecified"))
      (node (ref "U8") (pin "33") (pinfunction "VCC_33") (pintype "unspecified"))
      (node (ref "U8") (pin "34") (pinfunction "VCC_34") (pintype "unspecified"))
    )
    (net (code "157") (name "C7_VREF") (class "Default")
      (node (ref "U29") (pin "11") (pinfunction "VOUTG_11") (pintype "input"))
      (node (ref "U8") (pin "31") (pinfunction "VREFB_31") (pintype "unspecified"))
      (node (ref "U8") (pin "32") (pinfunction "VREFA_32") (pintype "unspecified"))
    )
    (net (code "158") (name "DTR") (class "Default")
      (node (ref "Q2") (pin "2") (pinfunction "E_2") (pintype "unspecified"))
      (node (ref "R131") (pin "2") (pinfunction "2_2") (pintype "unspecified"))
      (node (ref "U13") (pin "28") (pinfunction "DTR_28") (pintype "unspecified"))
    )
    (net (code "159") (name "ESP32_D+") (class "Default")
      (node (ref "R163") (pin "1") (pinfunction "1_1") (pintype "input"))
      (node (ref "U9") (pin "14") (pinfunction "IO20_14") (pintype "unspecified"))
    )
    (net (code "160") (name "ESP32_D-") (class "Default")
      (node (ref "R164") (pin "1") (pinfunction "1_1") (pintype "input"))
      (node (ref "U9") (pin "13") (pinfunction "IO19_13") (pintype "unspecified"))
    )
    (net (code "161") (name "ESP32_EXTR_5V") (class "Default")
      (node (ref "D2") (pin "5") (pinfunction "VBUS_5") (pintype "unspecified"))
      (node (ref "U26") (pin "6") (pinfunction "VIN2_6") (pintype "unspecified"))
      (node (ref "USB2") (pin "A4B9") (pinfunction "VBUS_A4B9") (pintype "unspecified"))
      (node (ref "USB2") (pin "B4A9") (pinfunction "VBUS_B4A9") (pintype "unspecified"))
    )
    (net (code "162") (name "ESP32_EXTR_D+") (class "Default")
      (node (ref "D2") (pin "4") (pinfunction "I/O2_4") (pintype "unspecified"))
      (node (ref "USB2") (pin "A6") (pinfunction "Dp1_A6") (pintype "unspecified"))
      (node (ref "USB2") (pin "B6") (pinfunction "Dp2_B6") (pintype "unspecified"))
    )
    (net (code "163") (name "ESP32_EXTR_D-") (class "Default")
      (node (ref "D2") (pin "6") (pinfunction "I/O1_6") (pintype "unspecified"))
      (node (ref "USB2") (pin "A7") (pinfunction "Dn1_A7") (pintype "unspecified"))
      (node (ref "USB2") (pin "B7") (pinfunction "Dn2_B7") (pintype "unspecified"))
    )
    (net (code "164") (name "ESP_BOOT") (class "Default")
      (node (ref "Q2") (pin "3") (pinfunction "C_3") (pintype "unspecified"))
      (node (ref "R180") (pin "2") (pinfunction "2_2") (pintype "unspecified"))
      (node (ref "SW17") (pin "1") (pinfunction "1_1") (pintype "unspecified"))
      (node (ref "U9") (pin "27") (pinfunction "IO0_27") (pintype "unspecified"))
    )
    (net (code "165") (name "ESP_NRESET") (class "Default")
      (node (ref "Q1") (pin "3") (pinfunction "C_3") (pintype "unspecified"))
      (node (ref "R181") (pin "2") (pinfunction "2_2") (pintype "unspecified"))
      (node (ref "SW18") (pin "1") (pinfunction "1_1") (pintype "unspecified"))
      (node (ref "U9") (pin "3") (pinfunction "EN_3") (pintype "unspecified"))
    )
    (net (code "166") (name "ESP_RX2TX") (class "Default")
      (node (ref "U13") (pin "26") (pinfunction "TXD_26") (pintype "unspecified"))
      (node (ref "U9") (pin "36") (pinfunction "RXD0_36") (pintype "unspecified"))
    )
    (net (code "167") (name "ESP_TX2RX") (class "Default")
      (node (ref "U13") (pin "25") (pinfunction "RXD_25") (pintype "unspecified"))
      (node (ref "U9") (pin "37") (pinfunction "TXD0_37") (pintype "unspecified"))
    )
    (net (code "168") (name "EXT_SCK") (class "Default")
      (node (ref "H1") (pin "2") (pinfunction "2_2") (pintype "unspecified"))
      (node (ref "H2") (pin "2") (pinfunction "2_2") (pintype "unspecified"))
      (node (ref "H3") (pin "2") (pinfunction "2_2") (pintype "unspecified"))
      (node (ref "R175") (pin "2") (pinfunction "2_2") (pintype "input"))
      (node (ref "U1") (pin "41") (pinfunction "PA8_41") (pintype "unspecified"))
      (node (ref "U10") (pin "12") (pinfunction "SCK_12") (pintype "unspecified"))
      (node (ref "U11") (pin "12") (pinfunction "SCK_12") (pintype "unspecified"))
      (node (ref "U12") (pin "12") (pinfunction "SCK_12") (pintype "unspecified"))
      (node (ref "U20") (pin "22") (pinfunction "SCL_22") (pintype "unspecified"))
      (node (ref "U21") (pin "22") (pinfunction "SCL_22") (pintype "unspecified"))
      (node (ref "U24") (pin "1") (pinfunction "SCL_1") (pintype "unspecified"))
      (node (ref "U25") (pin "1") (pinfunction "SCL_1") (pintype "unspecified"))
      (node (ref "U29") (pin "6") (pinfunction "SCL_6") (pintype "input"))
    )
    (net (code "169") (name "EXT_SDA") (class "Default")
      (node (ref "H1") (pin "1") (pinfunction "1_1") (pintype "unspecified"))
      (node (ref "H2") (pin "1") (pinfunction "1_1") (pintype "unspecified"))
      (node (ref "H3") (pin "1") (pinfunction "1_1") (pintype "unspecified"))
      (node (ref "R174") (pin "2") (pinfunction "2_2") (pintype "input"))
      (node (ref "U1") (pin "40") (pinfunction "PC9_40") (pintype "unspecified"))
      (node (ref "U10") (pin "13") (pinfunction "SDA_13") (pintype "unspecified"))
      (node (ref "U11") (pin "13") (pinfunction "SDA_13") (pintype "unspecified"))
      (node (ref "U12") (pin "13") (pinfunction "SDA_13") (pintype "unspecified"))
      (node (ref "U20") (pin "23") (pinfunction "SDA_23") (pintype "unspecified"))
      (node (ref "U21") (pin "23") (pinfunction "SDA_23") (pintype "unspecified"))
      (node (ref "U24") (pin "6") (pinfunction "SDA_6") (pintype "unspecified"))
      (node (ref "U25") (pin "6") (pinfunction "SDA_6") (pintype "unspecified"))
      (node (ref "U29") (pin "5") (pinfunction "SDA_5") (pintype "input"))
      (node (ref "U29") (pin "7") (pinfunction "A0_7") (pintype "input"))
    )
    (net (code "170") (name "FAN_PWM_0") (class "Default")
      (node (ref "R144") (pin "2") (pinfunction "2_2") (pintype "unspecified"))
      (node (ref "R153") (pin "1") (pinfunction "1_1") (pintype "unspecified"))
      (node (ref "U9") (pin "4") (pinfunction "IO4_4") (pintype "unspecified"))
    )
    (net (code "171") (name "FAN_PWM_1") (class "Default")
      (node (ref "R149") (pin "2") (pinfunction "2_2") (pintype "unspecified"))
      (node (ref "R152") (pin "1") (pinfunction "1_1") (pintype "unspecified"))
      (node (ref "U9") (pin "6") (pinfunction "IO6_6") (pintype "unspecified"))
    )
    (net (code "172") (name "FAN_PWM_LINE_0") (class "Default")
      (node (ref "Q4") (pin "3") (pinfunction "C_3") (pintype "unspecified"))
      (node (ref "R148") (pin "1") (pinfunction "1_1") (pintype "unspecified"))
      (node (ref "U18") (pin "4") (pinfunction "4_4") (pintype "unspecified"))
    )
    (net (code "173") (name "FAN_PWM_LINE_1") (class "Default")
      (node (ref "Q5") (pin "3") (pinfunction "C_3") (pintype "unspecified"))
      (node (ref "R151") (pin "1") (pinfunction "1_1") (pintype "unspecified"))
      (node (ref "U19") (pin "4") (pinfunction "4_4") (pintype "unspecified"))
    )
    (net (code "174") (name "FAN_SENSE_0") (class "Default")
      (node (ref "R171") (pin "1") (pinfunction "1_1") (pintype "unspecified"))
      (node (ref "U18") (pin "1") (pinfunction "1_1") (pintype "unspecified"))
      (node (ref "U9") (pin "5") (pinfunction "IO5_5") (pintype "unspecified"))
    )
    (net (code "175") (name "FAN_SENSE_1") (class "Default")
      (node (ref "R185") (pin "2") (pinfunction "2_2") (pintype "unspecified"))
      (node (ref "U19") (pin "1") (pinfunction "1_1") (pintype "unspecified"))
      (node (ref "U9") (pin "7") (pinfunction "IO7_7") (pintype "unspecified"))
    )
    (net (code "176") (name "GND") (class "Default")
      (node (ref "C1") (pin "1") (pinfunction "1_1") (pintype "unspecified"))
      (node (ref "C11") (pin "1") (pinfunction "1_1") (pintype "unspecified"))
      (node (ref "C12") (pin "1") (pinfunction "1_1") (pintype "input"))
      (node (ref "C13") (pin "1") (pinfunction "1_1") (pintype "input"))
      (node (ref "C14") (pin "1") (pinfunction "1_1") (pintype "unspecified"))
      (node (ref "C15") (pin "2") (pinfunction "2_2") (pintype "input"))
      (node (ref "C16") (pin "2") (pinfunction "2_2") (pintype "input"))
      (node (ref "C17") (pin "2") (pinfunction "2_2") (pintype "input"))
      (node (ref "C18") (pin "2") (pinfunction "2_2") (pintype "input"))
      (node (ref "C21") (pin "2") (pinfunction "2_2") (pintype "input"))
      (node (ref "C23") (pin "2") (pinfunction "2_2") (pintype "input"))
      (node (ref "C24") (pin "2") (pinfunction "2_2") (pintype "input"))
      (node (ref "C25") (pin "2") (pinfunction "2_2") (pintype "input"))
      (node (ref "C26") (pin "1") (pinfunction "1_1") (pintype "unspecified"))
      (node (ref "C27") (pin "1") (pinfunction "1_1") (pintype "unspecified"))
      (node (ref "C28") (pin "1") (pinfunction "1_1") (pintype "unspecified"))
      (node (ref "C29") (pin "1") (pinfunction "1_1") (pintype "unspecified"))
      (node (ref "C3") (pin "1") (pinfunction "1_1") (pintype "input"))
      (node (ref "C30") (pin "1") (pinfunction "1_1") (pintype "unspecified"))
      (node (ref "C31") (pin "1") (pinfunction "1_1") (pintype "unspecified"))
      (node (ref "C32") (pin "1") (pinfunction "1_1") (pintype "unspecified"))
      (node (ref "C33") (pin "1") (pinfunction "1_1") (pintype "unspecified"))
      (node (ref "C36") (pin "1") (pinfunction "1_1") (pintype "unspecified"))
      (node (ref "C38") (pin "1") (pinfunction "1_1") (pintype "unspecified"))
      (node (ref "C39") (pin "1") (pinfunction "1_1") (pintype "unspecified"))
      (node (ref "C4") (pin "1") (pinfunction "1_1") (pintype "input"))
      (node (ref "C40") (pin "1") (pinfunction "1_1") (pintype "unspecified"))
      (node (ref "C43") (pin "1") (pinfunction "1_1") (pintype "input"))
      (node (ref "C44") (pin "1") (pinfunction "1_1") (pintype "unspecified"))
      (node (ref "C45") (pin "1") (pinfunction "1_1") (pintype "unspecified"))
      (node (ref "C46") (pin "2") (pinfunction "2_2") (pintype "unspecified"))
      (node (ref "C47") (pin "1") (pinfunction "1_1") (pintype "input"))
      (node (ref "C49") (pin "2") (pinfunction "2_2") (pintype "unspecified"))
      (node (ref "C5") (pin "1") (pinfunction "1_1") (pintype "input"))
      (node (ref "C50") (pin "1") (pinfunction "1_1") (pintype "unspecified"))
      (node (ref "C51") (pin "1") (pinfunction "1_1") (pintype "input"))
      (node (ref "C53") (pin "1") (pinfunction "1_1") (pintype "input"))
      (node (ref "C54") (pin "1") (pinfunction "1_1") (pintype "input"))
      (node (ref "C59") (pin "1") (pinfunction "1_1") (pintype "input"))
      (node (ref "C6") (pin "1") (pinfunction "1_1") (pintype "input"))
      (node (ref "C60") (pin "1") (pinfunction "1_1") (pintype "input"))
      (node (ref "C61") (pin "1") (pinfunction "1_1") (pintype "input"))
      (node (ref "C62") (pin "1") (pinfunction "1_1") (pintype "input"))
      (node (ref "C63") (pin "1") (pinfunction "1_1") (pintype "unspecified"))
      (node (ref "C64") (pin "1") (pinfunction "1_1") (pintype "unspecified"))
      (node (ref "C65") (pin "1") (pinfunction "1_1") (pintype "unspecified"))
      (node (ref "C66") (pin "1") (pinfunction "1_1") (pintype "unspecified"))
      (node (ref "C67") (pin "1") (pinfunction "1_1") (pintype "unspecified"))
      (node (ref "C68") (pin "1") (pinfunction "1_1") (pintype "unspecified"))
      (node (ref "C69") (pin "1") (pinfunction "1_1") (pintype "unspecified"))
      (node (ref "C70") (pin "1") (pinfunction "1_1") (pintype "unspecified"))
      (node (ref "C8") (pin "1") (pinfunction "1_1") (pintype "unspecified"))
      (node (ref "CN8") (pin "3") (pinfunction "3_3") (pintype "unspecified"))
      (node (ref "CN8") (pin "5") (pinfunction "5_5") (pintype "unspecified"))
      (node (ref "D1") (pin "2") (pinfunction "GND_2") (pintype "unspecified"))
      (node (ref "D2") (pin "2") (pinfunction "GND_2") (pintype "unspecified"))
      (node (ref "DP1") (pin "4") (pinfunction "4_4") (pintype "unspecified"))
      (node (ref "DP10") (pin "4") (pinfunction "4_4") (pintype "unspecified"))
      (node (ref "DP11") (pin "4") (pinfunction "4_4") (pintype "unspecified"))
      (node (ref "DP12") (pin "4") (pinfunction "4_4") (pintype "unspecified"))
      (node (ref "DP13") (pin "4") (pinfunction "4_4") (pintype "unspecified"))
      (node (ref "DP14") (pin "4") (pinfunction "4_4") (pintype "unspecified"))
      (node (ref "DP15") (pin "4") (pinfunction "4_4") (pintype "unspecified"))
      (node (ref "DP16") (pin "4") (pinfunction "4_4") (pintype "unspecified"))
      (node (ref "DP17") (pin "4") (pinfunction "4_4") (pintype "unspecified"))
      (node (ref "DP18") (pin "4") (pinfunction "4_4") (pintype "unspecified"))
      (node (ref "DP19") (pin "4") (pinfunction "4_4") (pintype "unspecified"))
      (node (ref "DP2") (pin "4") (pinfunction "4_4") (pintype "unspecified"))
      (node (ref "DP20") (pin "4") (pinfunction "4_4") (pintype "unspecified"))
      (node (ref "DP21") (pin "4") (pinfunction "4_4") (pintype "unspecified"))
      (node (ref "DP3") (pin "4") (pinfunction "4_4") (pintype "unspecified"))
      (node (ref "DP4") (pin "4") (pinfunction "4_4") (pintype "unspecified"))
      (node (ref "DP5") (pin "4") (pinfunction "4_4") (pintype "unspecified"))
      (node (ref "DP6") (pin "4") (pinfunction "4_4") (pintype "unspecified"))
      (node (ref "DP7") (pin "4") (pinfunction "4_4") (pintype "unspecified"))
      (node (ref "DP8") (pin "4") (pinfunction "4_4") (pintype "unspecified"))
      (node (ref "DP9") (pin "4") (pinfunction "4_4") (pintype "unspecified"))
      (node (ref "H5") (pin "10") (pinfunction "10_10") (pintype "unspecified"))
      (node (ref "H5") (pin "12") (pinfunction "12_12") (pintype "unspecified"))
      (node (ref "H5") (pin "14") (pinfunction "14_14") (pintype "unspecified"))
      (node (ref "H5") (pin "16") (pinfunction "16_16") (pintype "unspecified"))
      (node (ref "H5") (pin "18") (pinfunction "18_18") (pintype "unspecified"))
      (node (ref "H5") (pin "2") (pinfunction "2_2") (pintype "unspecified"))
      (node (ref "H5") (pin "20") (pinfunction "20_20") (pintype "unspecified"))
      (node (ref "H5") (pin "22") (pinfunction "22_22") (pintype "unspecified"))
      (node (ref "H5") (pin "24") (pinfunction "24_24") (pintype "unspecified"))
      (node (ref "H5") (pin "26") (pinfunction "26_26") (pintype "unspecified"))
      (node (ref "H5") (pin "28") (pinfunction "28_28") (pintype "unspecified"))
      (node (ref "H5") (pin "30") (pinfunction "30_30") (pintype "unspecified"))
      (node (ref "H5") (pin "32") (pinfunction "32_32") (pintype "unspecified"))
      (node (ref "H5") (pin "4") (pinfunction "4_4") (pintype "unspecified"))
      (node (ref "H5") (pin "6") (pinfunction "6_6") (pintype "unspecified"))
      (node (ref "H5") (pin "8") (pinfunction "8_8") (pintype "unspecified"))
      (node (ref "Q4") (pin "2") (pinfunction "E_2") (pintype "unspecified"))
      (node (ref "Q5") (pin "2") (pinfunction "E_2") (pintype "unspecified"))
      (node (ref "Q6") (pin "2") (pinfunction "E_2") (pintype "unspecified"))
      (node (ref "R1") (pin "1") (pinfunction "1_1") (pintype "unspecified"))
      (node (ref "R101") (pin "1") (pinfunction "1_1") (pintype "unspecified"))
      (node (ref "R103") (pin "1") (pinfunction "1_1") (pintype "unspecified"))
      (node (ref "R105") (pin "1") (pinfunction "1_1") (pintype "unspecified"))
      (node (ref "R11") (pin "1") (pinfunction "1_1") (pintype "unspecified"))
      (node (ref "R115") (pin "1") (pinfunction "1_1") (pintype "input"))
      (node (ref "R116") (pin "1") (pinfunction "1_1") (pintype "input"))
      (node (ref "R118") (pin "2") (pinfunction "2_2") (pintype "input"))
      (node (ref "R13") (pin "1") (pinfunction "1_1") (pintype "unspecified"))
      (node (ref "R132") (pin "1") (pinfunction "1_1") (pintype "unspecified"))
      (node (ref "R133") (pin "1") (pinfunction "1_1") (pintype "unspecified"))
      (node (ref "R135") (pin "2") (pinfunction "2_2") (pintype "input"))
      (node (ref "R137") (pin "2") (pinfunction "2_2") (pintype "input"))
      (node (ref "R138") (pin "2") (pinfunction "2_2") (pintype "unspecified"))
      (node (ref "R139") (pin "1") (pinfunction "1_1") (pintype "unspecified"))
      (node (ref "R140") (pin "1") (pinfunction "1_1") (pintype "input"))
      (node (ref "R141") (pin "1") (pinfunction "1_1") (pintype "input"))
      (node (ref "R15") (pin "1") (pinfunction "1_1") (pintype "unspecified"))
      (node (ref "R152") (pin "2") (pinfunction "2_2") (pintype "unspecified"))
      (node (ref "R153") (pin "2") (pinfunction "2_2") (pintype "unspecified"))
      (node (ref "R155") (pin "2") (pinfunction "2_2") (pintype "input"))
      (node (ref "R157") (pin "2") (pinfunction "2_2") (pintype "unspecified"))
      (node (ref "R16") (pin "1") (pinfunction "1_1") (pintype "unspecified"))
      (node (ref "R160") (pin "2") (pinfunction "2_2") (pintype "unspecified"))
      (node (ref "R166") (pin "2") (pinfunction "2_2") (pintype "unspecified"))
      (node (ref "R172") (pin "1") (pinfunction "1_1") (pintype "input"))
      (node (ref "R173") (pin "1") (pinfunction "1_1") (pintype "input"))
      (node (ref "R183") (pin "2") (pinfunction "2_2") (pintype "unspecified"))
      (node (ref "R20") (pin "1") (pinfunction "1_1") (pintype "unspecified"))
      (node (ref "R22") (pin "2") (pinfunction "2_2") (pintype "unspecified"))
      (node (ref "R24") (pin "1") (pinfunction "1_1") (pintype "unspecified"))
      (node (ref "R28") (pin "1") (pinfunction "1_1") (pintype "unspecified"))
      (node (ref "R30") (pin "2") (pinfunction "2_2") (pintype "unspecified"))
      (node (ref "R32") (pin "1") (pinfunction "1_1") (pintype "unspecified"))
      (node (ref "R36") (pin "1") (pinfunction "1_1") (pintype "unspecified"))
      (node (ref "R38") (pin "2") (pinfunction "2_2") (pintype "unspecified"))
      (node (ref "R40") (pin "1") (pinfunction "1_1") (pintype "unspecified"))
      (node (ref "R44") (pin "1") (pinfunction "1_1") (pintype "unspecified"))
      (node (ref "R46") (pin "2") (pinfunction "2_2") (pintype "unspecified"))
      (node (ref "R48") (pin "1") (pinfunction "1_1") (pintype "unspecified"))
      (node (ref "R5") (pin "1") (pinfunction "1_1") (pintype "unspecified"))
      (node (ref "R52") (pin "1") (pinfunction "1_1") (pintype "unspecified"))
      (node (ref "R54") (pin "2") (pinfunction "2_2") (pintype "unspecified"))
      (node (ref "R56") (pin "1") (pinfunction "1_1") (pintype "unspecified"))
      (node (ref "R60") (pin "1") (pinfunction "1_1") (pintype "unspecified"))
      (node (ref "R62") (pin "2") (pinfunction "2_2") (pintype "unspecified"))
      (node (ref "R66") (pin "1") (pinfunction "1_1") (pintype "unspecified"))
      (node (ref "R68") (pin "1") (pinfunction "1_1") (pintype "unspecified"))
      (node (ref "R7") (pin "2") (pinfunction "2_2") (pintype "unspecified"))
      (node (ref "R70") (pin "1") (pinfunction "1_1") (pintype "unspecified"))
      (node (ref "R73") (pin "1") (pinfunction "1_1") (pintype "unspecified"))
      (node (ref "R75") (pin "1") (pinfunction "1_1") (pintype "unspecified"))
      (node (ref "R77") (pin "1") (pinfunction "1_1") (pintype "unspecified"))
      (node (ref "R80") (pin "1") (pinfunction "1_1") (pintype "unspecified"))
      (node (ref "R82") (pin "1") (pinfunction "1_1") (pintype "unspecified"))
      (node (ref "R84") (pin "1") (pinfunction "1_1") (pintype "unspecified"))
      (node (ref "R87") (pin "1") (pinfunction "1_1") (pintype "unspecified"))
      (node (ref "R89") (pin "1") (pinfunction "1_1") (pintype "unspecified"))
      (node (ref "R91") (pin "1") (pinfunction "1_1") (pintype "unspecified"))
      (node (ref "R94") (pin "1") (pinfunction "1_1") (pintype "unspecified"))
      (node (ref "R96") (pin "1") (pinfunction "1_1") (pintype "unspecified"))
      (node (ref "R98") (pin "1") (pinfunction "1_1") (pintype "unspecified"))
      (node (ref "SW1") (pin "1") (pinfunction "1_1") (pintype "unspecified"))
      (node (ref "SW10") (pin "1") (pinfunction "1_1") (pintype "unspecified"))
      (node (ref "SW11") (pin "1") (pinfunction "1_1") (pintype "unspecified"))
      (node (ref "SW12") (pin "1") (pinfunction "1_1") (pintype "unspecified"))
      (node (ref "SW13") (pin "1") (pinfunction "1_1") (pintype "unspecified"))
      (node (ref "SW14") (pin "1") (pinfunction "1_1") (pintype "unspecified"))
      (node (ref "SW15") (pin "4") (pinfunction "4_4") (pintype "unspecified"))
      (node (ref "SW15") (pin "5") (pinfunction "5_5") (pintype "unspecified"))
      (node (ref "SW16") (pin "4") (pinfunction "4_4") (pintype "unspecified"))
      (node (ref "SW16") (pin "5") (pinfunction "5_5") (pintype "unspecified"))
      (node (ref "SW17") (pin "2") (pinfunction "2_2") (pintype "unspecified"))
      (node (ref "SW18") (pin "2") (pinfunction "2_2") (pintype "unspecified"))
      (node (ref "SW19") (pin "2") (pinfunction "2_2") (pintype "unspecified"))
      (node (ref "SW2") (pin "1") (pinfunction "1_1") (pintype "unspecified"))
      (node (ref "SW3") (pin "1") (pinfunction "1_1") (pintype "unspecified"))
      (node (ref "SW4") (pin "1") (pinfunction "1_1") (pintype "unspecified"))
      (node (ref "SW5") (pin "1") (pinfunction "1_1") (pintype "unspecified"))
      (node (ref "SW6") (pin "1") (pinfunction "1_1") (pintype "unspecified"))
      (node (ref "SW7") (pin "1") (pinfunction "1_1") (pintype "unspecified"))
      (node (ref "SW8") (pin "1") (pinfunction "1_1") (pintype "unspecified"))
      (node (ref "SW9") (pin "1") (pinfunction "1_1") (pintype "unspecified"))
      (node (ref "U1") (pin "12") (pinfunction "VSSA/VREF-_12") (pintype "unspecified"))
      (node (ref "U1") (pin "18") (pinfunction "VSS_18") (pintype "unspecified"))
      (node (ref "U1") (pin "31") (pinfunction "VSS_31") (pintype "unspecified"))
      (node (ref "U1") (pin "47") (pinfunction "VSS_47") (pintype "unspecified"))
      (node (ref "U1") (pin "63") (pinfunction "VSS_63") (pintype "unspecified"))
      (node (ref "U10") (pin "10") (pinfunction "VSS_10") (pintype "unspecified"))
      (node (ref "U10") (pin "15") (pinfunction "A0_15") (pintype "unspecified"))
      (node (ref "U10") (pin "16") (pinfunction "A1_16") (pintype "unspecified"))
      (node (ref "U10") (pin "17") (pinfunction "A2_17") (pintype "unspecified"))
      (node (ref "U11") (pin "10") (pinfunction "VSS_10") (pintype "unspecified"))
      (node (ref "U11") (pin "16") (pinfunction "A1_16") (pintype "unspecified"))
      (node (ref "U11") (pin "17") (pinfunction "A2_17") (pintype "unspecified"))
      (node (ref "U12") (pin "10") (pinfunction "VSS_10") (pintype "unspecified"))
      (node (ref "U12") (pin "15") (pinfunction "A0_15") (pintype "unspecified"))
      (node (ref "U12") (pin "17") (pinfunction "A2_17") (pintype "unspecified"))
      (node (ref "U13") (pin "29") (pinfunction "EP_29") (pintype "unspecified"))
      (node (ref "U13") (pin "3") (pinfunction "GND_3") (pintype "unspecified"))
      (node (ref "U15") (pin "4") (pinfunction "GND_4") (pintype "unspecified"))
      (node (ref "U16") (pin "4") (pinfunction "GND_4") (pintype "unspecified"))
      (node (ref "U18") (pin "3") (pinfunction "3_3") (pintype "unspecified"))
      (node (ref "U19") (pin "3") (pinfunction "3_3") (pintype "unspecified"))
      (node (ref "U2") (pin "15") (pinfunction "RSAGND_15") (pintype "unspecified"))
      (node (ref "U2") (pin "16") (pinfunction "RSAGND_16") (pintype "unspecified"))
      (node (ref "U2") (pin "21") (pinfunction "RSBGND_21") (pintype "unspecified"))
      (node (ref "U2") (pin "22") (pinfunction "RSBGND_22") (pintype "unspecified"))
      (node (ref "U2") (pin "29") (pinfunction "GND_29") (pintype "unspecified"))
      (node (ref "U2") (pin "30") (pinfunction "GND_30") (pintype "unspecified"))
      (node (ref "U2") (pin "49") (pinfunction "EP_49") (pintype "unspecified"))
      (node (ref "U2") (pin "8") (pinfunction "GND_8") (pintype "unspecified"))
      (node (ref "U20") (pin "1") (pinfunction "A0_1") (pintype "unspecified"))
      (node (ref "U20") (pin "12") (pinfunction "GND_12") (pintype "unspecified"))
      (node (ref "U20") (pin "2") (pinfunction "A1_2") (pintype "unspecified"))
      (node (ref "U20") (pin "21") (pinfunction "A2_21") (pintype "unspecified"))
      (node (ref "U21") (pin "12") (pinfunction "GND_12") (pintype "unspecified"))
      (node (ref "U21") (pin "2") (pinfunction "A1_2") (pintype "unspecified"))
      (node (ref "U21") (pin "21") (pinfunction "A2_21") (pintype "unspecified"))
      (node (ref "U22") (pin "3") (pinfunction "GND_3") (pintype "unspecified"))
      (node (ref "U23") (pin "1") (pinfunction "GND_1") (pintype "unspecified"))
      (node (ref "U24") (pin "2") (pinfunction "GND_2") (pintype "unspecified"))
      (node (ref "U24") (pin "4") (pinfunction "ADD0_4") (pintype "unspecified"))
      (node (ref "U25") (pin "2") (pinfunction "GND_2") (pintype "unspecified"))
      (node (ref "U26") (pin "1") (pinfunction "GND_1") (pintype "unspecified"))
      (node (ref "U29") (pin "14") (pinfunction "AGND_14") (pintype "input"))
      (node (ref "U29") (pin "17") (pinfunction "EP_17") (pintype "input"))
      (node (ref "U29") (pin "8") (pinfunction "LDAC#_8") (pintype "input"))
      (node (ref "U3") (pin "15") (pinfunction "RSAGND_15") (pintype "unspecified"))
      (node (ref "U3") (pin "16") (pinfunction "RSAGND_16") (pintype "unspecified"))
      (node (ref "U3") (pin "21") (pinfunction "RSBGND_21") (pintype "unspecified"))
      (node (ref "U3") (pin "22") (pinfunction "RSBGND_22") (pintype "unspecified"))
      (node (ref "U3") (pin "29") (pinfunction "GND_29") (pintype "unspecified"))
      (node (ref "U3") (pin "30") (pinfunction "GND_30") (pintype "unspecified"))
      (node (ref "U3") (pin "49") (pinfunction "EP_49") (pintype "unspecified"))
      (node (ref "U3") (pin "8") (pinfunction "GND_8") (pintype "unspecified"))
      (node (ref "U30") (pin "2") (pinfunction "GND_2") (pintype "input"))
      (node (ref "U30") (pin "4") (pinfunction "GND_4") (pintype "input"))
      (node (ref "U31") (pin "1") (pinfunction "GND_1") (pintype "unspecified"))
      (node (ref "U4") (pin "15") (pinfunction "RSAGND_15") (pintype "unspecified"))
      (node (ref "U4") (pin "16") (pinfunction "RSAGND_16") (pintype "unspecified"))
      (node (ref "U4") (pin "21") (pinfunction "RSBGND_21") (pintype "unspecified"))
      (node (ref "U4") (pin "22") (pinfunction "RSBGND_22") (pintype "unspecified"))
      (node (ref "U4") (pin "29") (pinfunction "GND_29") (pintype "unspecified"))
      (node (ref "U4") (pin "30") (pinfunction "GND_30") (pintype "unspecified"))
      (node (ref "U4") (pin "49") (pinfunction "EP_49") (pintype "unspecified"))
      (node (ref "U4") (pin "8") (pinfunction "GND_8") (pintype "unspecified"))
      (node (ref "U5") (pin "15") (pinfunction "RSAGND_15") (pintype "unspecified"))
      (node (ref "U5") (pin "16") (pinfunction "RSAGND_16") (pintype "unspecified"))
      (node (ref "U5") (pin "21") (pinfunction "RSBGND_21") (pintype "unspecified"))
      (node (ref "U5") (pin "22") (pinfunction "RSBGND_22") (pintype "unspecified"))
      (node (ref "U5") (pin "29") (pinfunction "GND_29") (pintype "unspecified"))
      (node (ref "U5") (pin "30") (pinfunction "GND_30") (pintype "unspecified"))
      (node (ref "U5") (pin "49") (pinfunction "EP_49") (pintype "unspecified"))
      (node (ref "U5") (pin "8") (pinfunction "GND_8") (pintype "unspecified"))
      (node (ref "U6") (pin "15") (pinfunction "RSAGND_15") (pintype "unspecified"))
      (node (ref "U6") (pin "16") (pinfunction "RSAGND_16") (pintype "unspecified"))
      (node (ref "U6") (pin "21") (pinfunction "RSBGND_21") (pintype "unspecified"))
      (node (ref "U6") (pin "22") (pinfunction "RSBGND_22") (pintype "unspecified"))
      (node (ref "U6") (pin "29") (pinfunction "GND_29") (pintype "unspecified"))
      (node (ref "U6") (pin "30") (pinfunction "GND_30") (pintype "unspecified"))
      (node (ref "U6") (pin "49") (pinfunction "EP_49") (pintype "unspecified"))
      (node (ref "U6") (pin "8") (pinfunction "GND_8") (pintype "unspecified"))
      (node (ref "U7") (pin "15") (pinfunction "RSAGND_15") (pintype "unspecified"))
      (node (ref "U7") (pin "16") (pinfunction "RSAGND_16") (pintype "unspecified"))
      (node (ref "U7") (pin "21") (pinfunction "RSBGND_21") (pintype "unspecified"))
      (node (ref "U7") (pin "22") (pinfunction "RSBGND_22") (pintype "unspecified"))
      (node (ref "U7") (pin "29") (pinfunction "GND_29") (pintype "unspecified"))
      (node (ref "U7") (pin "30") (pinfunction "GND_30") (pintype "unspecified"))
      (node (ref "U7") (pin "49") (pinfunction "EP_49") (pintype "unspecified"))
      (node (ref "U7") (pin "8") (pinfunction "GND_8") (pintype "unspecified"))
      (node (ref "U8") (pin "15") (pinfunction "RSAGND_15") (pintype "unspecified"))
      (node (ref "U8") (pin "16") (pinfunction "RSAGND_16") (pintype "unspecified"))
      (node (ref "U8") (pin "21") (pinfunction "RSBGND_21") (pintype "unspecified"))
      (node (ref "U8") (pin "22") (pinfunction "RSBGND_22") (pintype "unspecified"))
      (node (ref "U8") (pin "29") (pinfunction "GND_29") (pintype "unspecified"))
      (node (ref "U8") (pin "30") (pinfunction "GND_30") (pintype "unspecified"))
      (node (ref "U8") (pin "49") (pinfunction "EP_49") (pintype "unspecified"))
      (node (ref "U8") (pin "8") (pinfunction "GND_8") (pintype "unspecified"))
      (node (ref "U9") (pin "1") (pinfunction "GND_1") (pintype "unspecified"))
      (node (ref "U9") (pin "40") (pinfunction "GND_40") (pintype "unspecified"))
      (node (ref "U9") (pin "41") (pinfunction "GND_41") (pintype "unspecified"))
      (node (ref "USB1") (pin "13") (pinfunction "EH_13") (pintype "unspecified"))
      (node (ref "USB1") (pin "14") (pinfunction "EH_14") (pintype "unspecified"))
      (node (ref "USB1") (pin "A1B12") (pinfunction "GND_A1B12") (pintype "unspecified"))
      (node (ref "USB1") (pin "B1A12") (pinfunction "GND_B1A12") (pintype "unspecified"))
      (node (ref "USB2") (pin "13") (pinfunction "EH_13") (pintype "unspecified"))
      (node (ref "USB2") (pin "14") (pinfunction "EH_14") (pintype "unspecified"))
      (node (ref "USB2") (pin "A1B12") (pinfunction "GND_A1B12") (pintype "unspecified"))
      (node (ref "USB2") (pin "B1A12") (pinfunction "GND_B1A12") (pintype "unspecified"))
    )
    (net (code "177") (name "Net-(D2-I{slash}O1-Pad1)") (class "Default")
      (node (ref "D2") (pin "1") (pinfunction "I/O1_1") (pintype "unspecified"))
      (node (ref "R164") (pin "2") (pinfunction "2_2") (pintype "input"))
    )
    (net (code "178") (name "Net-(D2-I{slash}O2-Pad3)") (class "Default")
      (node (ref "D2") (pin "3") (pinfunction "I/O2_3") (pintype "unspecified"))
      (node (ref "R163") (pin "2") (pinfunction "2_2") (pintype "input"))
    )
    (net (code "179") (name "Net-(DP1-Pad2)") (class "Default")
      (node (ref "DP1") (pin "2") (pinfunction "2_2") (pintype "unspecified"))
      (node (ref "R10") (pin "2") (pinfunction "2_2") (pintype "unspecified"))
    )
    (net (code "180") (name "Net-(DP1-Pad3)") (class "Default")
      (node (ref "DP1") (pin "3") (pinfunction "3_3") (pintype "unspecified"))
      (node (ref "R11") (pin "2") (pinfunction "2_2") (pintype "unspecified"))
    )
    (net (code "181") (name "Net-(DP2-Pad2)") (class "Default")
      (node (ref "DP2") (pin "2") (pinfunction "2_2") (pintype "unspecified"))
      (node (ref "R12") (pin "2") (pinfunction "2_2") (pintype "unspecified"))
    )
    (net (code "182") (name "Net-(DP2-Pad3)") (class "Default")
      (node (ref "DP2") (pin "3") (pinfunction "3_3") (pintype "unspecified"))
      (node (ref "R13") (pin "2") (pinfunction "2_2") (pintype "unspecified"))
    )
    (net (code "183") (name "Net-(DP3-Pad2)") (class "Default")
      (node (ref "DP3") (pin "2") (pinfunction "2_2") (pintype "unspecified"))
      (node (ref "R14") (pin "2") (pinfunction "2_2") (pintype "unspecified"))
    )
    (net (code "184") (name "Net-(DP3-Pad3)") (class "Default")
      (node (ref "DP3") (pin "3") (pinfunction "3_3") (pintype "unspecified"))
      (node (ref "R15") (pin "2") (pinfunction "2_2") (pintype "unspecified"))
    )
    (net (code "185") (name "Net-(DP4-Pad2)") (class "Default")
      (node (ref "DP4") (pin "2") (pinfunction "2_2") (pintype "unspecified"))
      (node (ref "R65") (pin "2") (pinfunction "2_2") (pintype "unspecified"))
    )
    (net (code "186") (name "Net-(DP4-Pad3)") (class "Default")
      (node (ref "DP4") (pin "3") (pinfunction "3_3") (pintype "unspecified"))
      (node (ref "R66") (pin "2") (pinfunction "2_2") (pintype "unspecified"))
    )
    (net (code "187") (name "Net-(DP5-Pad2)") (class "Default")
      (node (ref "DP5") (pin "2") (pinfunction "2_2") (pintype "unspecified"))
      (node (ref "R67") (pin "2") (pinfunction "2_2") (pintype "unspecified"))
    )
    (net (code "188") (name "Net-(DP5-Pad3)") (class "Default")
      (node (ref "DP5") (pin "3") (pinfunction "3_3") (pintype "unspecified"))
      (node (ref "R68") (pin "2") (pinfunction "2_2") (pintype "unspecified"))
    )
    (net (code "189") (name "Net-(DP6-Pad2)") (class "Default")
      (node (ref "DP6") (pin "2") (pinfunction "2_2") (pintype "unspecified"))
      (node (ref "R69") (pin "2") (pinfunction "2_2") (pintype "unspecified"))
    )
    (net (code "190") (name "Net-(DP6-Pad3)") (class "Default")
      (node (ref "DP6") (pin "3") (pinfunction "3_3") (pintype "unspecified"))
      (node (ref "R70") (pin "2") (pinfunction "2_2") (pintype "unspecified"))
    )
    (net (code "191") (name "Net-(DP7-Pad2)") (class "Default")
      (node (ref "DP7") (pin "2") (pinfunction "2_2") (pintype "unspecified"))
      (node (ref "R72") (pin "2") (pinfunction "2_2") (pintype "unspecified"))
    )
    (net (code "192") (name "Net-(DP7-Pad3)") (class "Default")
      (node (ref "DP7") (pin "3") (pinfunction "3_3") (pintype "unspecified"))
      (node (ref "R73") (pin "2") (pinfunction "2_2") (pintype "unspecified"))
    )
    (net (code "193") (name "Net-(DP8-Pad2)") (class "Default")
      (node (ref "DP8") (pin "2") (pinfunction "2_2") (pintype "unspecified"))
      (node (ref "R74") (pin "2") (pinfunction "2_2") (pintype "unspecified"))
    )
    (net (code "194") (name "Net-(DP8-Pad3)") (class "Default")
      (node (ref "DP8") (pin "3") (pinfunction "3_3") (pintype "unspecified"))
      (node (ref "R75") (pin "2") (pinfunction "2_2") (pintype "unspecified"))
    )
    (net (code "195") (name "Net-(DP9-Pad2)") (class "Default")
      (node (ref "DP9") (pin "2") (pinfunction "2_2") (pintype "unspecified"))
      (node (ref "R76") (pin "2") (pinfunction "2_2") (pintype "unspecified"))
    )
    (net (code "196") (name "Net-(DP9-Pad3)") (class "Default")
      (node (ref "DP9") (pin "3") (pinfunction "3_3") (pintype "unspecified"))
      (node (ref "R77") (pin "2") (pinfunction "2_2") (pintype "unspecified"))
    )
    (net (code "197") (name "Net-(DP10-Pad2)") (class "Default")
      (node (ref "DP10") (pin "2") (pinfunction "2_2") (pintype "unspecified"))
      (node (ref "R79") (pin "2") (pinfunction "2_2") (pintype "unspecified"))
    )
    (net (code "198") (name "Net-(DP10-Pad3)") (class "Default")
      (node (ref "DP10") (pin "3") (pinfunction "3_3") (pintype "unspecified"))
      (node (ref "R80") (pin "2") (pinfunction "2_2") (pintype "unspecified"))
    )
    (net (code "199") (name "Net-(DP11-Pad2)") (class "Default")
      (node (ref "DP11") (pin "2") (pinfunction "2_2") (pintype "unspecified"))
      (node (ref "R81") (pin "2") (pinfunction "2_2") (pintype "unspecified"))
    )
    (net (code "200") (name "Net-(DP11-Pad3)") (class "Default")
      (node (ref "DP11") (pin "3") (pinfunction "3_3") (pintype "unspecified"))
      (node (ref "R82") (pin "2") (pinfunction "2_2") (pintype "unspecified"))
    )
    (net (code "201") (name "Net-(DP12-Pad2)") (class "Default")
      (node (ref "DP12") (pin "2") (pinfunction "2_2") (pintype "unspecified"))
      (node (ref "R83") (pin "2") (pinfunction "2_2") (pintype "unspecified"))
    )
    (net (code "202") (name "Net-(DP12-Pad3)") (class "Default")
      (node (ref "DP12") (pin "3") (pinfunction "3_3") (pintype "unspecified"))
      (node (ref "R84") (pin "2") (pinfunction "2_2") (pintype "unspecified"))
    )
    (net (code "203") (name "Net-(DP13-Pad2)") (class "Default")
      (node (ref "DP13") (pin "2") (pinfunction "2_2") (pintype "unspecified"))
      (node (ref "R86") (pin "2") (pinfunction "2_2") (pintype "unspecified"))
    )
    (net (code "204") (name "Net-(DP13-Pad3)") (class "Default")
      (node (ref "DP13") (pin "3") (pinfunction "3_3") (pintype "unspecified"))
      (node (ref "R87") (pin "2") (pinfunction "2_2") (pintype "unspecified"))
    )
    (net (code "205") (name "Net-(DP14-Pad2)") (class "Default")
      (node (ref "DP14") (pin "2") (pinfunction "2_2") (pintype "unspecified"))
      (node (ref "R88") (pin "2") (pinfunction "2_2") (pintype "unspecified"))
    )
    (net (code "206") (name "Net-(DP14-Pad3)") (class "Default")
      (node (ref "DP14") (pin "3") (pinfunction "3_3") (pintype "unspecified"))
      (node (ref "R89") (pin "2") (pinfunction "2_2") (pintype "unspecified"))
    )
    (net (code "207") (name "Net-(DP15-Pad2)") (class "Default")
      (node (ref "DP15") (pin "2") (pinfunction "2_2") (pintype "unspecified"))
      (node (ref "R90") (pin "2") (pinfunction "2_2") (pintype "unspecified"))
    )
    (net (code "208") (name "Net-(DP15-Pad3)") (class "Default")
      (node (ref "DP15") (pin "3") (pinfunction "3_3") (pintype "unspecified"))
      (node (ref "R91") (pin "2") (pinfunction "2_2") (pintype "unspecified"))
    )
    (net (code "209") (name "Net-(DP16-Pad2)") (class "Default")
      (node (ref "DP16") (pin "2") (pinfunction "2_2") (pintype "unspecified"))
      (node (ref "R93") (pin "2") (pinfunction "2_2") (pintype "unspecified"))
    )
    (net (code "210") (name "Net-(DP16-Pad3)") (class "Default")
      (node (ref "DP16") (pin "3") (pinfunction "3_3") (pintype "unspecified"))
      (node (ref "R94") (pin "2") (pinfunction "2_2") (pintype "unspecified"))
    )
    (net (code "211") (name "Net-(DP17-Pad2)") (class "Default")
      (node (ref "DP17") (pin "2") (pinfunction "2_2") (pintype "unspecified"))
      (node (ref "R95") (pin "2") (pinfunction "2_2") (pintype "unspecified"))
    )
    (net (code "212") (name "Net-(DP17-Pad3)") (class "Default")
      (node (ref "DP17") (pin "3") (pinfunction "3_3") (pintype "unspecified"))
      (node (ref "R96") (pin "2") (pinfunction "2_2") (pintype "unspecified"))
    )
    (net (code "213") (name "Net-(DP18-Pad2)") (class "Default")
      (node (ref "DP18") (pin "2") (pinfunction "2_2") (pintype "unspecified"))
      (node (ref "R97") (pin "2") (pinfunction "2_2") (pintype "unspecified"))
    )
    (net (code "214") (name "Net-(DP18-Pad3)") (class "Default")
      (node (ref "DP18") (pin "3") (pinfunction "3_3") (pintype "unspecified"))
      (node (ref "R98") (pin "2") (pinfunction "2_2") (pintype "unspecified"))
    )
    (net (code "215") (name "Net-(DP19-Pad2)") (class "Default")
      (node (ref "DP19") (pin "2") (pinfunction "2_2") (pintype "unspecified"))
      (node (ref "R100") (pin "2") (pinfunction "2_2") (pintype "unspecified"))
    )
    (net (code "216") (name "Net-(DP19-Pad3)") (class "Default")
      (node (ref "DP19") (pin "3") (pinfunction "3_3") (pintype "unspecified"))
      (node (ref "R101") (pin "2") (pinfunction "2_2") (pintype "unspecified"))
    )
    (net (code "217") (name "Net-(DP20-Pad2)") (class "Default")
      (node (ref "DP20") (pin "2") (pinfunction "2_2") (pintype "unspecified"))
      (node (ref "R102") (pin "2") (pinfunction "2_2") (pintype "unspecified"))
    )
    (net (code "218") (name "Net-(DP20-Pad3)") (class "Default")
      (node (ref "DP20") (pin "3") (pinfunction "3_3") (pintype "unspecified"))
      (node (ref "R103") (pin "2") (pinfunction "2_2") (pintype "unspecified"))
    )
    (net (code "219") (name "Net-(DP21-Pad2)") (class "Default")
      (node (ref "DP21") (pin "2") (pinfunction "2_2") (pintype "unspecified"))
      (node (ref "R104") (pin "2") (pinfunction "2_2") (pintype "unspecified"))
    )
    (net (code "220") (name "Net-(DP21-Pad3)") (class "Default")
      (node (ref "DP21") (pin "3") (pinfunction "3_3") (pintype "unspecified"))
      (node (ref "R105") (pin "2") (pinfunction "2_2") (pintype "unspecified"))
    )
    (net (code "221") (name "Net-(LED1-A)") (class "Default")
      (node (ref "LED1") (pin "1") (pinfunction "A_1") (pintype "unspecified"))
      (node (ref "U1") (pin "2") (pinfunction "PC13_2") (pintype "unspecified"))
    )
    (net (code "222") (name "Net-(LED1-K)") (class "Default")
      (node (ref "LED1") (pin "2") (pinfunction "K_2") (pintype "unspecified"))
      (node (ref "R172") (pin "2") (pinfunction "2_2") (pintype "input"))
    )
    (net (code "223") (name "Net-(LED2-A)") (class "Default")
      (node (ref "LED2") (pin "1") (pinfunction "A_1") (pintype "unspecified"))
      (node (ref "U9") (pin "9") (pinfunction "IO16_9") (pintype "unspecified"))
    )
    (net (code "224") (name "Net-(LED2-K)") (class "Default")
      (node (ref "LED2") (pin "2") (pinfunction "K_2") (pintype "unspecified"))
      (node (ref "R173") (pin "2") (pinfunction "2_2") (pintype "input"))
    )
    (net (code "225") (name "Net-(Q1-B)") (class "Default")
      (node (ref "Q1") (pin "1") (pinfunction "B_1") (pintype "unspecified"))
      (node (ref "R131") (pin "1") (pinfunction "1_1") (pintype "unspecified"))
    )
    (net (code "226") (name "Net-(Q2-B)") (class "Default")
      (node (ref "Q2") (pin "1") (pinfunction "B_1") (pintype "unspecified"))
      (node (ref "R130") (pin "1") (pinfunction "1_1") (pintype "unspecified"))
    )
    (net (code "227") (name "Net-(Q4-B)") (class "Default")
      (node (ref "Q4") (pin "1") (pinfunction "B_1") (pintype "unspecified"))
      (node (ref "R144") (pin "1") (pinfunction "1_1") (pintype "unspecified"))
    )
    (net (code "228") (name "Net-(Q5-B)") (class "Default")
      (node (ref "Q5") (pin "1") (pinfunction "B_1") (pintype "unspecified"))
      (node (ref "R149") (pin "1") (pinfunction "1_1") (pintype "unspecified"))
    )
    (net (code "229") (name "Net-(Q6-B)") (class "Default")
      (node (ref "Q6") (pin "1") (pinfunction "B_1") (pintype "unspecified"))
      (node (ref "R169") (pin "1") (pinfunction "1_1") (pintype "unspecified"))
    )
    (net (code "230") (name "Net-(U2-LTH)") (class "Default")
      (node (ref "R1") (pin "2") (pinfunction "2_2") (pintype "unspecified"))
      (node (ref "U2") (pin "7") (pinfunction "LTH_7") (pintype "unspecified"))
    )
    (net (code "231") (name "Net-(U2-OSCM)") (class "Default")
      (node (ref "R5") (pin "2") (pinfunction "2_2") (pintype "unspecified"))
      (node (ref "R6") (pin "1") (pinfunction "1_1") (pintype "unspecified"))
      (node (ref "R7") (pin "1") (pinfunction "1_1") (pintype "unspecified"))
      (node (ref "U2") (pin "35") (pinfunction "OSCM_35") (pintype "unspecified"))
    )
    (net (code "232") (name "Net-(U3-LTH)") (class "Default")
      (node (ref "R16") (pin "2") (pinfunction "2_2") (pintype "unspecified"))
      (node (ref "U3") (pin "7") (pinfunction "LTH_7") (pintype "unspecified"))
    )
    (net (code "233") (name "Net-(U3-OSCM)") (class "Default")
      (node (ref "R20") (pin "2") (pinfunction "2_2") (pintype "unspecified"))
      (node (ref "R21") (pin "1") (pinfunction "1_1") (pintype "unspecified"))
      (node (ref "R22") (pin "1") (pinfunction "1_1") (pintype "unspecified"))
      (node (ref "U3") (pin "35") (pinfunction "OSCM_35") (pintype "unspecified"))
    )
    (net (code "234") (name "Net-(U4-LTH)") (class "Default")
      (node (ref "R24") (pin "2") (pinfunction "2_2") (pintype "unspecified"))
      (node (ref "U4") (pin "7") (pinfunction "LTH_7") (pintype "unspecified"))
    )
    (net (code "235") (name "Net-(U4-OSCM)") (class "Default")
      (node (ref "R28") (pin "2") (pinfunction "2_2") (pintype "unspecified"))
      (node (ref "R29") (pin "1") (pinfunction "1_1") (pintype "unspecified"))
      (node (ref "R30") (pin "1") (pinfunction "1_1") (pintype "unspecified"))
      (node (ref "U4") (pin "35") (pinfunction "OSCM_35") (pintype "unspecified"))
    )
    (net (code "236") (name "Net-(U5-LTH)") (class "Default")
      (node (ref "R32") (pin "2") (pinfunction "2_2") (pintype "unspecified"))
      (node (ref "U5") (pin "7") (pinfunction "LTH_7") (pintype "unspecified"))
    )
    (net (code "237") (name "Net-(U5-OSCM)") (class "Default")
      (node (ref "R36") (pin "2") (pinfunction "2_2") (pintype "unspecified"))
      (node (ref "R37") (pin "1") (pinfunction "1_1") (pintype "unspecified"))
      (node (ref "R38") (pin "1") (pinfunction "1_1") (pintype "unspecified"))
      (node (ref "U5") (pin "35") (pinfunction "OSCM_35") (pintype "unspecified"))
    )
    (net (code "238") (name "Net-(U6-LTH)") (class "Default")
      (node (ref "R40") (pin "2") (pinfunction "2_2") (pintype "unspecified"))
      (node (ref "U6") (pin "7") (pinfunction "LTH_7") (pintype "unspecified"))
    )
    (net (code "239") (name "Net-(U6-OSCM)") (class "Default")
      (node (ref "R44") (pin "2") (pinfunction "2_2") (pintype "unspecified"))
      (node (ref "R45") (pin "1") (pinfunction "1_1") (pintype "unspecified"))
      (node (ref "R46") (pin "1") (pinfunction "1_1") (pintype "unspecified"))
      (node (ref "U6") (pin "35") (pinfunction "OSCM_35") (pintype "unspecified"))
    )
    (net (code "240") (name "Net-(U7-LTH)") (class "Default")
      (node (ref "R48") (pin "2") (pinfunction "2_2") (pintype "unspecified"))
      (node (ref "U7") (pin "7") (pinfunction "LTH_7") (pintype "unspecified"))
    )
    (net (code "241") (name "Net-(U7-OSCM)") (class "Default")
      (node (ref "R52") (pin "2") (pinfunction "2_2") (pintype "unspecified"))
      (node (ref "R53") (pin "1") (pinfunction "1_1") (pintype "unspecified"))
      (node (ref "R54") (pin "1") (pinfunction "1_1") (pintype "unspecified"))
      (node (ref "U7") (pin "35") (pinfunction "OSCM_35") (pintype "unspecified"))
    )
    (net (code "242") (name "Net-(U8-LTH)") (class "Default")
      (node (ref "R56") (pin "2") (pinfunction "2_2") (pintype "unspecified"))
      (node (ref "U8") (pin "7") (pinfunction "LTH_7") (pintype "unspecified"))
    )
    (net (code "243") (name "Net-(U8-OSCM)") (class "Default")
      (node (ref "R60") (pin "2") (pinfunction "2_2") (pintype "unspecified"))
      (node (ref "R61") (pin "1") (pinfunction "1_1") (pintype "unspecified"))
      (node (ref "R62") (pin "1") (pinfunction "1_1") (pintype "unspecified"))
      (node (ref "U8") (pin "35") (pinfunction "OSCM_35") (pintype "unspecified"))
    )
    (net (code "244") (name "Net-(U10-RESET#)") (class "Default")
      (node (ref "R178") (pin "1") (pinfunction "1_1") (pintype "unspecified"))
      (node (ref "U10") (pin "18") (pinfunction "RESET#_18") (pintype "unspecified"))
    )
    (net (code "245") (name "Net-(U11-A0)") (class "Default")
      (node (ref "R106") (pin "1") (pinfunction "1_1") (pintype "unspecified"))
      (node (ref "U11") (pin "15") (pinfunction "A0_15") (pintype "unspecified"))
    )
    (net (code "246") (name "Net-(U11-RESET#)") (class "Default")
      (node (ref "R177") (pin "1") (pinfunction "1_1") (pintype "unspecified"))
      (node (ref "U11") (pin "18") (pinfunction "RESET#_18") (pintype "unspecified"))
    )
    (net (code "247") (name "Net-(U12-A1)") (class "Default")
      (node (ref "R114") (pin "1") (pinfunction "1_1") (pintype "unspecified"))
      (node (ref "U12") (pin "16") (pinfunction "A1_16") (pintype "unspecified"))
    )
    (net (code "248") (name "Net-(U12-RESET#)") (class "Default")
      (node (ref "R176") (pin "1") (pinfunction "1_1") (pintype "unspecified"))
      (node (ref "U12") (pin "18") (pinfunction "RESET#_18") (pintype "unspecified"))
    )
    (net (code "249") (name "Net-(U13-VBUS)") (class "Default")
      (node (ref "R117") (pin "1") (pinfunction "1_1") (pintype "input"))
      (node (ref "R118") (pin "1") (pinfunction "1_1") (pintype "input"))
      (node (ref "U13") (pin "8") (pinfunction "VBUS_8") (pintype "unspecified"))
    )
    (net (code "250") (name "Net-(U15-CB)") (class "Default")
      (node (ref "C35") (pin "2") (pinfunction "2_2") (pintype "unspecified"))
      (node (ref "U15") (pin "6") (pinfunction "CB_6") (pintype "unspecified"))
    )
    (net (code "251") (name "Net-(U15-FB)") (class "Default")
      (node (ref "R134") (pin "2") (pinfunction "2_2") (pintype "input"))
      (node (ref "R135") (pin "1") (pinfunction "1_1") (pintype "input"))
      (node (ref "U15") (pin "1") (pinfunction "FB_1") (pintype "unspecified"))
    )
    (net (code "252") (name "Net-(U15-SW)") (class "Default")
      (node (ref "C35") (pin "1") (pinfunction "1_1") (pintype "unspecified"))
      (node (ref "L2") (pin "1") (pinfunction "1_1") (pintype "unspecified"))
      (node (ref "U15") (pin "5") (pinfunction "SW_5") (pintype "unspecified"))
    )
    (net (code "253") (name "Net-(U16-CB)") (class "Default")
      (node (ref "C34") (pin "2") (pinfunction "2_2") (pintype "unspecified"))
      (node (ref "U16") (pin "6") (pinfunction "CB_6") (pintype "unspecified"))
    )
    (net (code "254") (name "Net-(U16-FB)") (class "Default")
      (node (ref "R136") (pin "2") (pinfunction "2_2") (pintype "input"))
      (node (ref "R137") (pin "1") (pinfunction "1_1") (pintype "input"))
      (node (ref "U16") (pin "1") (pinfunction "FB_1") (pintype "unspecified"))
    )
    (net (code "255") (name "Net-(U16-SW)") (class "Default")
      (node (ref "C34") (pin "1") (pinfunction "1_1") (pintype "unspecified"))
      (node (ref "L1") (pin "1") (pinfunction "1_1") (pintype "unspecified"))
      (node (ref "U16") (pin "5") (pinfunction "SW_5") (pintype "unspecified"))
    )
    (net (code "256") (name "Net-(U22-FB)") (class "Default")
      (node (ref "R157") (pin "1") (pinfunction "1_1") (pintype "unspecified"))
      (node (ref "R158") (pin "2") (pinfunction "2_2") (pintype "input"))
      (node (ref "U22") (pin "6") (pinfunction "FB_6") (pintype "unspecified"))
    )
    (net (code "257") (name "Net-(U22-PG)") (class "Default")
      (node (ref "R156") (pin "1") (pinfunction "1_1") (pintype "unspecified"))
      (node (ref "U22") (pin "4") (pinfunction "PG_4") (pintype "unspecified"))
    )
    (net (code "258") (name "Net-(U22-SW)") (class "Default")
      (node (ref "L3") (pin "2") (pinfunction "2_2") (pintype "unspecified"))
      (node (ref "U22") (pin "2") (pinfunction "SW_2") (pintype "unspecified"))
    )
    (net (code "259") (name "Net-(U23-PR1)") (class "Default")
      (node (ref "R159") (pin "2") (pinfunction "2_2") (pintype "unspecified"))
      (node (ref "R160") (pin "1") (pinfunction "1_1") (pintype "unspecified"))
      (node (ref "U23") (pin "4") (pinfunction "PR1_4") (pintype "unspecified"))
    )
    (net (code "260") (name "Net-(U23-ST)") (class "Default")
      (node (ref "R161") (pin "1") (pinfunction "1_1") (pintype "unspecified"))
      (node (ref "TP29") (pin "1") (pinfunction "1_1") (pintype "unspecified"))
      (node (ref "U23") (pin "8") (pinfunction "ST_8") (pintype "unspecified"))
    )
    (net (code "261") (name "Net-(U26-PR1)") (class "Default")
      (node (ref "R165") (pin "2") (pinfunction "2_2") (pintype "unspecified"))
      (node (ref "R166") (pin "1") (pinfunction "1_1") (pintype "unspecified"))
      (node (ref "U26") (pin "4") (pinfunction "PR1_4") (pintype "unspecified"))
    )
    (net (code "262") (name "Net-(U26-ST)") (class "Default")
      (node (ref "R167") (pin "1") (pinfunction "1_1") (pintype "unspecified"))
      (node (ref "TP30") (pin "1") (pinfunction "1_1") (pintype "unspecified"))
      (node (ref "U26") (pin "8") (pinfunction "ST_8") (pintype "unspecified"))
    )
    (net (code "263") (name "Net-(U31-PR1)") (class "Default")
      (node (ref "R182") (pin "2") (pinfunction "2_2") (pintype "unspecified"))
      (node (ref "R183") (pin "1") (pinfunction "1_1") (pintype "unspecified"))
      (node (ref "U31") (pin "4") (pinfunction "PR1_4") (pintype "unspecified"))
    )
    (net (code "264") (name "Net-(U31-ST)") (class "Default")
      (node (ref "R184") (pin "1") (pinfunction "1_1") (pintype "unspecified"))
      (node (ref "TP31") (pin "1") (pinfunction "1_1") (pintype "unspecified"))
      (node (ref "U31") (pin "8") (pinfunction "ST_8") (pintype "unspecified"))
    )
    (net (code "265") (name "Net-(USB1-CC1)") (class "Default")
      (node (ref "R115") (pin "2") (pinfunction "2_2") (pintype "input"))
      (node (ref "USB1") (pin "A5") (pinfunction "CC1_A5") (pintype "unspecified"))
    )
    (net (code "266") (name "Net-(USB1-CC2)") (class "Default")
      (node (ref "R116") (pin "2") (pinfunction "2_2") (pintype "input"))
      (node (ref "USB1") (pin "B5") (pinfunction "CC2_B5") (pintype "unspecified"))
    )
    (net (code "267") (name "Net-(USB2-CC1)") (class "Default")
      (node (ref "R140") (pin "2") (pinfunction "2_2") (pintype "input"))
      (node (ref "USB2") (pin "A5") (pinfunction "CC1_A5") (pintype "unspecified"))
    )
    (net (code "268") (name "Net-(USB2-CC2)") (class "Default")
      (node (ref "R141") (pin "2") (pinfunction "2_2") (pintype "input"))
      (node (ref "USB2") (pin "B5") (pinfunction "CC2_B5") (pintype "unspecified"))
    )
    (net (code "269") (name "RTS") (class "Default")
      (node (ref "Q1") (pin "2") (pinfunction "E_2") (pintype "unspecified"))
      (node (ref "R130") (pin "2") (pinfunction "2_2") (pintype "unspecified"))
      (node (ref "U13") (pin "24") (pinfunction "RTS_24") (pintype "unspecified"))
    )
    (net (code "270") (name "SC0") (class "Default")
      (node (ref "H6") (pin "2") (pinfunction "2_2") (pintype "unspecified"))
      (node (ref "U20") (pin "5") (pinfunction "SC0_5") (pintype "unspecified"))
    )
    (net (code "271") (name "SC1") (class "Default")
      (node (ref "H6") (pin "4") (pinfunction "4_4") (pintype "unspecified"))
      (node (ref "U20") (pin "7") (pinfunction "SC1_7") (pintype "unspecified"))
    )
    (net (code "272") (name "SC2") (class "Default")
      (node (ref "H6") (pin "6") (pinfunction "6_6") (pintype "unspecified"))
      (node (ref "U20") (pin "9") (pinfunction "SC2_9") (pintype "unspecified"))
    )
    (net (code "273") (name "SC3") (class "Default")
      (node (ref "H6") (pin "8") (pinfunction "8_8") (pintype "unspecified"))
      (node (ref "U20") (pin "11") (pinfunction "SC3_11") (pintype "unspecified"))
    )
    (net (code "274") (name "SC4") (class "Default")
      (node (ref "H6") (pin "10") (pinfunction "10_10") (pintype "unspecified"))
      (node (ref "U20") (pin "14") (pinfunction "SC4_14") (pintype "unspecified"))
    )
    (net (code "275") (name "SC5") (class "Default")
      (node (ref "H6") (pin "12") (pinfunction "12_12") (pintype "unspecified"))
      (node (ref "U20") (pin "16") (pinfunction "SC5_16") (pintype "unspecified"))
    )
    (net (code "276") (name "SC6") (class "Default")
      (node (ref "H6") (pin "14") (pinfunction "14_14") (pintype "unspecified"))
      (node (ref "U20") (pin "18") (pinfunction "SC6_18") (pintype "unspecified"))
    )
    (net (code "277") (name "SC7") (class "Default")
      (node (ref "H6") (pin "16") (pinfunction "16_16") (pintype "unspecified"))
      (node (ref "U20") (pin "20") (pinfunction "SC7_20") (pintype "unspecified"))
    )
    (net (code "278") (name "SC8") (class "Default")
      (node (ref "H6") (pin "18") (pinfunction "18_18") (pintype "unspecified"))
      (node (ref "U21") (pin "5") (pinfunction "SC0_5") (pintype "unspecified"))
    )
    (net (code "279") (name "SC9") (class "Default")
      (node (ref "H6") (pin "20") (pinfunction "20_20") (pintype "unspecified"))
      (node (ref "U21") (pin "7") (pinfunction "SC1_7") (pintype "unspecified"))
    )
    (net (code "280") (name "SC10") (class "Default")
      (node (ref "H6") (pin "22") (pinfunction "22_22") (pintype "unspecified"))
      (node (ref "U21") (pin "9") (pinfunction "SC2_9") (pintype "unspecified"))
    )
    (net (code "281") (name "SC11") (class "Default")
      (node (ref "H6") (pin "24") (pinfunction "24_24") (pintype "unspecified"))
      (node (ref "U21") (pin "11") (pinfunction "SC3_11") (pintype "unspecified"))
    )
    (net (code "282") (name "SC12") (class "Default")
      (node (ref "H6") (pin "26") (pinfunction "26_26") (pintype "unspecified"))
      (node (ref "U21") (pin "14") (pinfunction "SC4_14") (pintype "unspecified"))
    )
    (net (code "283") (name "SC13") (class "Default")
      (node (ref "H6") (pin "28") (pinfunction "28_28") (pintype "unspecified"))
      (node (ref "U21") (pin "16") (pinfunction "SC5_16") (pintype "unspecified"))
    )
    (net (code "284") (name "SC14") (class "Default")
      (node (ref "H6") (pin "30") (pinfunction "30_30") (pintype "unspecified"))
      (node (ref "U21") (pin "18") (pinfunction "SC6_18") (pintype "unspecified"))
    )
    (net (code "285") (name "SC15") (class "Default")
      (node (ref "H6") (pin "32") (pinfunction "32_32") (pintype "unspecified"))
      (node (ref "U21") (pin "20") (pinfunction "SC7_20") (pintype "unspecified"))
    )
    (net (code "286") (name "SD0") (class "Default")
      (node (ref "H6") (pin "1") (pinfunction "1_1") (pintype "unspecified"))
      (node (ref "U20") (pin "4") (pinfunction "SD0_4") (pintype "unspecified"))
    )
    (net (code "287") (name "SD1") (class "Default")
      (node (ref "H6") (pin "3") (pinfunction "3_3") (pintype "unspecified"))
      (node (ref "U20") (pin "6") (pinfunction "SD1_6") (pintype "unspecified"))
    )
    (net (code "288") (name "SD2") (class "Default")
      (node (ref "H6") (pin "5") (pinfunction "5_5") (pintype "unspecified"))
      (node (ref "U20") (pin "8") (pinfunction "SD2_8") (pintype "unspecified"))
    )
    (net (code "289") (name "SD3") (class "Default")
      (node (ref "H6") (pin "7") (pinfunction "7_7") (pintype "unspecified"))
      (node (ref "U20") (pin "10") (pinfunction "SD3_10") (pintype "unspecified"))
    )
    (net (code "290") (name "SD4") (class "Default")
      (node (ref "H6") (pin "9") (pinfunction "9_9") (pintype "unspecified"))
      (node (ref "U20") (pin "13") (pinfunction "SD4_13") (pintype "unspecified"))
    )
    (net (code "291") (name "SD5") (class "Default")
      (node (ref "H6") (pin "11") (pinfunction "11_11") (pintype "unspecified"))
      (node (ref "U20") (pin "15") (pinfunction "SD5_15") (pintype "unspecified"))
    )
    (net (code "292") (name "SD6") (class "Default")
      (node (ref "H6") (pin "13") (pinfunction "13_13") (pintype "unspecified"))
      (node (ref "U20") (pin "17") (pinfunction "SD6_17") (pintype "unspecified"))
    )
    (net (code "293") (name "SD7") (class "Default")
      (node (ref "H6") (pin "15") (pinfunction "15_15") (pintype "unspecified"))
      (node (ref "U20") (pin "19") (pinfunction "SD7_19") (pintype "unspecified"))
    )
    (net (code "294") (name "SD8") (class "Default")
      (node (ref "H6") (pin "17") (pinfunction "17_17") (pintype "unspecified"))
      (node (ref "U21") (pin "4") (pinfunction "SD0_4") (pintype "unspecified"))
    )
    (net (code "295") (name "SD9") (class "Default")
      (node (ref "H6") (pin "19") (pinfunction "19_19") (pintype "unspecified"))
      (node (ref "U21") (pin "6") (pinfunction "SD1_6") (pintype "unspecified"))
    )
    (net (code "296") (name "SD10") (class "Default")
      (node (ref "H6") (pin "21") (pinfunction "21_21") (pintype "unspecified"))
      (node (ref "U21") (pin "8") (pinfunction "SD2_8") (pintype "unspecified"))
    )
    (net (code "297") (name "SD11") (class "Default")
      (node (ref "H6") (pin "23") (pinfunction "23_23") (pintype "unspecified"))
      (node (ref "U21") (pin "10") (pinfunction "SD3_10") (pintype "unspecified"))
    )
    (net (code "298") (name "SD12") (class "Default")
      (node (ref "H6") (pin "25") (pinfunction "25_25") (pintype "unspecified"))
      (node (ref "U21") (pin "13") (pinfunction "SD4_13") (pintype "unspecified"))
    )
    (net (code "299") (name "SD13") (class "Default")
      (node (ref "H6") (pin "27") (pinfunction "27_27") (pintype "unspecified"))
      (node (ref "U21") (pin "15") (pinfunction "SD5_15") (pintype "unspecified"))
    )
    (net (code "300") (name "SD14") (class "Default")
      (node (ref "H6") (pin "29") (pinfunction "29_29") (pintype "unspecified"))
      (node (ref "U21") (pin "17") (pinfunction "SD6_17") (pintype "unspecified"))
    )
    (net (code "301") (name "SD15") (class "Default")
      (node (ref "H6") (pin "31") (pinfunction "31_31") (pintype "unspecified"))
      (node (ref "U21") (pin "19") (pinfunction "SD7_19") (pintype "unspecified"))
    )
    (net (code "302") (name "SPI_CLK") (class "Default")
      (node (ref "U1") (pin "29") (pinfunction "PB10_29") (pintype "unspecified"))
      (node (ref "U9") (pin "20") (pinfunction "IO12_20") (pintype "unspecified"))
    )
    (net (code "303") (name "SPI_MISO") (class "Default")
      (node (ref "U1") (pin "10") (pinfunction "PC2_10") (pintype "unspecified"))
      (node (ref "U9") (pin "21") (pinfunction "IO13_21") (pintype "unspecified"))
    )
    (net (code "304") (name "SPI_MOSI") (class "Default")
      (node (ref "U1") (pin "36") (pinfunction "PB15_36") (pintype "unspecified"))
      (node (ref "U9") (pin "19") (pinfunction "IO11_19") (pintype "unspecified"))
    )
    (net (code "305") (name "SPI_NSS") (class "Default")
      (node (ref "U1") (pin "33") (pinfunction "PB12_33") (pintype "unspecified"))
      (node (ref "U9") (pin "18") (pinfunction "IO10_18") (pintype "unspecified"))
    )
    (net (code "306") (name "STM_NRESET") (class "Default")
      (node (ref "CN8") (pin "10") (pinfunction "10_10") (pintype "unspecified"))
      (node (ref "Q6") (pin "3") (pinfunction "C_3") (pintype "unspecified"))
      (node (ref "R168") (pin "2") (pinfunction "2_2") (pintype "unspecified"))
      (node (ref "SW19") (pin "1") (pinfunction "1_1") (pintype "unspecified"))
      (node (ref "U1") (pin "7") (pinfunction "NRST_7") (pintype "unspecified"))
    )
    (net (code "307") (name "STM_NRESET_FROM_ESP") (class "Default")
      (node (ref "R169") (pin "2") (pinfunction "2_2") (pintype "unspecified"))
      (node (ref "U9") (pin "29") (pinfunction "IO36_29") (pintype "unspecified"))
    )
    (net (code "308") (name "SWDCLK") (class "Default")
      (node (ref "CN8") (pin "4") (pinfunction "4_4") (pintype "unspecified"))
      (node (ref "U1") (pin "49") (pinfunction "PA14_49") (pintype "unspecified"))
    )
    (net (code "309") (name "SWDIO") (class "Default")
      (node (ref "CN8") (pin "2") (pinfunction "2_2") (pintype "unspecified"))
      (node (ref "U1") (pin "46") (pinfunction "PA13_46") (pintype "unspecified"))
    )
    (net (code "310") (name "TPS563252_EN") (class "Default")
      (node (ref "R154") (pin "2") (pinfunction "2_2") (pintype "unspecified"))
      (node (ref "R155") (pin "1") (pinfunction "1_1") (pintype "input"))
      (node (ref "U22") (pin "5") (pinfunction "EN_5") (pintype "unspecified"))
    )
    (net (code "311") (name "UART_D+") (class "Default")
      (node (ref "D1") (pin "3") (pinfunction "I/O2_3") (pintype "unspecified"))
      (node (ref "U13") (pin "4") (pinfunction "D+_4") (pintype "unspecified"))
    )
    (net (code "312") (name "UART_D-") (class "Default")
      (node (ref "D1") (pin "1") (pinfunction "I/O1_1") (pintype "unspecified"))
      (node (ref "U13") (pin "5") (pinfunction "D-_5") (pintype "unspecified"))
    )
    (net (code "313") (name "UART_EXTR_5V") (class "Default")
      (node (ref "D1") (pin "5") (pinfunction "VBUS_5") (pintype "unspecified"))
      (node (ref "R117") (pin "2") (pinfunction "2_2") (pintype "input"))
      (node (ref "R165") (pin "1") (pinfunction "1_1") (pintype "unspecified"))
      (node (ref "U26") (pin "3") (pinfunction "VIN1_3") (pintype "unspecified"))
      (node (ref "U26") (pin "5") (pinfunction "MODE_5") (pintype "unspecified"))
      (node (ref "USB1") (pin "A4B9") (pinfunction "VBUS_A4B9") (pintype "unspecified"))
      (node (ref "USB1") (pin "B4A9") (pinfunction "VBUS_B4A9") (pintype "unspecified"))
    )
    (net (code "314") (name "UART_EXTR_D+") (class "Default")
      (node (ref "D1") (pin "4") (pinfunction "I/O2_4") (pintype "unspecified"))
      (node (ref "USB1") (pin "A6") (pinfunction "Dp1_A6") (pintype "unspecified"))
      (node (ref "USB1") (pin "B6") (pinfunction "Dp2_B6") (pintype "unspecified"))
    )
    (net (code "315") (name "UART_EXTR_D-") (class "Default")
      (node (ref "D1") (pin "6") (pinfunction "I/O1_6") (pintype "unspecified"))
      (node (ref "USB1") (pin "A7") (pinfunction "Dn1_A7") (pintype "unspecified"))
      (node (ref "USB1") (pin "B7") (pinfunction "Dn2_B7") (pintype "unspecified"))
    )
    (net (code "316") (name "UART_STM32_RX2TX") (class "Default")
      (node (ref "H7") (pin "1") (pinfunction "1_1") (pintype "unspecified"))
      (node (ref "U1") (pin "17") (pinfunction "PA3_17") (pintype "unspecified"))
    )
    (net (code "317") (name "UART_STM32_TX2RX") (class "Default")
      (node (ref "H7") (pin "2") (pinfunction "2_2") (pintype "unspecified"))
      (node (ref "U1") (pin "16") (pinfunction "PA2_16") (pintype "unspecified"))
    )
    (net (code "318") (name "VCAP") (class "Default")
      (node (ref "C1") (pin "2") (pinfunction "2_2") (pintype "unspecified"))
      (node (ref "U1") (pin "30") (pinfunction "VCAP_1_30") (pintype "unspecified"))
    )
    (net (code "319") (name "VM") (class "Default")
      (node (ref "C15") (pin "1") (pinfunction "1_1") (pintype "input"))
      (node (ref "C16") (pin "1") (pinfunction "1_1") (pintype "input"))
      (node (ref "C17") (pin "1") (pinfunction "1_1") (pintype "input"))
      (node (ref "C18") (pin "1") (pinfunction "1_1") (pintype "input"))
      (node (ref "C21") (pin "1") (pinfunction "1_1") (pintype "input"))
      (node (ref "C23") (pin "1") (pinfunction "1_1") (pintype "input"))
      (node (ref "C24") (pin "1") (pinfunction "1_1") (pintype "input"))
      (node (ref "C25") (pin "1") (pinfunction "1_1") (pintype "input"))
      (node (ref "C26") (pin "2") (pinfunction "2_2") (pintype "unspecified"))
      (node (ref "C27") (pin "2") (pinfunction "2_2") (pintype "unspecified"))
      (node (ref "C28") (pin "2") (pinfunction "2_2") (pintype "unspecified"))
      (node (ref "C29") (pin "2") (pinfunction "2_2") (pintype "unspecified"))
      (node (ref "C30") (pin "2") (pinfunction "2_2") (pintype "unspecified"))
      (node (ref "C31") (pin "2") (pinfunction "2_2") (pintype "unspecified"))
      (node (ref "C32") (pin "2") (pinfunction "2_2") (pintype "unspecified"))
      (node (ref "C33") (pin "2") (pinfunction "2_2") (pintype "unspecified"))
      (node (ref "C63") (pin "2") (pinfunction "2_2") (pintype "unspecified"))
      (node (ref "C64") (pin "2") (pinfunction "2_2") (pintype "unspecified"))
      (node (ref "C65") (pin "2") (pinfunction "2_2") (pintype "unspecified"))
      (node (ref "C66") (pin "2") (pinfunction "2_2") (pintype "unspecified"))
      (node (ref "C67") (pin "2") (pinfunction "2_2") (pintype "unspecified"))
      (node (ref "C68") (pin "2") (pinfunction "2_2") (pintype "unspecified"))
      (node (ref "C69") (pin "2") (pinfunction "2_2") (pintype "unspecified"))
      (node (ref "C70") (pin "2") (pinfunction "2_2") (pintype "unspecified"))
      (node (ref "SW15") (pin "2") (pinfunction "2_2") (pintype "unspecified"))
      (node (ref "SW16") (pin "2") (pinfunction "2_2") (pintype "unspecified"))
      (node (ref "U15") (pin "3") (pinfunction "VIN_3") (pintype "unspecified"))
      (node (ref "U16") (pin "3") (pinfunction "VIN_3") (pintype "unspecified"))
      (node (ref "U2") (pin "10") (pinfunction "VMA_10") (pintype "unspecified"))
      (node (ref "U2") (pin "11") (pinfunction "VMA_11") (pintype "unspecified"))
      (node (ref "U2") (pin "26") (pinfunction "VMB_26") (pintype "unspecified"))
      (node (ref "U2") (pin "27") (pinfunction "VMB_27") (pintype "unspecified"))
      (node (ref "U3") (pin "10") (pinfunction "VMA_10") (pintype "unspecified"))
      (node (ref "U3") (pin "11") (pinfunction "VMA_11") (pintype "unspecified"))
      (node (ref "U3") (pin "26") (pinfunction "VMB_26") (pintype "unspecified"))
      (node (ref "U3") (pin "27") (pinfunction "VMB_27") (pintype "unspecified"))
      (node (ref "U4") (pin "10") (pinfunction "VMA_10") (pintype "unspecified"))
      (node (ref "U4") (pin "11") (pinfunction "VMA_11") (pintype "unspecified"))
      (node (ref "U4") (pin "26") (pinfunction "VMB_26") (pintype "unspecified"))
      (node (ref "U4") (pin "27") (pinfunction "VMB_27") (pintype "unspecified"))
      (node (ref "U5") (pin "10") (pinfunction "VMA_10") (pintype "unspecified"))
      (node (ref "U5") (pin "11") (pinfunction "VMA_11") (pintype "unspecified"))
      (node (ref "U5") (pin "26") (pinfunction "VMB_26") (pintype "unspecified"))
      (node (ref "U5") (pin "27") (pinfunction "VMB_27") (pintype "unspecified"))
      (node (ref "U6") (pin "10") (pinfunction "VMA_10") (pintype "unspecified"))
      (node (ref "U6") (pin "11") (pinfunction "VMA_11") (pintype "unspecified"))
      (node (ref "U6") (pin "26") (pinfunction "VMB_26") (pintype "unspecified"))
      (node (ref "U6") (pin "27") (pinfunction "VMB_27") (pintype "unspecified"))
      (node (ref "U7") (pin "10") (pinfunction "VMA_10") (pintype "unspecified"))
      (node (ref "U7") (pin "11") (pinfunction "VMA_11") (pintype "unspecified"))
      (node (ref "U7") (pin "26") (pinfunction "VMB_26") (pintype "unspecified"))
      (node (ref "U7") (pin "27") (pinfunction "VMB_27") (pintype "unspecified"))
      (node (ref "U8") (pin "10") (pinfunction "VMA_10") (pintype "unspecified"))
      (node (ref "U8") (pin "11") (pinfunction "VMA_11") (pintype "unspecified"))
      (node (ref "U8") (pin "26") (pinfunction "VMB_26") (pintype "unspecified"))
      (node (ref "U8") (pin "27") (pinfunction "VMB_27") (pintype "unspecified"))
    )
    (net (code "320") (name "VMTO3V3") (class "Default")
      (node (ref "C38") (pin "2") (pinfunction "2_2") (pintype "unspecified"))
      (node (ref "C39") (pin "2") (pinfunction "2_2") (pintype "unspecified"))
      (node (ref "L1") (pin "2") (pinfunction "2_2") (pintype "unspecified"))
      (node (ref "R136") (pin "1") (pinfunction "1_1") (pintype "input"))
      (node (ref "R159") (pin "1") (pinfunction "1_1") (pintype "unspecified"))
      (node (ref "U23") (pin "3") (pinfunction "VIN1_3") (pintype "unspecified"))
      (node (ref "U23") (pin "5") (pinfunction "MODE_5") (pintype "unspecified"))
    )
    (net (code "321") (name "unconnected-(CN8-Pad6)") (class "Default")
      (node (ref "CN8") (pin "6") (pinfunction "6_6") (pintype "unspecified+no_connect"))
    )
    (net (code "322") (name "unconnected-(CN8-Pad7)") (class "Default")
      (node (ref "CN8") (pin "7") (pinfunction "7_7") (pintype "unspecified+no_connect"))
    )
    (net (code "323") (name "unconnected-(CN8-Pad8)") (class "Default")
      (node (ref "CN8") (pin "8") (pinfunction "8_8") (pintype "unspecified+no_connect"))
    )
    (net (code "324") (name "unconnected-(CN8-Pad9)") (class "Default")
      (node (ref "CN8") (pin "9") (pinfunction "9_9") (pintype "unspecified+no_connect"))
    )
    (net (code "325") (name "unconnected-(CN9-非焊接件-Pad1)") (class "Default")
      (node (ref "CN9") (pin "1") (pinfunction "非焊接件_1") (pintype "unspecified"))
    )
    (net (code "326") (name "unconnected-(CN10-非焊接件-Pad1)") (class "Default")
      (node (ref "CN10") (pin "1") (pinfunction "非焊接件_1") (pintype "unspecified"))
    )
    (net (code "327") (name "unconnected-(CN11-非焊接件-Pad1)") (class "Default")
      (node (ref "CN11") (pin "1") (pinfunction "非焊接件_1") (pintype "unspecified"))
    )
    (net (code "328") (name "unconnected-(CN12-非焊接件-Pad1)") (class "Default")
      (node (ref "CN12") (pin "1") (pinfunction "非焊接件_1") (pintype "unspecified"))
    )
    (net (code "329") (name "unconnected-(CN13-非焊接件-Pad1)") (class "Default")
      (node (ref "CN13") (pin "1") (pinfunction "非焊接件_1") (pintype "unspecified"))
    )
    (net (code "330") (name "unconnected-(CN14-非焊接件-Pad1)") (class "Default")
      (node (ref "CN14") (pin "1") (pinfunction "非焊接件_1") (pintype "unspecified"))
    )
    (net (code "331") (name "unconnected-(CN15-非焊接件-Pad1)") (class "Default")
      (node (ref "CN15") (pin "1") (pinfunction "非焊接件_1") (pintype "unspecified"))
    )
    (net (code "332") (name "unconnected-(SW15-Pad3)") (class "Default")
      (node (ref "SW15") (pin "3") (pinfunction "3_3") (pintype "unspecified"))
    )
    (net (code "333") (name "unconnected-(SW16-Pad3)") (class "Default")
      (node (ref "SW16") (pin "3") (pinfunction "3_3") (pintype "unspecified"))
    )
    (net (code "334") (name "unconnected-(U1-PA1-Pad15)") (class "Default")
      (node (ref "U1") (pin "15") (pinfunction "PA1_15") (pintype "unspecified"))
    )
    (net (code "335") (name "unconnected-(U1-PA4-Pad20)") (class "Default")
      (node (ref "U1") (pin "20") (pinfunction "PA4_20") (pintype "unspecified"))
    )
    (net (code "336") (name "unconnected-(U1-PA5-Pad21)") (class "Default")
      (node (ref "U1") (pin "21") (pinfunction "PA5_21") (pintype "unspecified"))
    )
    (net (code "337") (name "unconnected-(U1-PB7-Pad59)") (class "Default")
      (node (ref "U1") (pin "59") (pinfunction "PB7_59") (pintype "unspecified"))
    )
    (net (code "338") (name "unconnected-(U1-PB13-Pad34)") (class "Default")
      (node (ref "U1") (pin "34") (pinfunction "PB13_34") (pintype "unspecified"))
    )
    (net (code "339") (name "unconnected-(U1-PC6-Pad37)") (class "Default")
      (node (ref "U1") (pin "37") (pinfunction "PC6_37") (pintype "unspecified"))
    )
    (net (code "340") (name "unconnected-(U1-PC14-OSC32_IN-Pad3)") (class "Default")
      (node (ref "U1") (pin "3") (pinfunction "PC14-OSC32_IN_3") (pintype "unspecified"))
    )
    (net (code "341") (name "unconnected-(U1-PC15-OSC32_OUT-Pad4)") (class "Default")
      (node (ref "U1") (pin "4") (pinfunction "PC15-OSC32_OUT_4") (pintype "unspecified"))
    )
    (net (code "342") (name "unconnected-(U1-PH0-OSC_IN-Pad5)") (class "Default")
      (node (ref "U1") (pin "5") (pinfunction "PH0-OSC_IN_5") (pintype "unspecified"))
    )
    (net (code "343") (name "unconnected-(U1-PH1-OSC_OUT-Pad6)") (class "Default")
      (node (ref "U1") (pin "6") (pinfunction "PH1-OSC_OUT_6") (pintype "unspecified"))
    )
    (net (code "344") (name "unconnected-(U1-VBAT-Pad1)") (class "Default")
      (node (ref "U1") (pin "1") (pinfunction "VBAT_1") (pintype "unspecified"))
    )
    (net (code "345") (name "unconnected-(U2-NC-Pad9)") (class "Default")
      (node (ref "U2") (pin "9") (pinfunction "NC_9") (pintype "unspecified"))
    )
    (net (code "346") (name "unconnected-(U2-NC-Pad12)") (class "Default")
      (node (ref "U2") (pin "12") (pinfunction "NC_12") (pintype "unspecified"))
    )
    (net (code "347") (name "unconnected-(U2-NC-Pad25)") (class "Default")
      (node (ref "U2") (pin "25") (pinfunction "NC_25") (pintype "unspecified"))
    )
    (net (code "348") (name "unconnected-(U2-NC-Pad28)") (class "Default")
      (node (ref "U2") (pin "28") (pinfunction "NC_28") (pintype "unspecified"))
    )
    (net (code "349") (name "unconnected-(U2-NC-Pad36)") (class "Default")
      (node (ref "U2") (pin "36") (pinfunction "NC_36") (pintype "unspecified"))
    )
    (net (code "350") (name "unconnected-(U2-NC-Pad37)") (class "Default")
      (node (ref "U2") (pin "37") (pinfunction "NC_37") (pintype "unspecified"))
    )
    (net (code "351") (name "unconnected-(U2-NC-Pad38)") (class "Default")
      (node (ref "U2") (pin "38") (pinfunction "NC_38") (pintype "unspecified"))
    )
    (net (code "352") (name "unconnected-(U2-Pad50)") (class "Default")
      (node (ref "U2") (pin "50") (pinfunction "50_50") (pintype "unspecified"))
    )
    (net (code "353") (name "unconnected-(U2-Pad51)") (class "Default")
      (node (ref "U2") (pin "51") (pinfunction "51_51") (pintype "unspecified"))
    )
    (net (code "354") (name "unconnected-(U2-Pad52)") (class "Default")
      (node (ref "U2") (pin "52") (pinfunction "52_52") (pintype "unspecified"))
    )
    (net (code "355") (name "unconnected-(U2-Pad53)") (class "Default")
      (node (ref "U2") (pin "53") (pinfunction "53_53") (pintype "unspecified"))
    )
    (net (code "356") (name "unconnected-(U2-RESET-Pad45)") (class "Default")
      (node (ref "U2") (pin "45") (pinfunction "RESET_45") (pintype "unspecified"))
    )
    (net (code "357") (name "unconnected-(U3-NC-Pad9)") (class "Default")
      (node (ref "U3") (pin "9") (pinfunction "NC_9") (pintype "unspecified"))
    )
    (net (code "358") (name "unconnected-(U3-NC-Pad12)") (class "Default")
      (node (ref "U3") (pin "12") (pinfunction "NC_12") (pintype "unspecified"))
    )
    (net (code "359") (name "unconnected-(U3-NC-Pad25)") (class "Default")
      (node (ref "U3") (pin "25") (pinfunction "NC_25") (pintype "unspecified"))
    )
    (net (code "360") (name "unconnected-(U3-NC-Pad28)") (class "Default")
      (node (ref "U3") (pin "28") (pinfunction "NC_28") (pintype "unspecified"))
    )
    (net (code "361") (name "unconnected-(U3-NC-Pad36)") (class "Default")
      (node (ref "U3") (pin "36") (pinfunction "NC_36") (pintype "unspecified"))
    )
    (net (code "362") (name "unconnected-(U3-NC-Pad37)") (class "Default")
      (node (ref "U3") (pin "37") (pinfunction "NC_37") (pintype "unspecified"))
    )
    (net (code "363") (name "unconnected-(U3-NC-Pad38)") (class "Default")
      (node (ref "U3") (pin "38") (pinfunction "NC_38") (pintype "unspecified"))
    )
    (net (code "364") (name "unconnected-(U3-Pad50)") (class "Default")
      (node (ref "U3") (pin "50") (pinfunction "50_50") (pintype "unspecified"))
    )
    (net (code "365") (name "unconnected-(U3-Pad51)") (class "Default")
      (node (ref "U3") (pin "51") (pinfunction "51_51") (pintype "unspecified"))
    )
    (net (code "366") (name "unconnected-(U3-Pad52)") (class "Default")
      (node (ref "U3") (pin "52") (pinfunction "52_52") (pintype "unspecified"))
    )
    (net (code "367") (name "unconnected-(U3-Pad53)") (class "Default")
      (node (ref "U3") (pin "53") (pinfunction "53_53") (pintype "unspecified"))
    )
    (net (code "368") (name "unconnected-(U3-RESET-Pad45)") (class "Default")
      (node (ref "U3") (pin "45") (pinfunction "RESET_45") (pintype "unspecified"))
    )
    (net (code "369") (name "unconnected-(U4-NC-Pad9)") (class "Default")
      (node (ref "U4") (pin "9") (pinfunction "NC_9") (pintype "unspecified"))
    )
    (net (code "370") (name "unconnected-(U4-NC-Pad12)") (class "Default")
      (node (ref "U4") (pin "12") (pinfunction "NC_12") (pintype "unspecified"))
    )
    (net (code "371") (name "unconnected-(U4-NC-Pad25)") (class "Default")
      (node (ref "U4") (pin "25") (pinfunction "NC_25") (pintype "unspecified"))
    )
    (net (code "372") (name "unconnected-(U4-NC-Pad28)") (class "Default")
      (node (ref "U4") (pin "28") (pinfunction "NC_28") (pintype "unspecified"))
    )
    (net (code "373") (name "unconnected-(U4-NC-Pad36)") (class "Default")
      (node (ref "U4") (pin "36") (pinfunction "NC_36") (pintype "unspecified"))
    )
    (net (code "374") (name "unconnected-(U4-NC-Pad37)") (class "Default")
      (node (ref "U4") (pin "37") (pinfunction "NC_37") (pintype "unspecified"))
    )
    (net (code "375") (name "unconnected-(U4-NC-Pad38)") (class "Default")
      (node (ref "U4") (pin "38") (pinfunction "NC_38") (pintype "unspecified"))
    )
    (net (code "376") (name "unconnected-(U4-Pad50)") (class "Default")
      (node (ref "U4") (pin "50") (pinfunction "50_50") (pintype "unspecified"))
    )
    (net (code "377") (name "unconnected-(U4-Pad51)") (class "Default")
      (node (ref "U4") (pin "51") (pinfunction "51_51") (pintype "unspecified"))
    )
    (net (code "378") (name "unconnected-(U4-Pad52)") (class "Default")
      (node (ref "U4") (pin "52") (pinfunction "52_52") (pintype "unspecified"))
    )
    (net (code "379") (name "unconnected-(U4-Pad53)") (class "Default")
      (node (ref "U4") (pin "53") (pinfunction "53_53") (pintype "unspecified"))
    )
    (net (code "380") (name "unconnected-(U4-RESET-Pad45)") (class "Default")
      (node (ref "U4") (pin "45") (pinfunction "RESET_45") (pintype "unspecified"))
    )
    (net (code "381") (name "unconnected-(U5-NC-Pad9)") (class "Default")
      (node (ref "U5") (pin "9") (pinfunction "NC_9") (pintype "unspecified"))
    )
    (net (code "382") (name "unconnected-(U5-NC-Pad12)") (class "Default")
      (node (ref "U5") (pin "12") (pinfunction "NC_12") (pintype "unspecified"))
    )
    (net (code "383") (name "unconnected-(U5-NC-Pad25)") (class "Default")
      (node (ref "U5") (pin "25") (pinfunction "NC_25") (pintype "unspecified"))
    )
    (net (code "384") (name "unconnected-(U5-NC-Pad28)") (class "Default")
      (node (ref "U5") (pin "28") (pinfunction "NC_28") (pintype "unspecified"))
    )
    (net (code "385") (name "unconnected-(U5-NC-Pad36)") (class "Default")
      (node (ref "U5") (pin "36") (pinfunction "NC_36") (pintype "unspecified"))
    )
    (net (code "386") (name "unconnected-(U5-NC-Pad37)") (class "Default")
      (node (ref "U5") (pin "37") (pinfunction "NC_37") (pintype "unspecified"))
    )
    (net (code "387") (name "unconnected-(U5-NC-Pad38)") (class "Default")
      (node (ref "U5") (pin "38") (pinfunction "NC_38") (pintype "unspecified"))
    )
    (net (code "388") (name "unconnected-(U5-Pad50)") (class "Default")
      (node (ref "U5") (pin "50") (pinfunction "50_50") (pintype "unspecified"))
    )
    (net (code "389") (name "unconnected-(U5-Pad51)") (class "Default")
      (node (ref "U5") (pin "51") (pinfunction "51_51") (pintype "unspecified"))
    )
    (net (code "390") (name "unconnected-(U5-Pad52)") (class "Default")
      (node (ref "U5") (pin "52") (pinfunction "52_52") (pintype "unspecified"))
    )
    (net (code "391") (name "unconnected-(U5-Pad53)") (class "Default")
      (node (ref "U5") (pin "53") (pinfunction "53_53") (pintype "unspecified"))
    )
    (net (code "392") (name "unconnected-(U5-RESET-Pad45)") (class "Default")
      (node (ref "U5") (pin "45") (pinfunction "RESET_45") (pintype "unspecified"))
    )
    (net (code "393") (name "unconnected-(U6-NC-Pad9)") (class "Default")
      (node (ref "U6") (pin "9") (pinfunction "NC_9") (pintype "unspecified"))
    )
    (net (code "394") (name "unconnected-(U6-NC-Pad12)") (class "Default")
      (node (ref "U6") (pin "12") (pinfunction "NC_12") (pintype "unspecified"))
    )
    (net (code "395") (name "unconnected-(U6-NC-Pad25)") (class "Default")
      (node (ref "U6") (pin "25") (pinfunction "NC_25") (pintype "unspecified"))
    )
    (net (code "396") (name "unconnected-(U6-NC-Pad28)") (class "Default")
      (node (ref "U6") (pin "28") (pinfunction "NC_28") (pintype "unspecified"))
    )
    (net (code "397") (name "unconnected-(U6-NC-Pad36)") (class "Default")
      (node (ref "U6") (pin "36") (pinfunction "NC_36") (pintype "unspecified"))
    )
    (net (code "398") (name "unconnected-(U6-NC-Pad37)") (class "Default")
      (node (ref "U6") (pin "37") (pinfunction "NC_37") (pintype "unspecified"))
    )
    (net (code "399") (name "unconnected-(U6-NC-Pad38)") (class "Default")
      (node (ref "U6") (pin "38") (pinfunction "NC_38") (pintype "unspecified"))
    )
    (net (code "400") (name "unconnected-(U6-Pad50)") (class "Default")
      (node (ref "U6") (pin "50") (pinfunction "50_50") (pintype "unspecified"))
    )
    (net (code "401") (name "unconnected-(U6-Pad51)") (class "Default")
      (node (ref "U6") (pin "51") (pinfunction "51_51") (pintype "unspecified"))
    )
    (net (code "402") (name "unconnected-(U6-Pad52)") (class "Default")
      (node (ref "U6") (pin "52") (pinfunction "52_52") (pintype "unspecified"))
    )
    (net (code "403") (name "unconnected-(U6-Pad53)") (class "Default")
      (node (ref "U6") (pin "53") (pinfunction "53_53") (pintype "unspecified"))
    )
    (net (code "404") (name "unconnected-(U6-RESET-Pad45)") (class "Default")
      (node (ref "U6") (pin "45") (pinfunction "RESET_45") (pintype "unspecified"))
    )
    (net (code "405") (name "unconnected-(U7-NC-Pad9)") (class "Default")
      (node (ref "U7") (pin "9") (pinfunction "NC_9") (pintype "unspecified"))
    )
    (net (code "406") (name "unconnected-(U7-NC-Pad12)") (class "Default")
      (node (ref "U7") (pin "12") (pinfunction "NC_12") (pintype "unspecified"))
    )
    (net (code "407") (name "unconnected-(U7-NC-Pad25)") (class "Default")
      (node (ref "U7") (pin "25") (pinfunction "NC_25") (pintype "unspecified"))
    )
    (net (code "408") (name "unconnected-(U7-NC-Pad28)") (class "Default")
      (node (ref "U7") (pin "28") (pinfunction "NC_28") (pintype "unspecified"))
    )
    (net (code "409") (name "unconnected-(U7-NC-Pad36)") (class "Default")
      (node (ref "U7") (pin "36") (pinfunction "NC_36") (pintype "unspecified"))
    )
    (net (code "410") (name "unconnected-(U7-NC-Pad37)") (class "Default")
      (node (ref "U7") (pin "37") (pinfunction "NC_37") (pintype "unspecified"))
    )
    (net (code "411") (name "unconnected-(U7-NC-Pad38)") (class "Default")
      (node (ref "U7") (pin "38") (pinfunction "NC_38") (pintype "unspecified"))
    )
    (net (code "412") (name "unconnected-(U7-Pad50)") (class "Default")
      (node (ref "U7") (pin "50") (pinfunction "50_50") (pintype "unspecified"))
    )
    (net (code "413") (name "unconnected-(U7-Pad51)") (class "Default")
      (node (ref "U7") (pin "51") (pinfunction "51_51") (pintype "unspecified"))
    )
    (net (code "414") (name "unconnected-(U7-Pad52)") (class "Default")
      (node (ref "U7") (pin "52") (pinfunction "52_52") (pintype "unspecified"))
    )
    (net (code "415") (name "unconnected-(U7-Pad53)") (class "Default")
      (node (ref "U7") (pin "53") (pinfunction "53_53") (pintype "unspecified"))
    )
    (net (code "416") (name "unconnected-(U7-RESET-Pad45)") (class "Default")
      (node (ref "U7") (pin "45") (pinfunction "RESET_45") (pintype "unspecified"))
    )
    (net (code "417") (name "unconnected-(U8-NC-Pad9)") (class "Default")
      (node (ref "U8") (pin "9") (pinfunction "NC_9") (pintype "unspecified"))
    )
    (net (code "418") (name "unconnected-(U8-NC-Pad12)") (class "Default")
      (node (ref "U8") (pin "12") (pinfunction "NC_12") (pintype "unspecified"))
    )
    (net (code "419") (name "unconnected-(U8-NC-Pad25)") (class "Default")
      (node (ref "U8") (pin "25") (pinfunction "NC_25") (pintype "unspecified"))
    )
    (net (code "420") (name "unconnected-(U8-NC-Pad28)") (class "Default")
      (node (ref "U8") (pin "28") (pinfunction "NC_28") (pintype "unspecified"))
    )
    (net (code "421") (name "unconnected-(U8-NC-Pad36)") (class "Default")
      (node (ref "U8") (pin "36") (pinfunction "NC_36") (pintype "unspecified"))
    )
    (net (code "422") (name "unconnected-(U8-NC-Pad37)") (class "Default")
      (node (ref "U8") (pin "37") (pinfunction "NC_37") (pintype "unspecified"))
    )
    (net (code "423") (name "unconnected-(U8-NC-Pad38)") (class "Default")
      (node (ref "U8") (pin "38") (pinfunction "NC_38") (pintype "unspecified"))
    )
    (net (code "424") (name "unconnected-(U8-Pad50)") (class "Default")
      (node (ref "U8") (pin "50") (pinfunction "50_50") (pintype "unspecified"))
    )
    (net (code "425") (name "unconnected-(U8-Pad51)") (class "Default")
      (node (ref "U8") (pin "51") (pinfunction "51_51") (pintype "unspecified"))
    )
    (net (code "426") (name "unconnected-(U8-Pad52)") (class "Default")
      (node (ref "U8") (pin "52") (pinfunction "52_52") (pintype "unspecified"))
    )
    (net (code "427") (name "unconnected-(U8-Pad53)") (class "Default")
      (node (ref "U8") (pin "53") (pinfunction "53_53") (pintype "unspecified"))
    )
    (net (code "428") (name "unconnected-(U8-RESET-Pad45)") (class "Default")
      (node (ref "U8") (pin "45") (pinfunction "RESET_45") (pintype "unspecified"))
    )
    (net (code "429") (name "unconnected-(U9-IO1-Pad39)") (class "Default")
      (node (ref "U9") (pin "39") (pinfunction "IO1_39") (pintype "unspecified"))
    )
    (net (code "430") (name "unconnected-(U9-IO2-Pad38)") (class "Default")
      (node (ref "U9") (pin "38") (pinfunction "IO2_38") (pintype "unspecified"))
    )
    (net (code "431") (name "unconnected-(U9-IO3-Pad15)") (class "Default")
      (node (ref "U9") (pin "15") (pinfunction "IO3_15") (pintype "unspecified"))
    )
    (net (code "432") (name "unconnected-(U9-IO8-Pad12)") (class "Default")
      (node (ref "U9") (pin "12") (pinfunction "IO8_12") (pintype "unspecified"))
    )
    (net (code "433") (name "unconnected-(U9-IO9-Pad17)") (class "Default")
      (node (ref "U9") (pin "17") (pinfunction "IO9_17") (pintype "unspecified"))
    )
    (net (code "434") (name "unconnected-(U9-IO14-Pad22)") (class "Default")
      (node (ref "U9") (pin "22") (pinfunction "IO14_22") (pintype "unspecified"))
    )
    (net (code "435") (name "unconnected-(U9-IO15-Pad8)") (class "Default")
      (node (ref "U9") (pin "8") (pinfunction "IO15_8") (pintype "unspecified"))
    )
    (net (code "436") (name "unconnected-(U9-IO17-Pad10)") (class "Default")
      (node (ref "U9") (pin "10") (pinfunction "IO17_10") (pintype "unspecified"))
    )
    (net (code "437") (name "unconnected-(U9-IO18-Pad11)") (class "Default")
      (node (ref "U9") (pin "11") (pinfunction "IO18_11") (pintype "unspecified"))
    )
    (net (code "438") (name "unconnected-(U9-IO21-Pad23)") (class "Default")
      (node (ref "U9") (pin "23") (pinfunction "IO21_23") (pintype "unspecified"))
    )
    (net (code "439") (name "unconnected-(U9-IO37-Pad30)") (class "Default")
      (node (ref "U9") (pin "30") (pinfunction "IO37_30") (pintype "unspecified"))
    )
    (net (code "440") (name "unconnected-(U9-IO38-Pad31)") (class "Default")
      (node (ref "U9") (pin "31") (pinfunction "IO38_31") (pintype "unspecified"))
    )
    (net (code "441") (name "unconnected-(U9-IO39-Pad32)") (class "Default")
      (node (ref "U9") (pin "32") (pinfunction "IO39_32") (pintype "unspecified"))
    )
    (net (code "442") (name "unconnected-(U9-IO40-Pad33)") (class "Default")
      (node (ref "U9") (pin "33") (pinfunction "IO40_33") (pintype "unspecified"))
    )
    (net (code "443") (name "unconnected-(U9-IO41-Pad34)") (class "Default")
      (node (ref "U9") (pin "34") (pinfunction "IO41_34") (pintype "unspecified"))
    )
    (net (code "444") (name "unconnected-(U9-IO42-Pad35)") (class "Default")
      (node (ref "U9") (pin "35") (pinfunction "IO42_35") (pintype "unspecified"))
    )
    (net (code "445") (name "unconnected-(U9-IO45-Pad26)") (class "Default")
      (node (ref "U9") (pin "26") (pinfunction "IO45_26") (pintype "unspecified"))
    )
    (net (code "446") (name "unconnected-(U9-IO46-Pad16)") (class "Default")
      (node (ref "U9") (pin "16") (pinfunction "IO46_16") (pintype "unspecified"))
    )
    (net (code "447") (name "unconnected-(U9-IO47-Pad24)") (class "Default")
      (node (ref "U9") (pin "24") (pinfunction "IO47_24") (pintype "unspecified"))
    )
    (net (code "448") (name "unconnected-(U9-IO48-Pad25)") (class "Default")
      (node (ref "U9") (pin "25") (pinfunction "IO48_25") (pintype "unspecified"))
    )
    (net (code "449") (name "unconnected-(U10-INTA-Pad20)") (class "Default")
      (node (ref "U10") (pin "20") (pinfunction "INTA_20") (pintype "unspecified"))
    )
    (net (code "450") (name "unconnected-(U10-INTB-Pad19)") (class "Default")
      (node (ref "U10") (pin "19") (pinfunction "INTB_19") (pintype "unspecified"))
    )
    (net (code "451") (name "unconnected-(U10-NC-Pad11)") (class "Default")
      (node (ref "U10") (pin "11") (pinfunction "NC_11") (pintype "unspecified"))
    )
    (net (code "452") (name "unconnected-(U10-NC-Pad14)") (class "Default")
      (node (ref "U10") (pin "14") (pinfunction "NC_14") (pintype "unspecified"))
    )
    (net (code "453") (name "unconnected-(U11-GPA7-Pad28)") (class "Default")
      (node (ref "U11") (pin "28") (pinfunction "GPA7_28") (pintype "unspecified"))
    )
    (net (code "454") (name "unconnected-(U11-GPB7-Pad8)") (class "Default")
      (node (ref "U11") (pin "8") (pinfunction "GPB7_8") (pintype "unspecified"))
    )
    (net (code "455") (name "unconnected-(U11-INTA-Pad20)") (class "Default")
      (node (ref "U11") (pin "20") (pinfunction "INTA_20") (pintype "unspecified"))
    )
    (net (code "456") (name "unconnected-(U11-INTB-Pad19)") (class "Default")
      (node (ref "U11") (pin "19") (pinfunction "INTB_19") (pintype "unspecified"))
    )
    (net (code "457") (name "unconnected-(U11-NC-Pad11)") (class "Default")
      (node (ref "U11") (pin "11") (pinfunction "NC_11") (pintype "unspecified"))
    )
    (net (code "458") (name "unconnected-(U11-NC-Pad14)") (class "Default")
      (node (ref "U11") (pin "14") (pinfunction "NC_14") (pintype "unspecified"))
    )
    (net (code "459") (name "unconnected-(U12-GPA5-Pad26)") (class "Default")
      (node (ref "U12") (pin "26") (pinfunction "GPA5_26") (pintype "unspecified"))
    )
    (net (code "460") (name "unconnected-(U12-GPA6-Pad27)") (class "Default")
      (node (ref "U12") (pin "27") (pinfunction "GPA6_27") (pintype "unspecified"))
    )
    (net (code "461") (name "unconnected-(U12-GPA7-Pad28)") (class "Default")
      (node (ref "U12") (pin "28") (pinfunction "GPA7_28") (pintype "unspecified"))
    )
    (net (code "462") (name "unconnected-(U12-GPB0-Pad1)") (class "Default")
      (node (ref "U12") (pin "1") (pinfunction "GPB0_1") (pintype "unspecified"))
    )
    (net (code "463") (name "unconnected-(U12-GPB1-Pad2)") (class "Default")
      (node (ref "U12") (pin "2") (pinfunction "GPB1_2") (pintype "unspecified"))
    )
    (net (code "464") (name "unconnected-(U12-GPB2-Pad3)") (class "Default")
      (node (ref "U12") (pin "3") (pinfunction "GPB2_3") (pintype "unspecified"))
    )
    (net (code "465") (name "unconnected-(U12-GPB3-Pad4)") (class "Default")
      (node (ref "U12") (pin "4") (pinfunction "GPB3_4") (pintype "unspecified"))
    )
    (net (code "466") (name "unconnected-(U12-GPB4-Pad5)") (class "Default")
      (node (ref "U12") (pin "5") (pinfunction "GPB4_5") (pintype "unspecified"))
    )
    (net (code "467") (name "unconnected-(U12-GPB5-Pad6)") (class "Default")
      (node (ref "U12") (pin "6") (pinfunction "GPB5_6") (pintype "unspecified"))
    )
    (net (code "468") (name "unconnected-(U12-GPB6-Pad7)") (class "Default")
      (node (ref "U12") (pin "7") (pinfunction "GPB6_7") (pintype "unspecified"))
    )
    (net (code "469") (name "unconnected-(U12-GPB7-Pad8)") (class "Default")
      (node (ref "U12") (pin "8") (pinfunction "GPB7_8") (pintype "unspecified"))
    )
    (net (code "470") (name "unconnected-(U12-INTA-Pad20)") (class "Default")
      (node (ref "U12") (pin "20") (pinfunction "INTA_20") (pintype "unspecified"))
    )
    (net (code "471") (name "unconnected-(U12-INTB-Pad19)") (class "Default")
      (node (ref "U12") (pin "19") (pinfunction "INTB_19") (pintype "unspecified"))
    )
    (net (code "472") (name "unconnected-(U12-NC-Pad11)") (class "Default")
      (node (ref "U12") (pin "11") (pinfunction "NC_11") (pintype "unspecified"))
    )
    (net (code "473") (name "unconnected-(U12-NC-Pad14)") (class "Default")
      (node (ref "U12") (pin "14") (pinfunction "NC_14") (pintype "unspecified"))
    )
    (net (code "474") (name "unconnected-(U13-CHR0-Pad15)") (class "Default")
      (node (ref "U13") (pin "15") (pinfunction "CHR0_15") (pintype "unspecified"))
    )
    (net (code "475") (name "unconnected-(U13-CHR1-Pad14)") (class "Default")
      (node (ref "U13") (pin "14") (pinfunction "CHR1_14") (pintype "unspecified"))
    )
    (net (code "476") (name "unconnected-(U13-CHREN-Pad13)") (class "Default")
      (node (ref "U13") (pin "13") (pinfunction "CHREN_13") (pintype "unspecified"))
    )
    (net (code "477") (name "unconnected-(U13-CTS-Pad23)") (class "Default")
      (node (ref "U13") (pin "23") (pinfunction "CTS_23") (pintype "unspecified"))
    )
    (net (code "478") (name "unconnected-(U13-DCD-Pad1)") (class "Default")
      (node (ref "U13") (pin "1") (pinfunction "DCD_1") (pintype "unspecified"))
    )
    (net (code "479") (name "unconnected-(U13-DSR-Pad27)") (class "Default")
      (node (ref "U13") (pin "27") (pinfunction "DSR_27") (pintype "unspecified"))
    )
    (net (code "480") (name "unconnected-(U13-GPIO.0{slash}TXT-Pad19)") (class "Default")
      (node (ref "U13") (pin "19") (pinfunction "GPIO.0/TXT_19") (pintype "unspecified"))
    )
    (net (code "481") (name "unconnected-(U13-GPIO.1{slash}RXT-Pad18)") (class "Default")
      (node (ref "U13") (pin "18") (pinfunction "GPIO.1/RXT_18") (pintype "unspecified"))
    )
    (net (code "482") (name "unconnected-(U13-GPIO.2{slash}RS485-Pad17)") (class "Default")
      (node (ref "U13") (pin "17") (pinfunction "GPIO.2/RS485_17") (pintype "unspecified"))
    )
    (net (code "483") (name "unconnected-(U13-GPIO.3{slash}WAKEUP-Pad16)") (class "Default")
      (node (ref "U13") (pin "16") (pinfunction "GPIO.3/WAKEUP_16") (pintype "unspecified"))
    )
    (net (code "484") (name "unconnected-(U13-GPIO.4-Pad22)") (class "Default")
      (node (ref "U13") (pin "22") (pinfunction "GPIO.4_22") (pintype "unspecified"))
    )
    (net (code "485") (name "unconnected-(U13-GPIO.5-Pad21)") (class "Default")
      (node (ref "U13") (pin "21") (pinfunction "GPIO.5_21") (pintype "unspecified"))
    )
    (net (code "486") (name "unconnected-(U13-GPIO.6-Pad20)") (class "Default")
      (node (ref "U13") (pin "20") (pinfunction "GPIO.6_20") (pintype "unspecified"))
    )
    (net (code "487") (name "unconnected-(U13-NC-Pad10)") (class "Default")
      (node (ref "U13") (pin "10") (pinfunction "NC_10") (pintype "unspecified"))
    )
    (net (code "488") (name "unconnected-(U13-RI{slash}CLK-Pad2)") (class "Default")
      (node (ref "U13") (pin "2") (pinfunction "RI/CLK_2") (pintype "unspecified"))
    )
    (net (code "489") (name "unconnected-(U13-RSTb-Pad9)") (class "Default")
      (node (ref "U13") (pin "9") (pinfunction "RSTb_9") (pintype "unspecified"))
    )
    (net (code "490") (name "unconnected-(U13-SUSPEND-Pad12)") (class "Default")
      (node (ref "U13") (pin "12") (pinfunction "SUSPEND_12") (pintype "unspecified"))
    )
    (net (code "491") (name "unconnected-(U13-SUSPENDb-Pad11)") (class "Default")
      (node (ref "U13") (pin "11") (pinfunction "SUSPENDb_11") (pintype "unspecified"))
    )
    (net (code "492") (name "unconnected-(U24-ALERT-Pad3)") (class "Default")
      (node (ref "U24") (pin "3") (pinfunction "ALERT_3") (pintype "unspecified"))
    )
    (net (code "493") (name "unconnected-(U25-ALERT-Pad3)") (class "Default")
      (node (ref "U25") (pin "3") (pinfunction "ALERT_3") (pintype "unspecified"))
    )
    (net (code "494") (name "unconnected-(U29-VOUTH-Pad12)") (class "Default")
      (node (ref "U29") (pin "12") (pinfunction "VOUTH_12") (pintype "input"))
    )
    (net (code "495") (name "unconnected-(USB1-SBU1-PadA8)") (class "Default")
      (node (ref "USB1") (pin "A8") (pinfunction "SBU1_A8") (pintype "unspecified+no_connect"))
    )
    (net (code "496") (name "unconnected-(USB1-SBU2-PadB8)") (class "Default")
      (node (ref "USB1") (pin "B8") (pinfunction "SBU2_B8") (pintype "unspecified+no_connect"))
    )
    (net (code "497") (name "unconnected-(USB2-SBU1-PadA8)") (class "Default")
      (node (ref "USB2") (pin "A8") (pinfunction "SBU1_A8") (pintype "unspecified+no_connect"))
    )
    (net (code "498") (name "unconnected-(USB2-SBU2-PadB8)") (class "Default")
      (node (ref "USB2") (pin "B8") (pinfunction "SBU2_B8") (pintype "unspecified+no_connect"))
    )
  )
)
